# backplane.net
KiCad netlist of a schematic drawn in Altium Designer
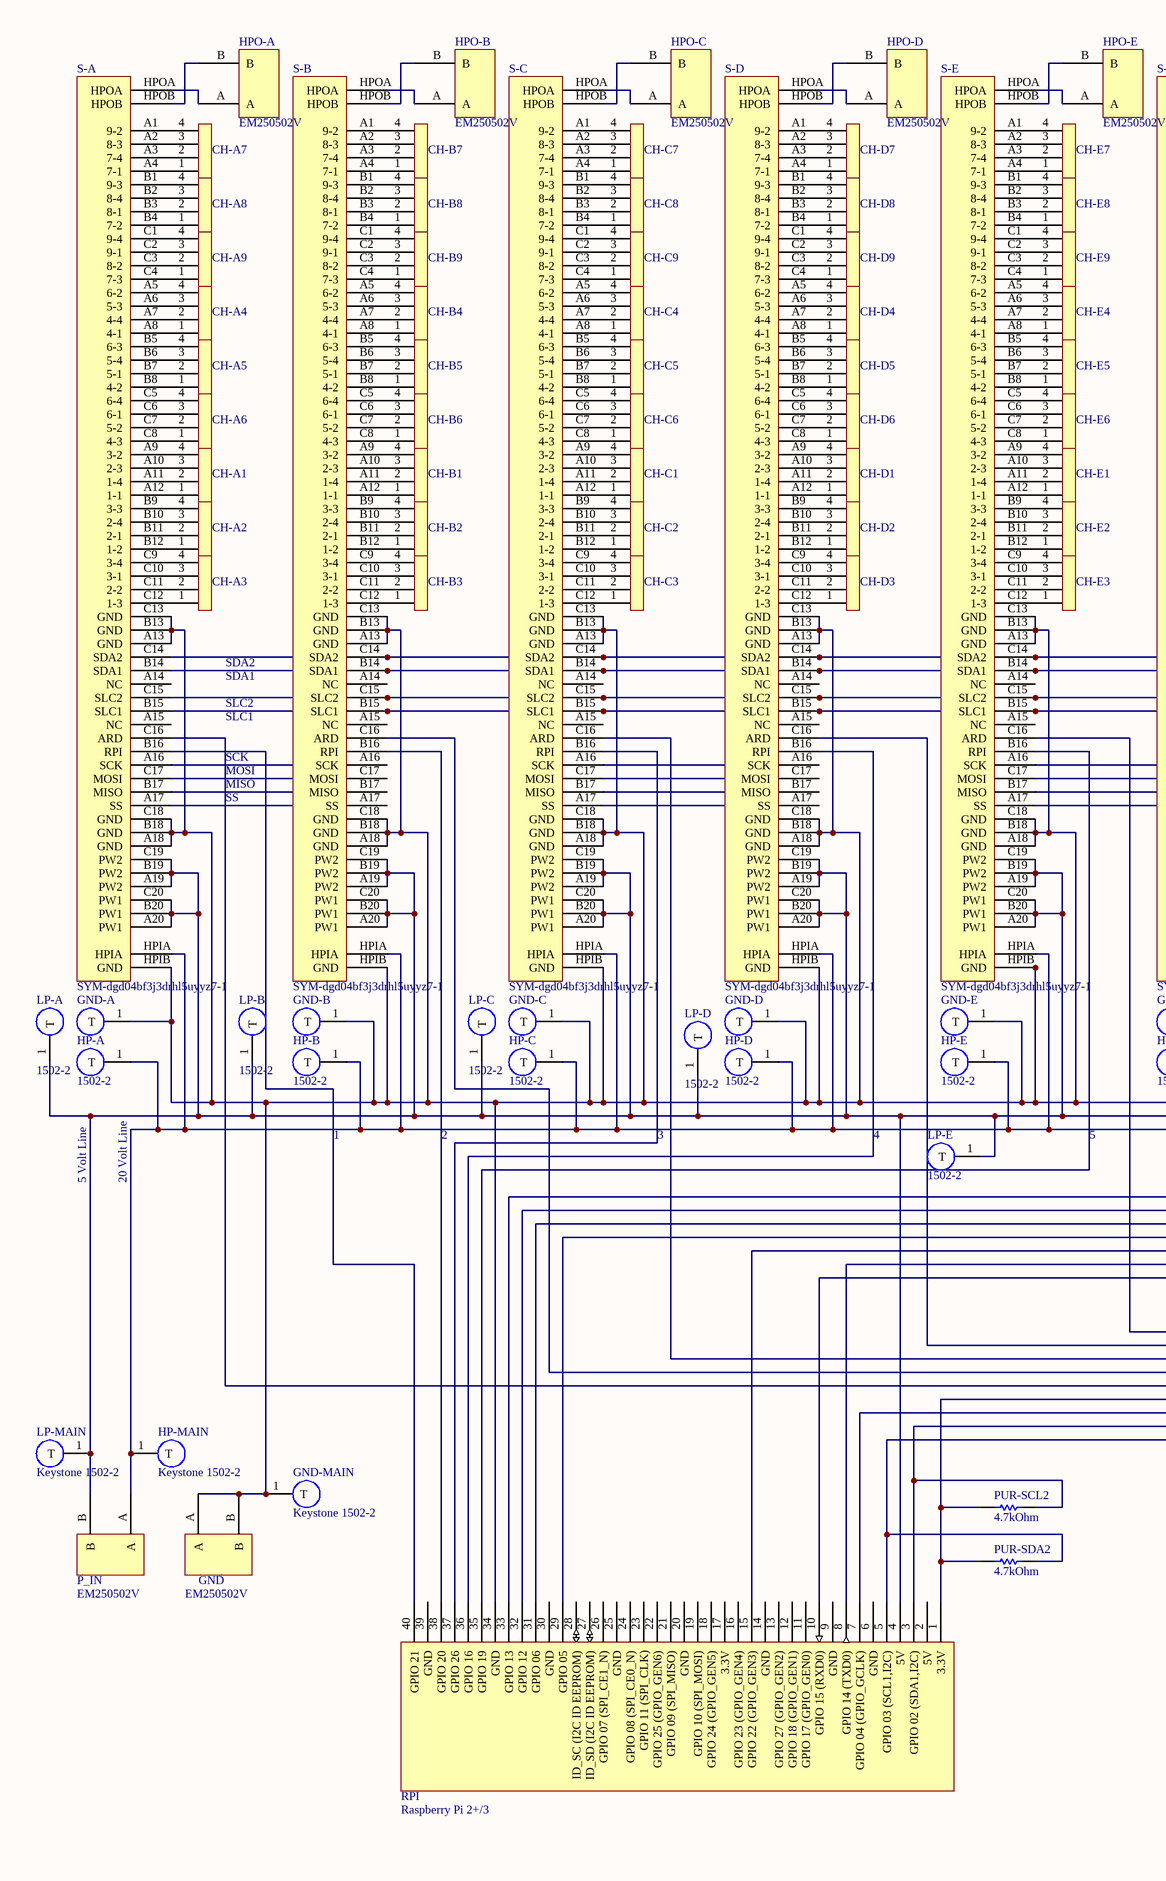
[diagram p0: backplane.SchDoc, left]
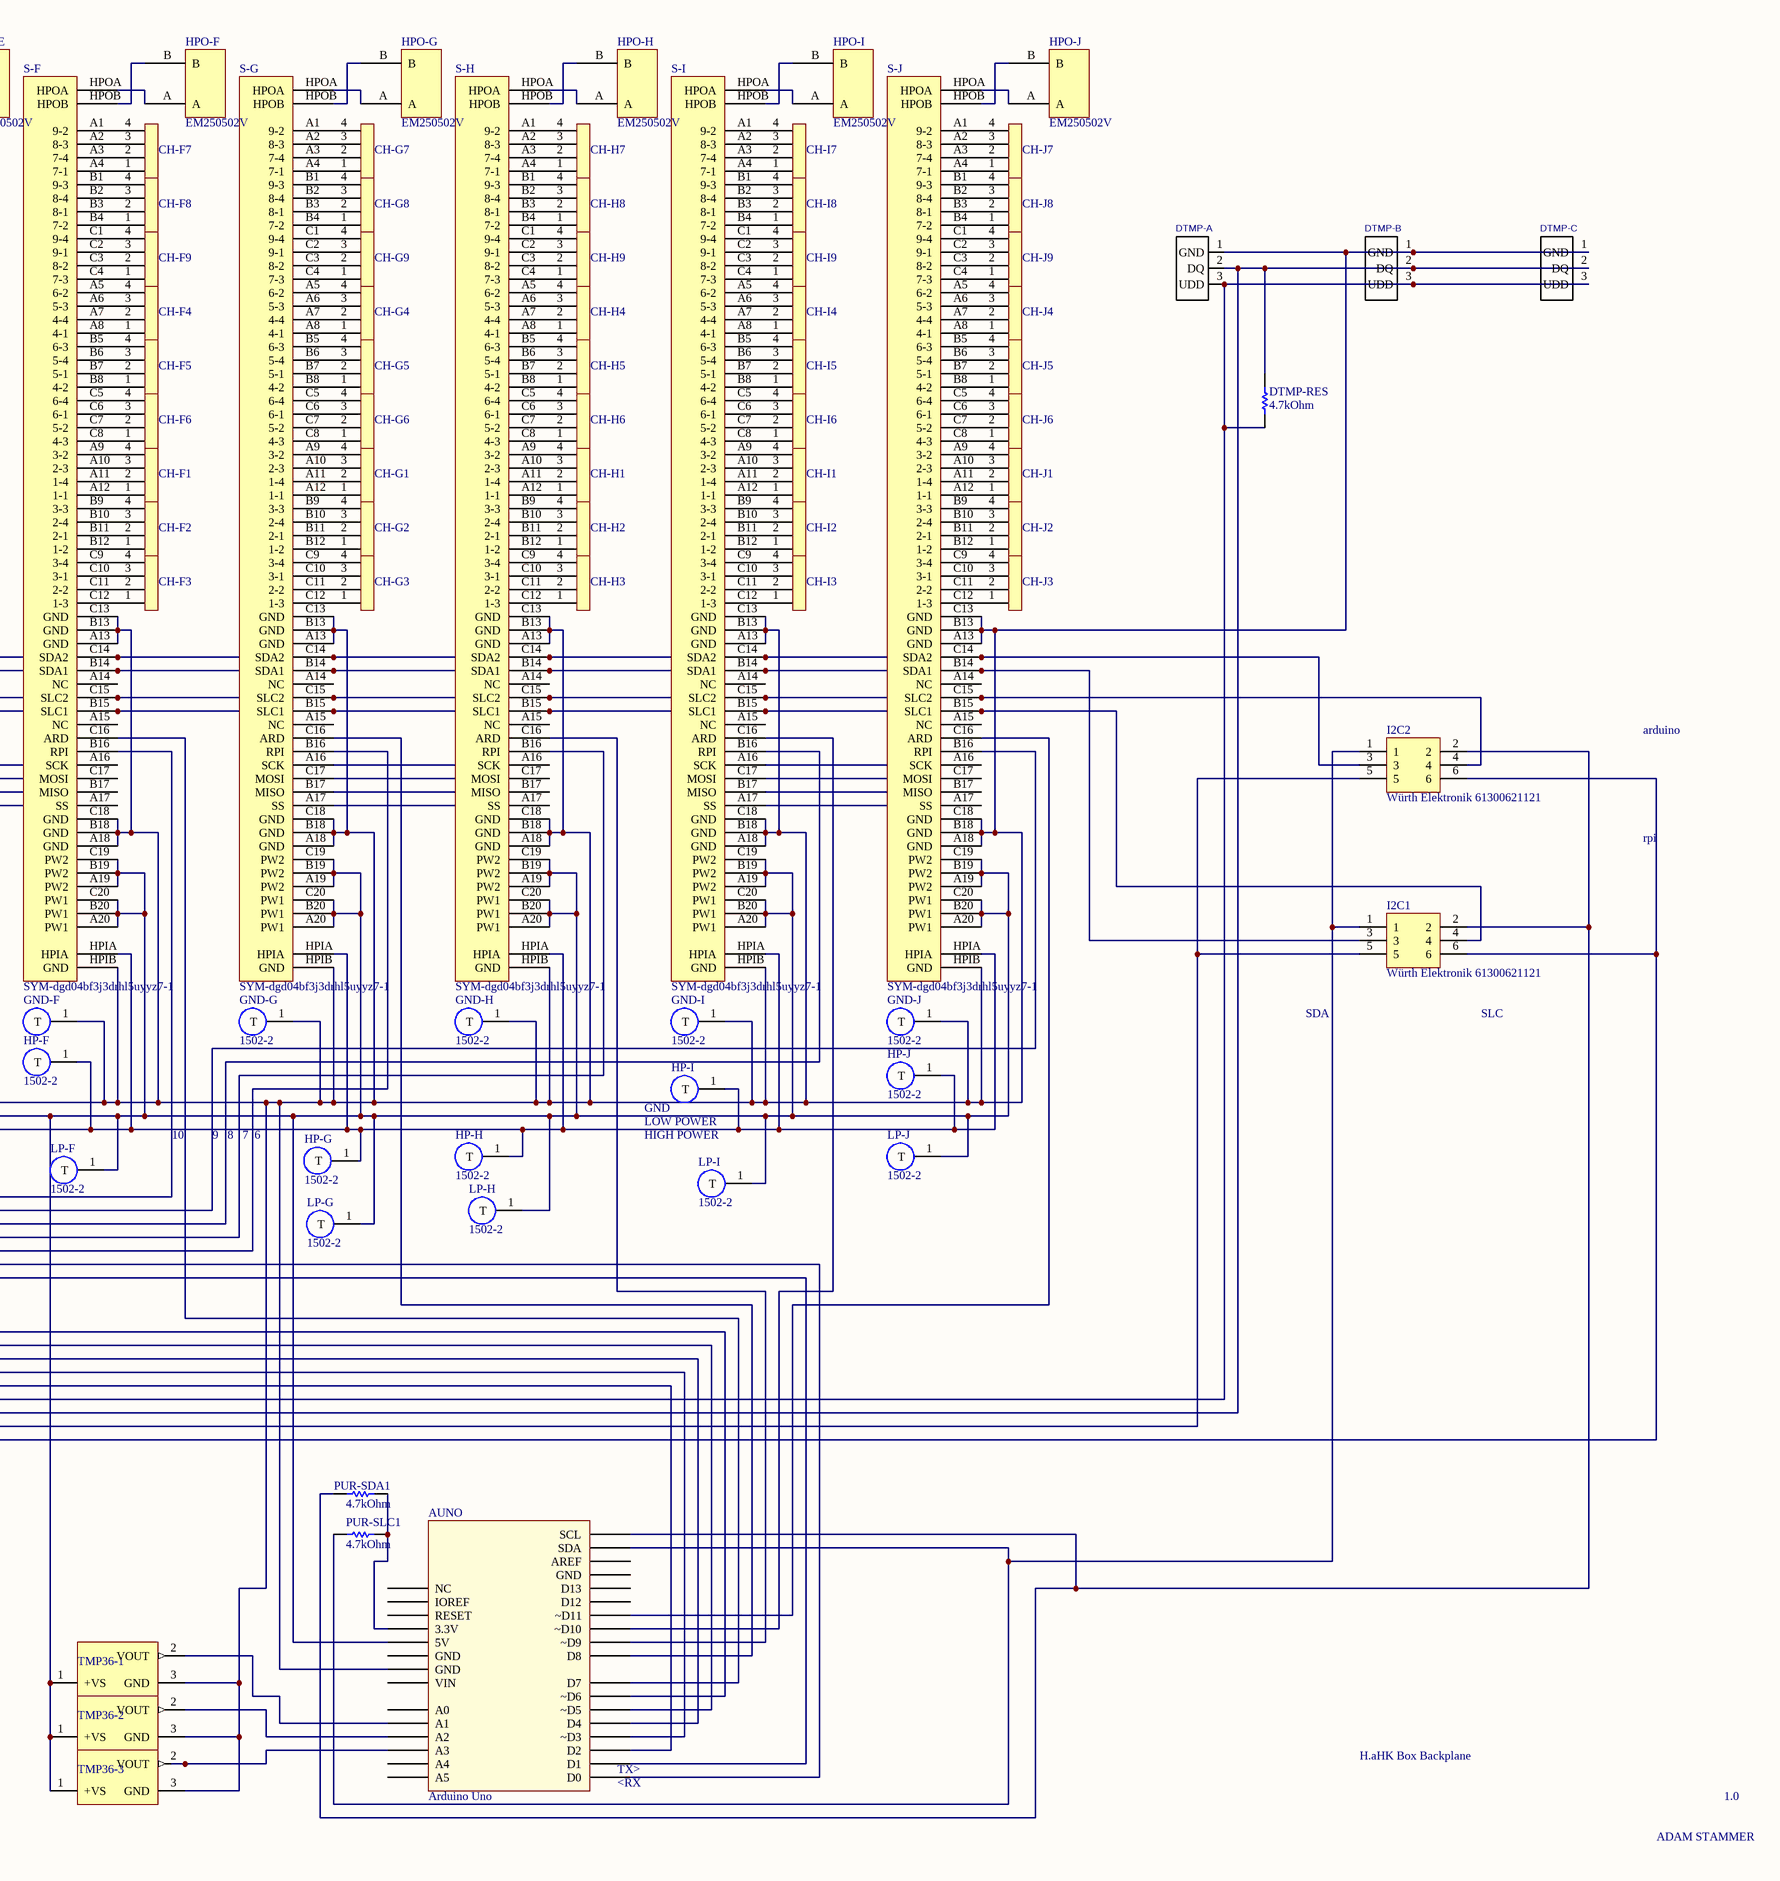
[diagram p1: backplane.SchDoc, right]

(export (version "E")
  (design (tool "Eeschema 10.0.6"))
  (components
    (comp (ref "AUNO")
      (value "Arduino Uno")
      (footprint "PCB-5e3n8s0ey5jqr2f9nncc-1")
      (description "Microcontroller board, Uno [Arduino] A000066 Microcontroller board, Uno 7640152110092")
      (libsource (lib "CommunityVault") (part "SYM-aa24626d5c2275e3-1"))
    )
    (comp (ref "CH-A1")
      (value "Molex 22-28-4043")
      (footprint "HEADER_1x4")
      (description "Conn; Rect./PCB; Breakaway Header; 4 Cir.; Vert.; KK 254 Ser.; Gold Plate; 6.09mm Pin L")
      (fields (field (name "MANUFACTURER PART NUMBER") "22-28-4043"))
      (libsource (lib "CommunityVault") (part "CMP-44448d4a5f9d9b83-3"))
    )
    (comp (ref "CH-A2")
      (value "Molex 22-28-4043")
      (footprint "HEADER_1x4")
      (description "Conn; Rect./PCB; Breakaway Header; 4 Cir.; Vert.; KK 254 Ser.; Gold Plate; 6.09mm Pin L")
      (fields (field (name "MANUFACTURER PART NUMBER") "22-28-4043"))
      (libsource (lib "CommunityVault") (part "CMP-44448d4a5f9d9b83-3"))
    )
    (comp (ref "CH-A3")
      (value "Molex 22-28-4043")
      (footprint "HEADER_1x4")
      (description "Conn; Rect./PCB; Breakaway Header; 4 Cir.; Vert.; KK 254 Ser.; Gold Plate; 6.09mm Pin L")
      (fields (field (name "MANUFACTURER PART NUMBER") "22-28-4043"))
      (libsource (lib "CommunityVault") (part "CMP-44448d4a5f9d9b83-3"))
    )
    (comp (ref "CH-A4")
      (value "Molex 22-28-4043")
      (footprint "HEADER_1x4")
      (description "Conn; Rect./PCB; Breakaway Header; 4 Cir.; Vert.; KK 254 Ser.; Gold Plate; 6.09mm Pin L")
      (fields (field (name "MANUFACTURER PART NUMBER") "22-28-4043"))
      (libsource (lib "CommunityVault") (part "CMP-44448d4a5f9d9b83-3"))
    )
    (comp (ref "CH-A5")
      (value "Molex 22-28-4043")
      (footprint "HEADER_1x4")
      (description "Conn; Rect./PCB; Breakaway Header; 4 Cir.; Vert.; KK 254 Ser.; Gold Plate; 6.09mm Pin L")
      (fields (field (name "MANUFACTURER PART NUMBER") "22-28-4043"))
      (libsource (lib "CommunityVault") (part "CMP-44448d4a5f9d9b83-3"))
    )
    (comp (ref "CH-A6")
      (value "Molex 22-28-4043")
      (footprint "HEADER_1x4")
      (description "Conn; Rect./PCB; Breakaway Header; 4 Cir.; Vert.; KK 254 Ser.; Gold Plate; 6.09mm Pin L")
      (fields (field (name "MANUFACTURER PART NUMBER") "22-28-4043"))
      (libsource (lib "CommunityVault") (part "CMP-44448d4a5f9d9b83-3"))
    )
    (comp (ref "CH-A7")
      (value "Molex 22-28-4043")
      (footprint "HEADER_1x4")
      (description "Conn; Rect./PCB; Breakaway Header; 4 Cir.; Vert.; KK 254 Ser.; Gold Plate; 6.09mm Pin L")
      (fields (field (name "MANUFACTURER PART NUMBER") "22-28-4043"))
      (libsource (lib "CommunityVault") (part "CMP-44448d4a5f9d9b83-3"))
    )
    (comp (ref "CH-A8")
      (value "Molex 22-28-4043")
      (footprint "HEADER_1x4")
      (description "Conn; Rect./PCB; Breakaway Header; 4 Cir.; Vert.; KK 254 Ser.; Gold Plate; 6.09mm Pin L")
      (fields (field (name "MANUFACTURER PART NUMBER") "22-28-4043"))
      (libsource (lib "CommunityVault") (part "CMP-44448d4a5f9d9b83-3"))
    )
    (comp (ref "CH-A9")
      (value "Molex 22-28-4043")
      (footprint "HEADER_1x4")
      (description "Conn; Rect./PCB; Breakaway Header; 4 Cir.; Vert.; KK 254 Ser.; Gold Plate; 6.09mm Pin L")
      (fields (field (name "MANUFACTURER PART NUMBER") "22-28-4043"))
      (libsource (lib "CommunityVault") (part "CMP-44448d4a5f9d9b83-3"))
    )
    (comp (ref "CH-B1")
      (value "Molex 22-28-4043")
      (footprint "HEADER_1x4")
      (description "Conn; Rect./PCB; Breakaway Header; 4 Cir.; Vert.; KK 254 Ser.; Gold Plate; 6.09mm Pin L")
      (fields (field (name "MANUFACTURER PART NUMBER") "22-28-4043"))
      (libsource (lib "CommunityVault") (part "CMP-44448d4a5f9d9b83-3"))
    )
    (comp (ref "CH-B2")
      (value "Molex 22-28-4043")
      (footprint "HEADER_1x4")
      (description "Conn; Rect./PCB; Breakaway Header; 4 Cir.; Vert.; KK 254 Ser.; Gold Plate; 6.09mm Pin L")
      (fields (field (name "MANUFACTURER PART NUMBER") "22-28-4043"))
      (libsource (lib "CommunityVault") (part "CMP-44448d4a5f9d9b83-3"))
    )
    (comp (ref "CH-B3")
      (value "Molex 22-28-4043")
      (footprint "HEADER_1x4")
      (description "Conn; Rect./PCB; Breakaway Header; 4 Cir.; Vert.; KK 254 Ser.; Gold Plate; 6.09mm Pin L")
      (fields (field (name "MANUFACTURER PART NUMBER") "22-28-4043"))
      (libsource (lib "CommunityVault") (part "CMP-44448d4a5f9d9b83-3"))
    )
    (comp (ref "CH-B4")
      (value "Molex 22-28-4043")
      (footprint "HEADER_1x4")
      (description "Conn; Rect./PCB; Breakaway Header; 4 Cir.; Vert.; KK 254 Ser.; Gold Plate; 6.09mm Pin L")
      (fields (field (name "MANUFACTURER PART NUMBER") "22-28-4043"))
      (libsource (lib "CommunityVault") (part "CMP-44448d4a5f9d9b83-3"))
    )
    (comp (ref "CH-B5")
      (value "Molex 22-28-4043")
      (footprint "HEADER_1x4")
      (description "Conn; Rect./PCB; Breakaway Header; 4 Cir.; Vert.; KK 254 Ser.; Gold Plate; 6.09mm Pin L")
      (fields (field (name "MANUFACTURER PART NUMBER") "22-28-4043"))
      (libsource (lib "CommunityVault") (part "CMP-44448d4a5f9d9b83-3"))
    )
    (comp (ref "CH-B6")
      (value "Molex 22-28-4043")
      (footprint "HEADER_1x4")
      (description "Conn; Rect./PCB; Breakaway Header; 4 Cir.; Vert.; KK 254 Ser.; Gold Plate; 6.09mm Pin L")
      (fields (field (name "MANUFACTURER PART NUMBER") "22-28-4043"))
      (libsource (lib "CommunityVault") (part "CMP-44448d4a5f9d9b83-3"))
    )
    (comp (ref "CH-B7")
      (value "Molex 22-28-4043")
      (footprint "HEADER_1x4")
      (description "Conn; Rect./PCB; Breakaway Header; 4 Cir.; Vert.; KK 254 Ser.; Gold Plate; 6.09mm Pin L")
      (fields (field (name "MANUFACTURER PART NUMBER") "22-28-4043"))
      (libsource (lib "CommunityVault") (part "CMP-44448d4a5f9d9b83-3"))
    )
    (comp (ref "CH-B8")
      (value "Molex 22-28-4043")
      (footprint "HEADER_1x4")
      (description "Conn; Rect./PCB; Breakaway Header; 4 Cir.; Vert.; KK 254 Ser.; Gold Plate; 6.09mm Pin L")
      (fields (field (name "MANUFACTURER PART NUMBER") "22-28-4043"))
      (libsource (lib "CommunityVault") (part "CMP-44448d4a5f9d9b83-3"))
    )
    (comp (ref "CH-B9")
      (value "Molex 22-28-4043")
      (footprint "HEADER_1x4")
      (description "Conn; Rect./PCB; Breakaway Header; 4 Cir.; Vert.; KK 254 Ser.; Gold Plate; 6.09mm Pin L")
      (fields (field (name "MANUFACTURER PART NUMBER") "22-28-4043"))
      (libsource (lib "CommunityVault") (part "CMP-44448d4a5f9d9b83-3"))
    )
    (comp (ref "CH-C1")
      (value "Molex 22-28-4043")
      (footprint "HEADER_1x4")
      (description "Conn; Rect./PCB; Breakaway Header; 4 Cir.; Vert.; KK 254 Ser.; Gold Plate; 6.09mm Pin L")
      (fields (field (name "MANUFACTURER PART NUMBER") "22-28-4043"))
      (libsource (lib "CommunityVault") (part "CMP-44448d4a5f9d9b83-3"))
    )
    (comp (ref "CH-C2")
      (value "Molex 22-28-4043")
      (footprint "HEADER_1x4")
      (description "Conn; Rect./PCB; Breakaway Header; 4 Cir.; Vert.; KK 254 Ser.; Gold Plate; 6.09mm Pin L")
      (fields (field (name "MANUFACTURER PART NUMBER") "22-28-4043"))
      (libsource (lib "CommunityVault") (part "CMP-44448d4a5f9d9b83-3"))
    )
    (comp (ref "CH-C3")
      (value "Molex 22-28-4043")
      (footprint "HEADER_1x4")
      (description "Conn; Rect./PCB; Breakaway Header; 4 Cir.; Vert.; KK 254 Ser.; Gold Plate; 6.09mm Pin L")
      (fields (field (name "MANUFACTURER PART NUMBER") "22-28-4043"))
      (libsource (lib "CommunityVault") (part "CMP-44448d4a5f9d9b83-3"))
    )
    (comp (ref "CH-C4")
      (value "Molex 22-28-4043")
      (footprint "HEADER_1x4")
      (description "Conn; Rect./PCB; Breakaway Header; 4 Cir.; Vert.; KK 254 Ser.; Gold Plate; 6.09mm Pin L")
      (fields (field (name "MANUFACTURER PART NUMBER") "22-28-4043"))
      (libsource (lib "CommunityVault") (part "CMP-44448d4a5f9d9b83-3"))
    )
    (comp (ref "CH-C5")
      (value "Molex 22-28-4043")
      (footprint "HEADER_1x4")
      (description "Conn; Rect./PCB; Breakaway Header; 4 Cir.; Vert.; KK 254 Ser.; Gold Plate; 6.09mm Pin L")
      (fields (field (name "MANUFACTURER PART NUMBER") "22-28-4043"))
      (libsource (lib "CommunityVault") (part "CMP-44448d4a5f9d9b83-3"))
    )
    (comp (ref "CH-C6")
      (value "Molex 22-28-4043")
      (footprint "HEADER_1x4")
      (description "Conn; Rect./PCB; Breakaway Header; 4 Cir.; Vert.; KK 254 Ser.; Gold Plate; 6.09mm Pin L")
      (fields (field (name "MANUFACTURER PART NUMBER") "22-28-4043"))
      (libsource (lib "CommunityVault") (part "CMP-44448d4a5f9d9b83-3"))
    )
    (comp (ref "CH-C7")
      (value "Molex 22-28-4043")
      (footprint "HEADER_1x4")
      (description "Conn; Rect./PCB; Breakaway Header; 4 Cir.; Vert.; KK 254 Ser.; Gold Plate; 6.09mm Pin L")
      (fields (field (name "MANUFACTURER PART NUMBER") "22-28-4043"))
      (libsource (lib "CommunityVault") (part "CMP-44448d4a5f9d9b83-3"))
    )
    (comp (ref "CH-C8")
      (value "Molex 22-28-4043")
      (footprint "HEADER_1x4")
      (description "Conn; Rect./PCB; Breakaway Header; 4 Cir.; Vert.; KK 254 Ser.; Gold Plate; 6.09mm Pin L")
      (fields (field (name "MANUFACTURER PART NUMBER") "22-28-4043"))
      (libsource (lib "CommunityVault") (part "CMP-44448d4a5f9d9b83-3"))
    )
    (comp (ref "CH-C9")
      (value "Molex 22-28-4043")
      (footprint "HEADER_1x4")
      (description "Conn; Rect./PCB; Breakaway Header; 4 Cir.; Vert.; KK 254 Ser.; Gold Plate; 6.09mm Pin L")
      (fields (field (name "MANUFACTURER PART NUMBER") "22-28-4043"))
      (libsource (lib "CommunityVault") (part "CMP-44448d4a5f9d9b83-3"))
    )
    (comp (ref "CH-D1")
      (value "Molex 22-28-4043")
      (footprint "HEADER_1x4")
      (description "Conn; Rect./PCB; Breakaway Header; 4 Cir.; Vert.; KK 254 Ser.; Gold Plate; 6.09mm Pin L")
      (fields (field (name "MANUFACTURER PART NUMBER") "22-28-4043"))
      (libsource (lib "CommunityVault") (part "CMP-44448d4a5f9d9b83-3"))
    )
    (comp (ref "CH-D2")
      (value "Molex 22-28-4043")
      (footprint "HEADER_1x4")
      (description "Conn; Rect./PCB; Breakaway Header; 4 Cir.; Vert.; KK 254 Ser.; Gold Plate; 6.09mm Pin L")
      (fields (field (name "MANUFACTURER PART NUMBER") "22-28-4043"))
      (libsource (lib "CommunityVault") (part "CMP-44448d4a5f9d9b83-3"))
    )
    (comp (ref "CH-D3")
      (value "Molex 22-28-4043")
      (footprint "HEADER_1x4")
      (description "Conn; Rect./PCB; Breakaway Header; 4 Cir.; Vert.; KK 254 Ser.; Gold Plate; 6.09mm Pin L")
      (fields (field (name "MANUFACTURER PART NUMBER") "22-28-4043"))
      (libsource (lib "CommunityVault") (part "CMP-44448d4a5f9d9b83-3"))
    )
    (comp (ref "CH-D4")
      (value "Molex 22-28-4043")
      (footprint "HEADER_1x4")
      (description "Conn; Rect./PCB; Breakaway Header; 4 Cir.; Vert.; KK 254 Ser.; Gold Plate; 6.09mm Pin L")
      (fields (field (name "MANUFACTURER PART NUMBER") "22-28-4043"))
      (libsource (lib "CommunityVault") (part "CMP-44448d4a5f9d9b83-3"))
    )
    (comp (ref "CH-D5")
      (value "Molex 22-28-4043")
      (footprint "HEADER_1x4")
      (description "Conn; Rect./PCB; Breakaway Header; 4 Cir.; Vert.; KK 254 Ser.; Gold Plate; 6.09mm Pin L")
      (fields (field (name "MANUFACTURER PART NUMBER") "22-28-4043"))
      (libsource (lib "CommunityVault") (part "CMP-44448d4a5f9d9b83-3"))
    )
    (comp (ref "CH-D6")
      (value "Molex 22-28-4043")
      (footprint "HEADER_1x4")
      (description "Conn; Rect./PCB; Breakaway Header; 4 Cir.; Vert.; KK 254 Ser.; Gold Plate; 6.09mm Pin L")
      (fields (field (name "MANUFACTURER PART NUMBER") "22-28-4043"))
      (libsource (lib "CommunityVault") (part "CMP-44448d4a5f9d9b83-3"))
    )
    (comp (ref "CH-D7")
      (value "Molex 22-28-4043")
      (footprint "HEADER_1x4")
      (description "Conn; Rect./PCB; Breakaway Header; 4 Cir.; Vert.; KK 254 Ser.; Gold Plate; 6.09mm Pin L")
      (fields (field (name "MANUFACTURER PART NUMBER") "22-28-4043"))
      (libsource (lib "CommunityVault") (part "CMP-44448d4a5f9d9b83-3"))
    )
    (comp (ref "CH-D8")
      (value "Molex 22-28-4043")
      (footprint "HEADER_1x4")
      (description "Conn; Rect./PCB; Breakaway Header; 4 Cir.; Vert.; KK 254 Ser.; Gold Plate; 6.09mm Pin L")
      (fields (field (name "MANUFACTURER PART NUMBER") "22-28-4043"))
      (libsource (lib "CommunityVault") (part "CMP-44448d4a5f9d9b83-3"))
    )
    (comp (ref "CH-D9")
      (value "Molex 22-28-4043")
      (footprint "HEADER_1x4")
      (description "Conn; Rect./PCB; Breakaway Header; 4 Cir.; Vert.; KK 254 Ser.; Gold Plate; 6.09mm Pin L")
      (fields (field (name "MANUFACTURER PART NUMBER") "22-28-4043"))
      (libsource (lib "CommunityVault") (part "CMP-44448d4a5f9d9b83-3"))
    )
    (comp (ref "CH-E1")
      (value "Molex 22-28-4043")
      (footprint "HEADER_1x4")
      (description "Conn; Rect./PCB; Breakaway Header; 4 Cir.; Vert.; KK 254 Ser.; Gold Plate; 6.09mm Pin L")
      (fields (field (name "MANUFACTURER PART NUMBER") "22-28-4043"))
      (libsource (lib "CommunityVault") (part "CMP-44448d4a5f9d9b83-3"))
    )
    (comp (ref "CH-E2")
      (value "Molex 22-28-4043")
      (footprint "HEADER_1x4")
      (description "Conn; Rect./PCB; Breakaway Header; 4 Cir.; Vert.; KK 254 Ser.; Gold Plate; 6.09mm Pin L")
      (fields (field (name "MANUFACTURER PART NUMBER") "22-28-4043"))
      (libsource (lib "CommunityVault") (part "CMP-44448d4a5f9d9b83-3"))
    )
    (comp (ref "CH-E3")
      (value "Molex 22-28-4043")
      (footprint "HEADER_1x4")
      (description "Conn; Rect./PCB; Breakaway Header; 4 Cir.; Vert.; KK 254 Ser.; Gold Plate; 6.09mm Pin L")
      (fields (field (name "MANUFACTURER PART NUMBER") "22-28-4043"))
      (libsource (lib "CommunityVault") (part "CMP-44448d4a5f9d9b83-3"))
    )
    (comp (ref "CH-E4")
      (value "Molex 22-28-4043")
      (footprint "HEADER_1x4")
      (description "Conn; Rect./PCB; Breakaway Header; 4 Cir.; Vert.; KK 254 Ser.; Gold Plate; 6.09mm Pin L")
      (fields (field (name "MANUFACTURER PART NUMBER") "22-28-4043"))
      (libsource (lib "CommunityVault") (part "CMP-44448d4a5f9d9b83-3"))
    )
    (comp (ref "CH-E5")
      (value "Molex 22-28-4043")
      (footprint "HEADER_1x4")
      (description "Conn; Rect./PCB; Breakaway Header; 4 Cir.; Vert.; KK 254 Ser.; Gold Plate; 6.09mm Pin L")
      (fields (field (name "MANUFACTURER PART NUMBER") "22-28-4043"))
      (libsource (lib "CommunityVault") (part "CMP-44448d4a5f9d9b83-3"))
    )
    (comp (ref "CH-E6")
      (value "Molex 22-28-4043")
      (footprint "HEADER_1x4")
      (description "Conn; Rect./PCB; Breakaway Header; 4 Cir.; Vert.; KK 254 Ser.; Gold Plate; 6.09mm Pin L")
      (fields (field (name "MANUFACTURER PART NUMBER") "22-28-4043"))
      (libsource (lib "CommunityVault") (part "CMP-44448d4a5f9d9b83-3"))
    )
    (comp (ref "CH-E7")
      (value "Molex 22-28-4043")
      (footprint "HEADER_1x4")
      (description "Conn; Rect./PCB; Breakaway Header; 4 Cir.; Vert.; KK 254 Ser.; Gold Plate; 6.09mm Pin L")
      (fields (field (name "MANUFACTURER PART NUMBER") "22-28-4043"))
      (libsource (lib "CommunityVault") (part "CMP-44448d4a5f9d9b83-3"))
    )
    (comp (ref "CH-E8")
      (value "Molex 22-28-4043")
      (footprint "HEADER_1x4")
      (description "Conn; Rect./PCB; Breakaway Header; 4 Cir.; Vert.; KK 254 Ser.; Gold Plate; 6.09mm Pin L")
      (fields (field (name "MANUFACTURER PART NUMBER") "22-28-4043"))
      (libsource (lib "CommunityVault") (part "CMP-44448d4a5f9d9b83-3"))
    )
    (comp (ref "CH-E9")
      (value "Molex 22-28-4043")
      (footprint "HEADER_1x4")
      (description "Conn; Rect./PCB; Breakaway Header; 4 Cir.; Vert.; KK 254 Ser.; Gold Plate; 6.09mm Pin L")
      (fields (field (name "MANUFACTURER PART NUMBER") "22-28-4043"))
      (libsource (lib "CommunityVault") (part "CMP-44448d4a5f9d9b83-3"))
    )
    (comp (ref "CH-F1")
      (value "Molex 22-28-4043")
      (footprint "HEADER_1x4")
      (description "Conn; Rect./PCB; Breakaway Header; 4 Cir.; Vert.; KK 254 Ser.; Gold Plate; 6.09mm Pin L")
      (fields (field (name "MANUFACTURER PART NUMBER") "22-28-4043"))
      (libsource (lib "CommunityVault") (part "CMP-44448d4a5f9d9b83-3"))
    )
    (comp (ref "CH-F2")
      (value "Molex 22-28-4043")
      (footprint "HEADER_1x4")
      (description "Conn; Rect./PCB; Breakaway Header; 4 Cir.; Vert.; KK 254 Ser.; Gold Plate; 6.09mm Pin L")
      (fields (field (name "MANUFACTURER PART NUMBER") "22-28-4043"))
      (libsource (lib "CommunityVault") (part "CMP-44448d4a5f9d9b83-3"))
    )
    (comp (ref "CH-F3")
      (value "Molex 22-28-4043")
      (footprint "HEADER_1x4")
      (description "Conn; Rect./PCB; Breakaway Header; 4 Cir.; Vert.; KK 254 Ser.; Gold Plate; 6.09mm Pin L")
      (fields (field (name "MANUFACTURER PART NUMBER") "22-28-4043"))
      (libsource (lib "CommunityVault") (part "CMP-44448d4a5f9d9b83-3"))
    )
    (comp (ref "CH-F4")
      (value "Molex 22-28-4043")
      (footprint "HEADER_1x4")
      (description "Conn; Rect./PCB; Breakaway Header; 4 Cir.; Vert.; KK 254 Ser.; Gold Plate; 6.09mm Pin L")
      (fields (field (name "MANUFACTURER PART NUMBER") "22-28-4043"))
      (libsource (lib "CommunityVault") (part "CMP-44448d4a5f9d9b83-3"))
    )
    (comp (ref "CH-F5")
      (value "Molex 22-28-4043")
      (footprint "HEADER_1x4")
      (description "Conn; Rect./PCB; Breakaway Header; 4 Cir.; Vert.; KK 254 Ser.; Gold Plate; 6.09mm Pin L")
      (fields (field (name "MANUFACTURER PART NUMBER") "22-28-4043"))
      (libsource (lib "CommunityVault") (part "CMP-44448d4a5f9d9b83-3"))
    )
    (comp (ref "CH-F6")
      (value "Molex 22-28-4043")
      (footprint "HEADER_1x4")
      (description "Conn; Rect./PCB; Breakaway Header; 4 Cir.; Vert.; KK 254 Ser.; Gold Plate; 6.09mm Pin L")
      (fields (field (name "MANUFACTURER PART NUMBER") "22-28-4043"))
      (libsource (lib "CommunityVault") (part "CMP-44448d4a5f9d9b83-3"))
    )
    (comp (ref "CH-F7")
      (value "Molex 22-28-4043")
      (footprint "HEADER_1x4")
      (description "Conn; Rect./PCB; Breakaway Header; 4 Cir.; Vert.; KK 254 Ser.; Gold Plate; 6.09mm Pin L")
      (fields (field (name "MANUFACTURER PART NUMBER") "22-28-4043"))
      (libsource (lib "CommunityVault") (part "CMP-44448d4a5f9d9b83-3"))
    )
    (comp (ref "CH-F8")
      (value "Molex 22-28-4043")
      (footprint "HEADER_1x4")
      (description "Conn; Rect./PCB; Breakaway Header; 4 Cir.; Vert.; KK 254 Ser.; Gold Plate; 6.09mm Pin L")
      (fields (field (name "MANUFACTURER PART NUMBER") "22-28-4043"))
      (libsource (lib "CommunityVault") (part "CMP-44448d4a5f9d9b83-3"))
    )
    (comp (ref "CH-F9")
      (value "Molex 22-28-4043")
      (footprint "HEADER_1x4")
      (description "Conn; Rect./PCB; Breakaway Header; 4 Cir.; Vert.; KK 254 Ser.; Gold Plate; 6.09mm Pin L")
      (fields (field (name "MANUFACTURER PART NUMBER") "22-28-4043"))
      (libsource (lib "CommunityVault") (part "CMP-44448d4a5f9d9b83-3"))
    )
    (comp (ref "CH-G1")
      (value "Molex 22-28-4043")
      (footprint "HEADER_1x4")
      (description "Conn; Rect./PCB; Breakaway Header; 4 Cir.; Vert.; KK 254 Ser.; Gold Plate; 6.09mm Pin L")
      (fields (field (name "MANUFACTURER PART NUMBER") "22-28-4043"))
      (libsource (lib "CommunityVault") (part "CMP-44448d4a5f9d9b83-3"))
    )
    (comp (ref "CH-G2")
      (value "Molex 22-28-4043")
      (footprint "HEADER_1x4")
      (description "Conn; Rect./PCB; Breakaway Header; 4 Cir.; Vert.; KK 254 Ser.; Gold Plate; 6.09mm Pin L")
      (fields (field (name "MANUFACTURER PART NUMBER") "22-28-4043"))
      (libsource (lib "CommunityVault") (part "CMP-44448d4a5f9d9b83-3"))
    )
    (comp (ref "CH-G3")
      (value "Molex 22-28-4043")
      (footprint "HEADER_1x4")
      (description "Conn; Rect./PCB; Breakaway Header; 4 Cir.; Vert.; KK 254 Ser.; Gold Plate; 6.09mm Pin L")
      (fields (field (name "MANUFACTURER PART NUMBER") "22-28-4043"))
      (libsource (lib "CommunityVault") (part "CMP-44448d4a5f9d9b83-3"))
    )
    (comp (ref "CH-G4")
      (value "Molex 22-28-4043")
      (footprint "HEADER_1x4")
      (description "Conn; Rect./PCB; Breakaway Header; 4 Cir.; Vert.; KK 254 Ser.; Gold Plate; 6.09mm Pin L")
      (fields (field (name "MANUFACTURER PART NUMBER") "22-28-4043"))
      (libsource (lib "CommunityVault") (part "CMP-44448d4a5f9d9b83-3"))
    )
    (comp (ref "CH-G5")
      (value "Molex 22-28-4043")
      (footprint "HEADER_1x4")
      (description "Conn; Rect./PCB; Breakaway Header; 4 Cir.; Vert.; KK 254 Ser.; Gold Plate; 6.09mm Pin L")
      (fields (field (name "MANUFACTURER PART NUMBER") "22-28-4043"))
      (libsource (lib "CommunityVault") (part "CMP-44448d4a5f9d9b83-3"))
    )
    (comp (ref "CH-G6")
      (value "Molex 22-28-4043")
      (footprint "HEADER_1x4")
      (description "Conn; Rect./PCB; Breakaway Header; 4 Cir.; Vert.; KK 254 Ser.; Gold Plate; 6.09mm Pin L")
      (fields (field (name "MANUFACTURER PART NUMBER") "22-28-4043"))
      (libsource (lib "CommunityVault") (part "CMP-44448d4a5f9d9b83-3"))
    )
    (comp (ref "CH-G7")
      (value "Molex 22-28-4043")
      (footprint "HEADER_1x4")
      (description "Conn; Rect./PCB; Breakaway Header; 4 Cir.; Vert.; KK 254 Ser.; Gold Plate; 6.09mm Pin L")
      (fields (field (name "MANUFACTURER PART NUMBER") "22-28-4043"))
      (libsource (lib "CommunityVault") (part "CMP-44448d4a5f9d9b83-3"))
    )
    (comp (ref "CH-G8")
      (value "Molex 22-28-4043")
      (footprint "HEADER_1x4")
      (description "Conn; Rect./PCB; Breakaway Header; 4 Cir.; Vert.; KK 254 Ser.; Gold Plate; 6.09mm Pin L")
      (fields (field (name "MANUFACTURER PART NUMBER") "22-28-4043"))
      (libsource (lib "CommunityVault") (part "CMP-44448d4a5f9d9b83-3"))
    )
    (comp (ref "CH-G9")
      (value "Molex 22-28-4043")
      (footprint "HEADER_1x4")
      (description "Conn; Rect./PCB; Breakaway Header; 4 Cir.; Vert.; KK 254 Ser.; Gold Plate; 6.09mm Pin L")
      (fields (field (name "MANUFACTURER PART NUMBER") "22-28-4043"))
      (libsource (lib "CommunityVault") (part "CMP-44448d4a5f9d9b83-3"))
    )
    (comp (ref "CH-H1")
      (value "Molex 22-28-4043")
      (footprint "HEADER_1x4")
      (description "Conn; Rect./PCB; Breakaway Header; 4 Cir.; Vert.; KK 254 Ser.; Gold Plate; 6.09mm Pin L")
      (fields (field (name "MANUFACTURER PART NUMBER") "22-28-4043"))
      (libsource (lib "CommunityVault") (part "CMP-44448d4a5f9d9b83-3"))
    )
    (comp (ref "CH-H2")
      (value "Molex 22-28-4043")
      (footprint "HEADER_1x4")
      (description "Conn; Rect./PCB; Breakaway Header; 4 Cir.; Vert.; KK 254 Ser.; Gold Plate; 6.09mm Pin L")
      (fields (field (name "MANUFACTURER PART NUMBER") "22-28-4043"))
      (libsource (lib "CommunityVault") (part "CMP-44448d4a5f9d9b83-3"))
    )
    (comp (ref "CH-H3")
      (value "Molex 22-28-4043")
      (footprint "HEADER_1x4")
      (description "Conn; Rect./PCB; Breakaway Header; 4 Cir.; Vert.; KK 254 Ser.; Gold Plate; 6.09mm Pin L")
      (fields (field (name "MANUFACTURER PART NUMBER") "22-28-4043"))
      (libsource (lib "CommunityVault") (part "CMP-44448d4a5f9d9b83-3"))
    )
    (comp (ref "CH-H4")
      (value "Molex 22-28-4043")
      (footprint "HEADER_1x4")
      (description "Conn; Rect./PCB; Breakaway Header; 4 Cir.; Vert.; KK 254 Ser.; Gold Plate; 6.09mm Pin L")
      (fields (field (name "MANUFACTURER PART NUMBER") "22-28-4043"))
      (libsource (lib "CommunityVault") (part "CMP-44448d4a5f9d9b83-3"))
    )
    (comp (ref "CH-H5")
      (value "Molex 22-28-4043")
      (footprint "HEADER_1x4")
      (description "Conn; Rect./PCB; Breakaway Header; 4 Cir.; Vert.; KK 254 Ser.; Gold Plate; 6.09mm Pin L")
      (fields (field (name "MANUFACTURER PART NUMBER") "22-28-4043"))
      (libsource (lib "CommunityVault") (part "CMP-44448d4a5f9d9b83-3"))
    )
    (comp (ref "CH-H6")
      (value "Molex 22-28-4043")
      (footprint "HEADER_1x4")
      (description "Conn; Rect./PCB; Breakaway Header; 4 Cir.; Vert.; KK 254 Ser.; Gold Plate; 6.09mm Pin L")
      (fields (field (name "MANUFACTURER PART NUMBER") "22-28-4043"))
      (libsource (lib "CommunityVault") (part "CMP-44448d4a5f9d9b83-3"))
    )
    (comp (ref "CH-H7")
      (value "Molex 22-28-4043")
      (footprint "HEADER_1x4")
      (description "Conn; Rect./PCB; Breakaway Header; 4 Cir.; Vert.; KK 254 Ser.; Gold Plate; 6.09mm Pin L")
      (fields (field (name "MANUFACTURER PART NUMBER") "22-28-4043"))
      (libsource (lib "CommunityVault") (part "CMP-44448d4a5f9d9b83-3"))
    )
    (comp (ref "CH-H8")
      (value "Molex 22-28-4043")
      (footprint "HEADER_1x4")
      (description "Conn; Rect./PCB; Breakaway Header; 4 Cir.; Vert.; KK 254 Ser.; Gold Plate; 6.09mm Pin L")
      (fields (field (name "MANUFACTURER PART NUMBER") "22-28-4043"))
      (libsource (lib "CommunityVault") (part "CMP-44448d4a5f9d9b83-3"))
    )
    (comp (ref "CH-H9")
      (value "Molex 22-28-4043")
      (footprint "HEADER_1x4")
      (description "Conn; Rect./PCB; Breakaway Header; 4 Cir.; Vert.; KK 254 Ser.; Gold Plate; 6.09mm Pin L")
      (fields (field (name "MANUFACTURER PART NUMBER") "22-28-4043"))
      (libsource (lib "CommunityVault") (part "CMP-44448d4a5f9d9b83-3"))
    )
    (comp (ref "CH-I1")
      (value "Molex 22-28-4043")
      (footprint "HEADER_1x4")
      (description "Conn; Rect./PCB; Breakaway Header; 4 Cir.; Vert.; KK 254 Ser.; Gold Plate; 6.09mm Pin L")
      (fields (field (name "MANUFACTURER PART NUMBER") "22-28-4043"))
      (libsource (lib "CommunityVault") (part "CMP-44448d4a5f9d9b83-3"))
    )
    (comp (ref "CH-I2")
      (value "Molex 22-28-4043")
      (footprint "HEADER_1x4")
      (description "Conn; Rect./PCB; Breakaway Header; 4 Cir.; Vert.; KK 254 Ser.; Gold Plate; 6.09mm Pin L")
      (fields (field (name "MANUFACTURER PART NUMBER") "22-28-4043"))
      (libsource (lib "CommunityVault") (part "CMP-44448d4a5f9d9b83-3"))
    )
    (comp (ref "CH-I3")
      (value "Molex 22-28-4043")
      (footprint "HEADER_1x4")
      (description "Conn; Rect./PCB; Breakaway Header; 4 Cir.; Vert.; KK 254 Ser.; Gold Plate; 6.09mm Pin L")
      (fields (field (name "MANUFACTURER PART NUMBER") "22-28-4043"))
      (libsource (lib "CommunityVault") (part "CMP-44448d4a5f9d9b83-3"))
    )
    (comp (ref "CH-I4")
      (value "Molex 22-28-4043")
      (footprint "HEADER_1x4")
      (description "Conn; Rect./PCB; Breakaway Header; 4 Cir.; Vert.; KK 254 Ser.; Gold Plate; 6.09mm Pin L")
      (fields (field (name "MANUFACTURER PART NUMBER") "22-28-4043"))
      (libsource (lib "CommunityVault") (part "CMP-44448d4a5f9d9b83-3"))
    )
    (comp (ref "CH-I5")
      (value "Molex 22-28-4043")
      (footprint "HEADER_1x4")
      (description "Conn; Rect./PCB; Breakaway Header; 4 Cir.; Vert.; KK 254 Ser.; Gold Plate; 6.09mm Pin L")
      (fields (field (name "MANUFACTURER PART NUMBER") "22-28-4043"))
      (libsource (lib "CommunityVault") (part "CMP-44448d4a5f9d9b83-3"))
    )
    (comp (ref "CH-I6")
      (value "Molex 22-28-4043")
      (footprint "HEADER_1x4")
      (description "Conn; Rect./PCB; Breakaway Header; 4 Cir.; Vert.; KK 254 Ser.; Gold Plate; 6.09mm Pin L")
      (fields (field (name "MANUFACTURER PART NUMBER") "22-28-4043"))
      (libsource (lib "CommunityVault") (part "CMP-44448d4a5f9d9b83-3"))
    )
    (comp (ref "CH-I7")
      (value "Molex 22-28-4043")
      (footprint "HEADER_1x4")
      (description "Conn; Rect./PCB; Breakaway Header; 4 Cir.; Vert.; KK 254 Ser.; Gold Plate; 6.09mm Pin L")
      (fields (field (name "MANUFACTURER PART NUMBER") "22-28-4043"))
      (libsource (lib "CommunityVault") (part "CMP-44448d4a5f9d9b83-3"))
    )
    (comp (ref "CH-I8")
      (value "Molex 22-28-4043")
      (footprint "HEADER_1x4")
      (description "Conn; Rect./PCB; Breakaway Header; 4 Cir.; Vert.; KK 254 Ser.; Gold Plate; 6.09mm Pin L")
      (fields (field (name "MANUFACTURER PART NUMBER") "22-28-4043"))
      (libsource (lib "CommunityVault") (part "CMP-44448d4a5f9d9b83-3"))
    )
    (comp (ref "CH-I9")
      (value "Molex 22-28-4043")
      (footprint "HEADER_1x4")
      (description "Conn; Rect./PCB; Breakaway Header; 4 Cir.; Vert.; KK 254 Ser.; Gold Plate; 6.09mm Pin L")
      (fields (field (name "MANUFACTURER PART NUMBER") "22-28-4043"))
      (libsource (lib "CommunityVault") (part "CMP-44448d4a5f9d9b83-3"))
    )
    (comp (ref "CH-J1")
      (value "Molex 22-28-4043")
      (footprint "HEADER_1x4")
      (description "Conn; Rect./PCB; Breakaway Header; 4 Cir.; Vert.; KK 254 Ser.; Gold Plate; 6.09mm Pin L")
      (fields (field (name "MANUFACTURER PART NUMBER") "22-28-4043"))
      (libsource (lib "CommunityVault") (part "CMP-44448d4a5f9d9b83-3"))
    )
    (comp (ref "CH-J2")
      (value "Molex 22-28-4043")
      (footprint "HEADER_1x4")
      (description "Conn; Rect./PCB; Breakaway Header; 4 Cir.; Vert.; KK 254 Ser.; Gold Plate; 6.09mm Pin L")
      (fields (field (name "MANUFACTURER PART NUMBER") "22-28-4043"))
      (libsource (lib "CommunityVault") (part "CMP-44448d4a5f9d9b83-3"))
    )
    (comp (ref "CH-J3")
      (value "Molex 22-28-4043")
      (footprint "HEADER_1x4")
      (description "Conn; Rect./PCB; Breakaway Header; 4 Cir.; Vert.; KK 254 Ser.; Gold Plate; 6.09mm Pin L")
      (fields (field (name "MANUFACTURER PART NUMBER") "22-28-4043"))
      (libsource (lib "CommunityVault") (part "CMP-44448d4a5f9d9b83-3"))
    )
    (comp (ref "CH-J4")
      (value "Molex 22-28-4043")
      (footprint "HEADER_1x4")
      (description "Conn; Rect./PCB; Breakaway Header; 4 Cir.; Vert.; KK 254 Ser.; Gold Plate; 6.09mm Pin L")
      (fields (field (name "MANUFACTURER PART NUMBER") "22-28-4043"))
      (libsource (lib "CommunityVault") (part "CMP-44448d4a5f9d9b83-3"))
    )
    (comp (ref "CH-J5")
      (value "Molex 22-28-4043")
      (footprint "HEADER_1x4")
      (description "Conn; Rect./PCB; Breakaway Header; 4 Cir.; Vert.; KK 254 Ser.; Gold Plate; 6.09mm Pin L")
      (fields (field (name "MANUFACTURER PART NUMBER") "22-28-4043"))
      (libsource (lib "CommunityVault") (part "CMP-44448d4a5f9d9b83-3"))
    )
    (comp (ref "CH-J6")
      (value "Molex 22-28-4043")
      (footprint "HEADER_1x4")
      (description "Conn; Rect./PCB; Breakaway Header; 4 Cir.; Vert.; KK 254 Ser.; Gold Plate; 6.09mm Pin L")
      (fields (field (name "MANUFACTURER PART NUMBER") "22-28-4043"))
      (libsource (lib "CommunityVault") (part "CMP-44448d4a5f9d9b83-3"))
    )
    (comp (ref "CH-J7")
      (value "Molex 22-28-4043")
      (footprint "HEADER_1x4")
      (description "Conn; Rect./PCB; Breakaway Header; 4 Cir.; Vert.; KK 254 Ser.; Gold Plate; 6.09mm Pin L")
      (fields (field (name "MANUFACTURER PART NUMBER") "22-28-4043"))
      (libsource (lib "CommunityVault") (part "CMP-44448d4a5f9d9b83-3"))
    )
    (comp (ref "CH-J8")
      (value "Molex 22-28-4043")
      (footprint "HEADER_1x4")
      (description "Conn; Rect./PCB; Breakaway Header; 4 Cir.; Vert.; KK 254 Ser.; Gold Plate; 6.09mm Pin L")
      (fields (field (name "MANUFACTURER PART NUMBER") "22-28-4043"))
      (libsource (lib "CommunityVault") (part "CMP-44448d4a5f9d9b83-3"))
    )
    (comp (ref "CH-J9")
      (value "Molex 22-28-4043")
      (footprint "HEADER_1x4")
      (description "Conn; Rect./PCB; Breakaway Header; 4 Cir.; Vert.; KK 254 Ser.; Gold Plate; 6.09mm Pin L")
      (fields (field (name "MANUFACTURER PART NUMBER") "22-28-4043"))
      (libsource (lib "CommunityVault") (part "CMP-44448d4a5f9d9b83-3"))
    )
    (comp (ref "DTMP-A")
      (value "Maxim Integrated DS18B20+")
      (footprint "PCB-6xl7qimvuxkxf3clfff9-1")
      (description "DS18B20+ /Maxim Integrated (Dallas)/ Digital temperature sensor, TO-92, -55/+125C, RoHS")
      (fields (field (name "MANUFACTURER PART NUMBER") "DS18B20+"))
      (libsource (lib "CommunityVault") (part "CMP-3808910-8"))
    )
    (comp (ref "DTMP-B")
      (value "Maxim Integrated DS18B20+")
      (footprint "PCB-6xl7qimvuxkxf3clfff9-1")
      (description "DS18B20+ /Maxim Integrated (Dallas)/ Digital temperature sensor, TO-92, -55/+125C, RoHS")
      (fields (field (name "MANUFACTURER PART NUMBER") "DS18B20+"))
      (libsource (lib "CommunityVault") (part "CMP-3808910-8"))
    )
    (comp (ref "DTMP-C")
      (value "Maxim Integrated DS18B20+")
      (footprint "PCB-6xl7qimvuxkxf3clfff9-1")
      (description "DS18B20+ /Maxim Integrated (Dallas)/ Digital temperature sensor, TO-92, -55/+125C, RoHS")
      (fields (field (name "MANUFACTURER PART NUMBER") "DS18B20+"))
      (libsource (lib "CommunityVault") (part "CMP-3808910-8"))
    )
    (comp (ref "DTMP-RES")
      (value "4.7kOhm")
      (footprint "PCB-3trqkg5dul8e4bq69e8d-1")
      (description "Res Metal Film 4.7K Ohm 1% 3/5W ±50ppm/°C Conformal AXL Thru-Hole Ammo Pack")
      (fields (field (name "MANUFACTURER PART NUMBER") "LR1F4K7"))
      (libsource (lib "CommunityVault") (part "CMP-2511ecee5430fad6-2"))
    )
    (comp (ref "GND")
      (value "EM250502V")
      (footprint "PCB-u2v43o1ftwqs3duy389i-1")
      (description "Conn Terminal Block 2 POS 5.08mm Screw ST Cable Mount 16A")
      (libsource (lib "CommunityVault") (part "CMP-9ab5517917744572-4"))
    )
    (comp (ref "GND-A")
      (value "1502-2")
      (footprint "PCB-3pxxqie2fct8emy2m3uy-1")
      (description "Brass Bright Tin Plate .219 inch High for .109 inch Board Width Turret Terminal")
      (libsource (lib "CommunityVault") (part "CMP-0157c85d593dde90-2"))
    )
    (comp (ref "GND-B")
      (value "1502-2")
      (footprint "PCB-3pxxqie2fct8emy2m3uy-1")
      (description "Brass Bright Tin Plate .219 inch High for .109 inch Board Width Turret Terminal")
      (libsource (lib "CommunityVault") (part "CMP-0157c85d593dde90-2"))
    )
    (comp (ref "GND-C")
      (value "1502-2")
      (footprint "PCB-3pxxqie2fct8emy2m3uy-1")
      (description "Brass Bright Tin Plate .219 inch High for .109 inch Board Width Turret Terminal")
      (libsource (lib "CommunityVault") (part "CMP-0157c85d593dde90-2"))
    )
    (comp (ref "GND-D")
      (value "1502-2")
      (footprint "PCB-3pxxqie2fct8emy2m3uy-1")
      (description "Brass Bright Tin Plate .219 inch High for .109 inch Board Width Turret Terminal")
      (libsource (lib "CommunityVault") (part "CMP-0157c85d593dde90-2"))
    )
    (comp (ref "GND-E")
      (value "1502-2")
      (footprint "PCB-3pxxqie2fct8emy2m3uy-1")
      (description "Brass Bright Tin Plate .219 inch High for .109 inch Board Width Turret Terminal")
      (libsource (lib "CommunityVault") (part "CMP-0157c85d593dde90-2"))
    )
    (comp (ref "GND-F")
      (value "1502-2")
      (footprint "PCB-3pxxqie2fct8emy2m3uy-1")
      (description "Brass Bright Tin Plate .219 inch High for .109 inch Board Width Turret Terminal")
      (libsource (lib "CommunityVault") (part "CMP-0157c85d593dde90-2"))
    )
    (comp (ref "GND-G")
      (value "1502-2")
      (footprint "PCB-3pxxqie2fct8emy2m3uy-1")
      (description "Brass Bright Tin Plate .219 inch High for .109 inch Board Width Turret Terminal")
      (libsource (lib "CommunityVault") (part "CMP-0157c85d593dde90-2"))
    )
    (comp (ref "GND-H")
      (value "1502-2")
      (footprint "PCB-3pxxqie2fct8emy2m3uy-1")
      (description "Brass Bright Tin Plate .219 inch High for .109 inch Board Width Turret Terminal")
      (libsource (lib "CommunityVault") (part "CMP-0157c85d593dde90-2"))
    )
    (comp (ref "GND-I")
      (value "1502-2")
      (footprint "PCB-3pxxqie2fct8emy2m3uy-1")
      (description "Brass Bright Tin Plate .219 inch High for .109 inch Board Width Turret Terminal")
      (libsource (lib "CommunityVault") (part "CMP-0157c85d593dde90-2"))
    )
    (comp (ref "GND-J")
      (value "1502-2")
      (footprint "PCB-3pxxqie2fct8emy2m3uy-1")
      (description "Brass Bright Tin Plate .219 inch High for .109 inch Board Width Turret Terminal")
      (libsource (lib "CommunityVault") (part "CMP-0157c85d593dde90-2"))
    )
    (comp (ref "GND-MAIN")
      (value "Keystone 1502-2")
      (footprint "PCB-3pxxqie2fct8emy2m3uy-1")
      (description "Brass Bright Tin Plate .219 inch High for .109 inch Board Width Turret Terminal")
      (fields (field (name "MANUFACTURER PART NUMBER") "1502-2"))
      (libsource (lib "CommunityVault") (part "CMP-0157c85d593dde90-2"))
    )
    (comp (ref "HP-A")
      (value "1502-2")
      (footprint "PCB-3pxxqie2fct8emy2m3uy-1")
      (description "Brass Bright Tin Plate .219 inch High for .109 inch Board Width Turret Terminal")
      (libsource (lib "CommunityVault") (part "CMP-0157c85d593dde90-2"))
    )
    (comp (ref "HP-B")
      (value "1502-2")
      (footprint "PCB-3pxxqie2fct8emy2m3uy-1")
      (description "Brass Bright Tin Plate .219 inch High for .109 inch Board Width Turret Terminal")
      (libsource (lib "CommunityVault") (part "CMP-0157c85d593dde90-2"))
    )
    (comp (ref "HP-C")
      (value "1502-2")
      (footprint "PCB-3pxxqie2fct8emy2m3uy-1")
      (description "Brass Bright Tin Plate .219 inch High for .109 inch Board Width Turret Terminal")
      (libsource (lib "CommunityVault") (part "CMP-0157c85d593dde90-2"))
    )
    (comp (ref "HP-D")
      (value "1502-2")
      (footprint "PCB-3pxxqie2fct8emy2m3uy-1")
      (description "Brass Bright Tin Plate .219 inch High for .109 inch Board Width Turret Terminal")
      (libsource (lib "CommunityVault") (part "CMP-0157c85d593dde90-2"))
    )
    (comp (ref "HP-E")
      (value "1502-2")
      (footprint "PCB-3pxxqie2fct8emy2m3uy-1")
      (description "Brass Bright Tin Plate .219 inch High for .109 inch Board Width Turret Terminal")
      (libsource (lib "CommunityVault") (part "CMP-0157c85d593dde90-2"))
    )
    (comp (ref "HP-F")
      (value "1502-2")
      (footprint "PCB-3pxxqie2fct8emy2m3uy-1")
      (description "Brass Bright Tin Plate .219 inch High for .109 inch Board Width Turret Terminal")
      (libsource (lib "CommunityVault") (part "CMP-0157c85d593dde90-2"))
    )
    (comp (ref "HP-G")
      (value "1502-2")
      (footprint "PCB-3pxxqie2fct8emy2m3uy-1")
      (description "Brass Bright Tin Plate .219 inch High for .109 inch Board Width Turret Terminal")
      (libsource (lib "CommunityVault") (part "CMP-0157c85d593dde90-2"))
    )
    (comp (ref "HP-H")
      (value "1502-2")
      (footprint "PCB-3pxxqie2fct8emy2m3uy-1")
      (description "Brass Bright Tin Plate .219 inch High for .109 inch Board Width Turret Terminal")
      (libsource (lib "CommunityVault") (part "CMP-0157c85d593dde90-2"))
    )
    (comp (ref "HP-I")
      (value "1502-2")
      (footprint "PCB-3pxxqie2fct8emy2m3uy-1")
      (description "Brass Bright Tin Plate .219 inch High for .109 inch Board Width Turret Terminal")
      (libsource (lib "CommunityVault") (part "CMP-0157c85d593dde90-2"))
    )
    (comp (ref "HP-J")
      (value "1502-2")
      (footprint "PCB-3pxxqie2fct8emy2m3uy-1")
      (description "Brass Bright Tin Plate .219 inch High for .109 inch Board Width Turret Terminal")
      (libsource (lib "CommunityVault") (part "CMP-0157c85d593dde90-2"))
    )
    (comp (ref "HP-MAIN")
      (value "Keystone 1502-2")
      (footprint "PCB-3pxxqie2fct8emy2m3uy-1")
      (description "Brass Bright Tin Plate .219 inch High for .109 inch Board Width Turret Terminal")
      (fields (field (name "MANUFACTURER PART NUMBER") "1502-2"))
      (libsource (lib "CommunityVault") (part "CMP-0157c85d593dde90-2"))
    )
    (comp (ref "HPO-A")
      (value "EM250502V")
      (footprint "PCB-u2v43o1ftwqs3duy389i-1")
      (description "Conn Terminal Block 2 POS 5.08mm Screw ST Cable Mount 16A")
      (libsource (lib "CommunityVault") (part "CMP-9ab5517917744572-6"))
    )
    (comp (ref "HPO-B")
      (value "EM250502V")
      (footprint "PCB-u2v43o1ftwqs3duy389i-1")
      (description "Conn Terminal Block 2 POS 5.08mm Screw ST Cable Mount 16A")
      (libsource (lib "CommunityVault") (part "CMP-9ab5517917744572-6"))
    )
    (comp (ref "HPO-C")
      (value "EM250502V")
      (footprint "PCB-u2v43o1ftwqs3duy389i-1")
      (description "Conn Terminal Block 2 POS 5.08mm Screw ST Cable Mount 16A")
      (libsource (lib "CommunityVault") (part "CMP-9ab5517917744572-6"))
    )
    (comp (ref "HPO-D")
      (value "EM250502V")
      (footprint "PCB-u2v43o1ftwqs3duy389i-1")
      (description "Conn Terminal Block 2 POS 5.08mm Screw ST Cable Mount 16A")
      (libsource (lib "CommunityVault") (part "CMP-9ab5517917744572-6"))
    )
    (comp (ref "HPO-E")
      (value "EM250502V")
      (footprint "PCB-u2v43o1ftwqs3duy389i-1")
      (description "Conn Terminal Block 2 POS 5.08mm Screw ST Cable Mount 16A")
      (libsource (lib "CommunityVault") (part "CMP-9ab5517917744572-6"))
    )
    (comp (ref "HPO-F")
      (value "EM250502V")
      (footprint "PCB-u2v43o1ftwqs3duy389i-1")
      (description "Conn Terminal Block 2 POS 5.08mm Screw ST Cable Mount 16A")
      (libsource (lib "CommunityVault") (part "CMP-9ab5517917744572-6"))
    )
    (comp (ref "HPO-G")
      (value "EM250502V")
      (footprint "PCB-u2v43o1ftwqs3duy389i-1")
      (description "Conn Terminal Block 2 POS 5.08mm Screw ST Cable Mount 16A")
      (libsource (lib "CommunityVault") (part "CMP-9ab5517917744572-6"))
    )
    (comp (ref "HPO-H")
      (value "EM250502V")
      (footprint "PCB-u2v43o1ftwqs3duy389i-1")
      (description "Conn Terminal Block 2 POS 5.08mm Screw ST Cable Mount 16A")
      (libsource (lib "CommunityVault") (part "CMP-9ab5517917744572-6"))
    )
    (comp (ref "HPO-I")
      (value "EM250502V")
      (footprint "PCB-u2v43o1ftwqs3duy389i-1")
      (description "Conn Terminal Block 2 POS 5.08mm Screw ST Cable Mount 16A")
      (libsource (lib "CommunityVault") (part "CMP-9ab5517917744572-6"))
    )
    (comp (ref "HPO-J")
      (value "EM250502V")
      (footprint "PCB-u2v43o1ftwqs3duy389i-1")
      (description "Conn Terminal Block 2 POS 5.08mm Screw ST Cable Mount 16A")
      (libsource (lib "CommunityVault") (part "CMP-9ab5517917744572-6"))
    )
    (comp (ref "I2C1")
      (value "Würth Elektronik 61300621121")
      (footprint "PCB-zvoyfznuc9b5lzhitk0z-1")
      (description "THT Vertical Pin Header WR-PHD, Pitch 2.54 mm, Dual Row, 6 pins")
      (fields (field (name "MANUFACTURER PART NUMBER") "61300621121"))
      (libsource (lib "CommunityVault") (part "CMP-8aac4253fa23556b-5"))
    )
    (comp (ref "I2C2")
      (value "Würth Elektronik 61300621121")
      (footprint "PCB-zvoyfznuc9b5lzhitk0z-1")
      (description "THT Vertical Pin Header WR-PHD, Pitch 2.54 mm, Dual Row, 6 pins")
      (fields (field (name "MANUFACTURER PART NUMBER") "61300621121"))
      (libsource (lib "CommunityVault") (part "CMP-8aac4253fa23556b-5"))
    )
    (comp (ref "LP-A")
      (value "1502-2")
      (footprint "PCB-3pxxqie2fct8emy2m3uy-1")
      (description "Brass Bright Tin Plate .219 inch High for .109 inch Board Width Turret Terminal")
      (libsource (lib "CommunityVault") (part "CMP-0157c85d593dde90-2"))
    )
    (comp (ref "LP-B")
      (value "1502-2")
      (footprint "PCB-3pxxqie2fct8emy2m3uy-1")
      (description "Brass Bright Tin Plate .219 inch High for .109 inch Board Width Turret Terminal")
      (libsource (lib "CommunityVault") (part "CMP-0157c85d593dde90-2"))
    )
    (comp (ref "LP-C")
      (value "1502-2")
      (footprint "PCB-3pxxqie2fct8emy2m3uy-1")
      (description "Brass Bright Tin Plate .219 inch High for .109 inch Board Width Turret Terminal")
      (libsource (lib "CommunityVault") (part "CMP-0157c85d593dde90-2"))
    )
    (comp (ref "LP-D")
      (value "1502-2")
      (footprint "PCB-3pxxqie2fct8emy2m3uy-1")
      (description "Brass Bright Tin Plate .219 inch High for .109 inch Board Width Turret Terminal")
      (libsource (lib "CommunityVault") (part "CMP-0157c85d593dde90-2"))
    )
    (comp (ref "LP-E")
      (value "1502-2")
      (footprint "PCB-3pxxqie2fct8emy2m3uy-1")
      (description "Brass Bright Tin Plate .219 inch High for .109 inch Board Width Turret Terminal")
      (libsource (lib "CommunityVault") (part "CMP-0157c85d593dde90-2"))
    )
    (comp (ref "LP-F")
      (value "1502-2")
      (footprint "PCB-3pxxqie2fct8emy2m3uy-1")
      (description "Brass Bright Tin Plate .219 inch High for .109 inch Board Width Turret Terminal")
      (libsource (lib "CommunityVault") (part "CMP-0157c85d593dde90-2"))
    )
    (comp (ref "LP-G")
      (value "1502-2")
      (footprint "PCB-3pxxqie2fct8emy2m3uy-1")
      (description "Brass Bright Tin Plate .219 inch High for .109 inch Board Width Turret Terminal")
      (libsource (lib "CommunityVault") (part "CMP-0157c85d593dde90-2"))
    )
    (comp (ref "LP-H")
      (value "1502-2")
      (footprint "PCB-3pxxqie2fct8emy2m3uy-1")
      (description "Brass Bright Tin Plate .219 inch High for .109 inch Board Width Turret Terminal")
      (libsource (lib "CommunityVault") (part "CMP-0157c85d593dde90-2"))
    )
    (comp (ref "LP-I")
      (value "1502-2")
      (footprint "PCB-3pxxqie2fct8emy2m3uy-1")
      (description "Brass Bright Tin Plate .219 inch High for .109 inch Board Width Turret Terminal")
      (libsource (lib "CommunityVault") (part "CMP-0157c85d593dde90-2"))
    )
    (comp (ref "LP-J")
      (value "1502-2")
      (footprint "PCB-3pxxqie2fct8emy2m3uy-1")
      (description "Brass Bright Tin Plate .219 inch High for .109 inch Board Width Turret Terminal")
      (libsource (lib "CommunityVault") (part "CMP-0157c85d593dde90-2"))
    )
    (comp (ref "LP-MAIN")
      (value "Keystone 1502-2")
      (footprint "PCB-3pxxqie2fct8emy2m3uy-1")
      (description "Brass Bright Tin Plate .219 inch High for .109 inch Board Width Turret Terminal")
      (fields (field (name "MANUFACTURER PART NUMBER") "1502-2"))
      (libsource (lib "CommunityVault") (part "CMP-0157c85d593dde90-2"))
    )
    (comp (ref "PUR-SCL2")
      (value "4.7kOhm")
      (footprint "PCB-3trqkg5dul8e4bq69e8d-1")
      (description "Res Metal Film 4.7K Ohm 1% 3/5W ±50ppm/°C Conformal AXL Thru-Hole Ammo Pack")
      (fields (field (name "MANUFACTURER PART NUMBER") "LR1F4K7"))
      (libsource (lib "CommunityVault") (part "CMP-2511ecee5430fad6-2"))
    )
    (comp (ref "PUR-SDA1")
      (value "4.7kOhm")
      (footprint "PCB-3trqkg5dul8e4bq69e8d-1")
      (description "Res Metal Film 4.7K Ohm 1% 3/5W ±50ppm/°C Conformal AXL Thru-Hole Ammo Pack")
      (fields (field (name "MANUFACTURER PART NUMBER") "LR1F4K7"))
      (libsource (lib "CommunityVault") (part "CMP-2511ecee5430fad6-2"))
    )
    (comp (ref "PUR-SDA2")
      (value "4.7kOhm")
      (footprint "PCB-3trqkg5dul8e4bq69e8d-1")
      (description "Res Metal Film 4.7K Ohm 1% 3/5W ±50ppm/°C Conformal AXL Thru-Hole Ammo Pack")
      (fields (field (name "MANUFACTURER PART NUMBER") "LR1F4K7"))
      (libsource (lib "CommunityVault") (part "CMP-2511ecee5430fad6-2"))
    )
    (comp (ref "PUR-SLC1")
      (value "4.7kOhm")
      (footprint "PCB-3trqkg5dul8e4bq69e8d-1")
      (description "Res Metal Film 4.7K Ohm 1% 3/5W ±50ppm/°C Conformal AXL Thru-Hole Ammo Pack")
      (fields (field (name "MANUFACTURER PART NUMBER") "LR1F4K7"))
      (libsource (lib "CommunityVault") (part "CMP-2511ecee5430fad6-2"))
    )
    (comp (ref "P_IN")
      (value "EM250502V")
      (footprint "PCB-u2v43o1ftwqs3duy389i-1")
      (description "Conn Terminal Block 2 POS 5.08mm Screw ST Cable Mount 16A")
      (libsource (lib "") (part "CMP-9ab5517917744572-4_1"))
    )
    (comp (ref "RPI")
      (value "Raspberry Pi 2+/3")
      (footprint "Header Only")
      (description "Dev Brd, Rpi Model b, Bcm2835 Processor")
      (libsource (lib "CommunityVault") (part "CMP-e7ab2d993b99386c-20"))
    )
    (comp (ref "S-A")
      (value "SYM-dgd04bf3j3drhl5uyyz7-1")
      (footprint "PCBComponent_1 - duplicate")
      (description "CONN DIN RCPT 64POS PCB GOLD")
      (libsource (lib "CommunityVault") (part "CMP-dgd04bf3j3drhl5uyyz7-27"))
    )
    (comp (ref "S-B")
      (value "SYM-dgd04bf3j3drhl5uyyz7-1")
      (footprint "PCBComponent_1 - duplicate")
      (description "CONN DIN RCPT 64POS PCB GOLD")
      (libsource (lib "CommunityVault") (part "CMP-dgd04bf3j3drhl5uyyz7-27"))
    )
    (comp (ref "S-C")
      (value "SYM-dgd04bf3j3drhl5uyyz7-1")
      (footprint "PCBComponent_1 - duplicate")
      (description "CONN DIN RCPT 64POS PCB GOLD")
      (libsource (lib "CommunityVault") (part "CMP-dgd04bf3j3drhl5uyyz7-27"))
    )
    (comp (ref "S-D")
      (value "SYM-dgd04bf3j3drhl5uyyz7-1")
      (footprint "PCBComponent_1 - duplicate")
      (description "CONN DIN RCPT 64POS PCB GOLD")
      (libsource (lib "CommunityVault") (part "CMP-dgd04bf3j3drhl5uyyz7-27"))
    )
    (comp (ref "S-E")
      (value "SYM-dgd04bf3j3drhl5uyyz7-1")
      (footprint "PCBComponent_1 - duplicate")
      (description "CONN DIN RCPT 64POS PCB GOLD")
      (libsource (lib "CommunityVault") (part "CMP-dgd04bf3j3drhl5uyyz7-27"))
    )
    (comp (ref "S-F")
      (value "SYM-dgd04bf3j3drhl5uyyz7-1")
      (footprint "PCBComponent_1 - duplicate")
      (description "CONN DIN RCPT 64POS PCB GOLD")
      (libsource (lib "CommunityVault") (part "CMP-dgd04bf3j3drhl5uyyz7-27"))
    )
    (comp (ref "S-G")
      (value "SYM-dgd04bf3j3drhl5uyyz7-1")
      (footprint "PCBComponent_1 - duplicate")
      (description "CONN DIN RCPT 64POS PCB GOLD")
      (libsource (lib "CommunityVault") (part "CMP-dgd04bf3j3drhl5uyyz7-27"))
    )
    (comp (ref "S-H")
      (value "SYM-dgd04bf3j3drhl5uyyz7-1")
      (footprint "PCBComponent_1 - duplicate")
      (description "CONN DIN RCPT 64POS PCB GOLD")
      (libsource (lib "CommunityVault") (part "CMP-dgd04bf3j3drhl5uyyz7-27"))
    )
    (comp (ref "S-I")
      (value "SYM-dgd04bf3j3drhl5uyyz7-1")
      (footprint "PCBComponent_1 - duplicate")
      (description "CONN DIN RCPT 64POS PCB GOLD")
      (libsource (lib "CommunityVault") (part "CMP-dgd04bf3j3drhl5uyyz7-27"))
    )
    (comp (ref "S-J")
      (value "SYM-dgd04bf3j3drhl5uyyz7-1")
      (footprint "PCBComponent_1 - duplicate")
      (description "CONN DIN RCPT 64POS PCB GOLD")
      (libsource (lib "CommunityVault") (part "CMP-dgd04bf3j3drhl5uyyz7-27"))
    )
    (comp (ref "TMP36-1")
      (value "TMP36GT9")
      (footprint "ADI-T-3")
      (description "Low Voltage Temperature Sensor, 2.7 to 5.5 V Supply, Industrial, 3-pin TO92 (T-3), Tray")
      (libsource (lib "CommunityVault") (part "CMP-2418272-2"))
    )
    (comp (ref "TMP36-2")
      (value "TMP36GT9")
      (footprint "ADI-T-3")
      (description "Low Voltage Temperature Sensor, 2.7 to 5.5 V Supply, Industrial, 3-pin TO92 (T-3), Tray")
      (libsource (lib "CommunityVault") (part "CMP-2418272-2"))
    )
    (comp (ref "TMP36-3")
      (value "TMP36GT9")
      (footprint "ADI-T-3")
      (description "Low Voltage Temperature Sensor, 2.7 to 5.5 V Supply, Industrial, 3-pin TO92 (T-3), Tray")
      (libsource (lib "CommunityVault") (part "CMP-2418272-2"))
    )
  )
  (nets
    (net (code "1") (name "Net-(AUNO-Pad3.3V)") (class "Default")
      (node (ref "AUNO") (pin "3.3V") (pinfunction "3.3V_3.3V") (pintype "passive"))
      (node (ref "PUR-SDA1") (pin "2") (pinfunction "2_2") (pintype "passive"))
      (node (ref "PUR-SLC1") (pin "2") (pinfunction "2_2") (pintype "passive"))
    )
    (net (code "2") (name "Net-(AUNO-PadSCL)") (class "Default")
      (node (ref "AUNO") (pin "SCL") (pinfunction "SCL_SCL") (pintype "passive"))
      (node (ref "I2C1") (pin "2") (pinfunction "2_2") (pintype "passive"))
      (node (ref "I2C2") (pin "2") (pinfunction "2_2") (pintype "passive"))
      (node (ref "PUR-SDA1") (pin "1") (pinfunction "1_1") (pintype "passive"))
    )
    (net (code "3") (name "Net-(AUNO-PadSDA)") (class "Default")
      (node (ref "AUNO") (pin "SDA") (pinfunction "SDA_SDA") (pintype "passive"))
      (node (ref "I2C1") (pin "1") (pinfunction "1_1") (pintype "passive"))
      (node (ref "I2C2") (pin "1") (pinfunction "1_1") (pintype "passive"))
      (node (ref "PUR-SLC1") (pin "1") (pinfunction "1_1") (pintype "passive"))
    )
    (net (code "4") (name "Net-(AUNO-~D3)") (class "Default")
      (node (ref "AUNO") (pin "D3") (pinfunction "~D3_D3") (pintype "passive"))
      (node (ref "S-B") (pin "C16") (pinfunction "ARD_C16") (pintype "passive"))
    )
    (net (code "5") (name "Net-(AUNO-~D5)") (class "Default")
      (node (ref "AUNO") (pin "D5") (pinfunction "~D5_D5") (pintype "passive"))
      (node (ref "S-D") (pin "C16") (pinfunction "ARD_C16") (pintype "passive"))
    )
    (net (code "6") (name "Net-(AUNO-~D6)") (class "Default")
      (node (ref "AUNO") (pin "D6") (pinfunction "~D6_D6") (pintype "passive"))
      (node (ref "S-E") (pin "C16") (pinfunction "ARD_C16") (pintype "passive"))
    )
    (net (code "7") (name "Net-(AUNO-~D9)") (class "Default")
      (node (ref "AUNO") (pin "D9") (pinfunction "~D9_D9") (pintype "passive"))
      (node (ref "S-H") (pin "C16") (pinfunction "ARD_C16") (pintype "passive"))
    )
    (net (code "8") (name "Net-(AUNO-~D10)") (class "Default")
      (node (ref "AUNO") (pin "D10") (pinfunction "~D10_D10") (pintype "passive"))
      (node (ref "S-I") (pin "C16") (pinfunction "ARD_C16") (pintype "passive"))
    )
    (net (code "9") (name "Net-(AUNO-~D11)") (class "Default")
      (node (ref "AUNO") (pin "D11") (pinfunction "~D11_D11") (pintype "passive"))
      (node (ref "S-J") (pin "C16") (pinfunction "ARD_C16") (pintype "passive"))
    )
    (net (code "10") (name "Net-(DTMP-A-DQ)") (class "Default")
      (node (ref "DTMP-A") (pin "2") (pinfunction "DQ_2") (pintype "passive"))
      (node (ref "DTMP-B") (pin "2") (pinfunction "DQ_2") (pintype "passive"))
      (node (ref "DTMP-C") (pin "2") (pinfunction "DQ_2") (pintype "passive"))
      (node (ref "DTMP-RES") (pin "2") (pinfunction "2_2") (pintype "passive"))
      (node (ref "RPI") (pin "7") (pinfunction "GPIO_04_(GPIO_GCLK)_7") (pintype "passive"))
    )
    (net (code "11") (name "Net-(DTMP-A-GND)") (class "Default")
      (node (ref "AUNO") (pin "GND2") (pinfunction "GND_GND2") (pintype "passive"))
      (node (ref "DTMP-A") (pin "1") (pinfunction "GND_1") (pintype "passive"))
      (node (ref "DTMP-B") (pin "1") (pinfunction "GND_1") (pintype "passive"))
      (node (ref "DTMP-C") (pin "1") (pinfunction "GND_1") (pintype "passive"))
      (node (ref "GND") (pin "A") (pinfunction "A_A") (pintype "passive"))
      (node (ref "GND") (pin "B") (pinfunction "B_B") (pintype "passive"))
      (node (ref "GND-A") (pin "1") (pinfunction "T_1") (pintype "passive"))
      (node (ref "GND-B") (pin "1") (pinfunction "T_1") (pintype "passive"))
      (node (ref "GND-C") (pin "1") (pinfunction "T_1") (pintype "passive"))
      (node (ref "GND-D") (pin "1") (pinfunction "T_1") (pintype "passive"))
      (node (ref "GND-E") (pin "1") (pinfunction "T_1") (pintype "passive"))
      (node (ref "GND-F") (pin "1") (pinfunction "T_1") (pintype "passive"))
      (node (ref "GND-G") (pin "1") (pinfunction "T_1") (pintype "passive"))
      (node (ref "GND-H") (pin "1") (pinfunction "T_1") (pintype "passive"))
      (node (ref "GND-I") (pin "1") (pinfunction "T_1") (pintype "passive"))
      (node (ref "GND-J") (pin "1") (pinfunction "T_1") (pintype "passive"))
      (node (ref "GND-MAIN") (pin "1") (pinfunction "T_1") (pintype "passive"))
      (node (ref "RPI") (pin "34") (pinfunction "GND_34") (pintype "passive"))
      (node (ref "S-A") (pin "A13") (pinfunction "GND_A13") (pintype "passive"))
      (node (ref "S-A") (pin "A18") (pinfunction "GND_A18") (pintype "passive"))
      (node (ref "S-A") (pin "B13") (pinfunction "GND_B13") (pintype "passive"))
      (node (ref "S-A") (pin "B18") (pinfunction "GND_B18") (pintype "passive"))
      (node (ref "S-A") (pin "C13") (pinfunction "GND_C13") (pintype "passive"))
      (node (ref "S-A") (pin "C18") (pinfunction "GND_C18") (pintype "passive"))
      (node (ref "S-A") (pin "HPIB") (pinfunction "GND_HPIB") (pintype "passive"))
      (node (ref "S-B") (pin "A13") (pinfunction "GND_A13") (pintype "passive"))
      (node (ref "S-B") (pin "A18") (pinfunction "GND_A18") (pintype "passive"))
      (node (ref "S-B") (pin "B13") (pinfunction "GND_B13") (pintype "passive"))
      (node (ref "S-B") (pin "B18") (pinfunction "GND_B18") (pintype "passive"))
      (node (ref "S-B") (pin "C13") (pinfunction "GND_C13") (pintype "passive"))
      (node (ref "S-B") (pin "C18") (pinfunction "GND_C18") (pintype "passive"))
      (node (ref "S-B") (pin "HPIB") (pinfunction "GND_HPIB") (pintype "passive"))
      (node (ref "S-C") (pin "A13") (pinfunction "GND_A13") (pintype "passive"))
      (node (ref "S-C") (pin "A18") (pinfunction "GND_A18") (pintype "passive"))
      (node (ref "S-C") (pin "B13") (pinfunction "GND_B13") (pintype "passive"))
      (node (ref "S-C") (pin "B18") (pinfunction "GND_B18") (pintype "passive"))
      (node (ref "S-C") (pin "C13") (pinfunction "GND_C13") (pintype "passive"))
      (node (ref "S-C") (pin "C18") (pinfunction "GND_C18") (pintype "passive"))
      (node (ref "S-C") (pin "HPIB") (pinfunction "GND_HPIB") (pintype "passive"))
      (node (ref "S-D") (pin "A13") (pinfunction "GND_A13") (pintype "passive"))
      (node (ref "S-D") (pin "A18") (pinfunction "GND_A18") (pintype "passive"))
      (node (ref "S-D") (pin "B13") (pinfunction "GND_B13") (pintype "passive"))
      (node (ref "S-D") (pin "B18") (pinfunction "GND_B18") (pintype "passive"))
      (node (ref "S-D") (pin "C13") (pinfunction "GND_C13") (pintype "passive"))
      (node (ref "S-D") (pin "C18") (pinfunction "GND_C18") (pintype "passive"))
      (node (ref "S-D") (pin "HPIB") (pinfunction "GND_HPIB") (pintype "passive"))
      (node (ref "S-E") (pin "A13") (pinfunction "GND_A13") (pintype "passive"))
      (node (ref "S-E") (pin "A18") (pinfunction "GND_A18") (pintype "passive"))
      (node (ref "S-E") (pin "B13") (pinfunction "GND_B13") (pintype "passive"))
      (node (ref "S-E") (pin "B18") (pinfunction "GND_B18") (pintype "passive"))
      (node (ref "S-E") (pin "C13") (pinfunction "GND_C13") (pintype "passive"))
      (node (ref "S-E") (pin "C18") (pinfunction "GND_C18") (pintype "passive"))
      (node (ref "S-E") (pin "HPIB") (pinfunction "GND_HPIB") (pintype "passive"))
      (node (ref "S-F") (pin "A13") (pinfunction "GND_A13") (pintype "passive"))
      (node (ref "S-F") (pin "A18") (pinfunction "GND_A18") (pintype "passive"))
      (node (ref "S-F") (pin "B13") (pinfunction "GND_B13") (pintype "passive"))
      (node (ref "S-F") (pin "B18") (pinfunction "GND_B18") (pintype "passive"))
      (node (ref "S-F") (pin "C13") (pinfunction "GND_C13") (pintype "passive"))
      (node (ref "S-F") (pin "C18") (pinfunction "GND_C18") (pintype "passive"))
      (node (ref "S-F") (pin "HPIB") (pinfunction "GND_HPIB") (pintype "passive"))
      (node (ref "S-G") (pin "A13") (pinfunction "GND_A13") (pintype "passive"))
      (node (ref "S-G") (pin "A18") (pinfunction "GND_A18") (pintype "passive"))
      (node (ref "S-G") (pin "B13") (pinfunction "GND_B13") (pintype "passive"))
      (node (ref "S-G") (pin "B18") (pinfunction "GND_B18") (pintype "passive"))
      (node (ref "S-G") (pin "C13") (pinfunction "GND_C13") (pintype "passive"))
      (node (ref "S-G") (pin "C18") (pinfunction "GND_C18") (pintype "passive"))
      (node (ref "S-G") (pin "HPIB") (pinfunction "GND_HPIB") (pintype "passive"))
      (node (ref "S-H") (pin "A13") (pinfunction "GND_A13") (pintype "passive"))
      (node (ref "S-H") (pin "A18") (pinfunction "GND_A18") (pintype "passive"))
      (node (ref "S-H") (pin "B13") (pinfunction "GND_B13") (pintype "passive"))
      (node (ref "S-H") (pin "B18") (pinfunction "GND_B18") (pintype "passive"))
      (node (ref "S-H") (pin "C13") (pinfunction "GND_C13") (pintype "passive"))
      (node (ref "S-H") (pin "C18") (pinfunction "GND_C18") (pintype "passive"))
      (node (ref "S-H") (pin "HPIB") (pinfunction "GND_HPIB") (pintype "passive"))
      (node (ref "S-I") (pin "A13") (pinfunction "GND_A13") (pintype "passive"))
      (node (ref "S-I") (pin "A18") (pinfunction "GND_A18") (pintype "passive"))
      (node (ref "S-I") (pin "B13") (pinfunction "GND_B13") (pintype "passive"))
      (node (ref "S-I") (pin "B18") (pinfunction "GND_B18") (pintype "passive"))
      (node (ref "S-I") (pin "C13") (pinfunction "GND_C13") (pintype "passive"))
      (node (ref "S-I") (pin "C18") (pinfunction "GND_C18") (pintype "passive"))
      (node (ref "S-I") (pin "HPIB") (pinfunction "GND_HPIB") (pintype "passive"))
      (node (ref "S-J") (pin "A13") (pinfunction "GND_A13") (pintype "passive"))
      (node (ref "S-J") (pin "A18") (pinfunction "GND_A18") (pintype "passive"))
      (node (ref "S-J") (pin "B13") (pinfunction "GND_B13") (pintype "passive"))
      (node (ref "S-J") (pin "B18") (pinfunction "GND_B18") (pintype "passive"))
      (node (ref "S-J") (pin "C13") (pinfunction "GND_C13") (pintype "passive"))
      (node (ref "S-J") (pin "C18") (pinfunction "GND_C18") (pintype "passive"))
      (node (ref "S-J") (pin "HPIB") (pinfunction "GND_HPIB") (pintype "passive"))
      (node (ref "TMP36-1") (pin "3") (pinfunction "GND_3") (pintype "power_in"))
      (node (ref "TMP36-2") (pin "3") (pinfunction "GND_3") (pintype "power_in"))
      (node (ref "TMP36-3") (pin "3") (pinfunction "GND_3") (pintype "power_in"))
    )
    (net (code "12") (name "Net-(DTMP-A-UDD)") (class "Default")
      (node (ref "DTMP-A") (pin "3") (pinfunction "UDD_3") (pintype "passive"))
      (node (ref "DTMP-B") (pin "3") (pinfunction "UDD_3") (pintype "passive"))
      (node (ref "DTMP-C") (pin "3") (pinfunction "UDD_3") (pintype "passive"))
      (node (ref "DTMP-RES") (pin "1") (pinfunction "1_1") (pintype "passive"))
      (node (ref "PUR-SCL2") (pin "1") (pinfunction "1_1") (pintype "passive"))
      (node (ref "PUR-SDA2") (pin "1") (pinfunction "1_1") (pintype "passive"))
      (node (ref "RPI") (pin "1") (pinfunction "3.3V_1") (pintype "passive"))
    )
    (net (code "13") (name "Net-(HP-A-T)") (class "Default")
      (node (ref "HP-A") (pin "1") (pinfunction "T_1") (pintype "passive"))
      (node (ref "HP-B") (pin "1") (pinfunction "T_1") (pintype "passive"))
      (node (ref "HP-C") (pin "1") (pinfunction "T_1") (pintype "passive"))
      (node (ref "HP-D") (pin "1") (pinfunction "T_1") (pintype "passive"))
      (node (ref "HP-E") (pin "1") (pinfunction "T_1") (pintype "passive"))
      (node (ref "HP-F") (pin "1") (pinfunction "T_1") (pintype "passive"))
      (node (ref "HP-G") (pin "1") (pinfunction "T_1") (pintype "passive"))
      (node (ref "HP-H") (pin "1") (pinfunction "T_1") (pintype "passive"))
      (node (ref "HP-I") (pin "1") (pinfunction "T_1") (pintype "passive"))
      (node (ref "HP-J") (pin "1") (pinfunction "T_1") (pintype "passive"))
      (node (ref "HP-MAIN") (pin "1") (pinfunction "T_1") (pintype "passive"))
      (node (ref "P_IN") (pin "A") (pinfunction "A_A") (pintype "passive"))
      (node (ref "S-A") (pin "HPIA") (pinfunction "HPIA_HPIA") (pintype "passive"))
      (node (ref "S-B") (pin "HPIA") (pinfunction "HPIA_HPIA") (pintype "passive"))
      (node (ref "S-C") (pin "HPIA") (pinfunction "HPIA_HPIA") (pintype "passive"))
      (node (ref "S-D") (pin "HPIA") (pinfunction "HPIA_HPIA") (pintype "passive"))
      (node (ref "S-E") (pin "HPIA") (pinfunction "HPIA_HPIA") (pintype "passive"))
      (node (ref "S-F") (pin "HPIA") (pinfunction "HPIA_HPIA") (pintype "passive"))
      (node (ref "S-G") (pin "HPIA") (pinfunction "HPIA_HPIA") (pintype "passive"))
      (node (ref "S-H") (pin "HPIA") (pinfunction "HPIA_HPIA") (pintype "passive"))
      (node (ref "S-I") (pin "HPIA") (pinfunction "HPIA_HPIA") (pintype "passive"))
      (node (ref "S-J") (pin "HPIA") (pinfunction "HPIA_HPIA") (pintype "passive"))
    )
    (net (code "14") (name "Net-(HPO-A-PadA)") (class "Default")
      (node (ref "HPO-A") (pin "A") (pinfunction "A_A") (pintype "passive"))
      (node (ref "S-A") (pin "HPOA") (pinfunction "HPOA_HPOA") (pintype "passive"))
    )
    (net (code "15") (name "Net-(HPO-A-PadB)") (class "Default")
      (node (ref "HPO-A") (pin "B") (pinfunction "B_B") (pintype "passive"))
      (node (ref "S-A") (pin "HPOB") (pinfunction "HPOB_HPOB") (pintype "passive"))
    )
    (net (code "16") (name "Net-(HPO-B-PadA)") (class "Default")
      (node (ref "HPO-B") (pin "A") (pinfunction "A_A") (pintype "passive"))
      (node (ref "S-B") (pin "HPOA") (pinfunction "HPOA_HPOA") (pintype "passive"))
    )
    (net (code "17") (name "Net-(HPO-B-PadB)") (class "Default")
      (node (ref "HPO-B") (pin "B") (pinfunction "B_B") (pintype "passive"))
      (node (ref "S-B") (pin "HPOB") (pinfunction "HPOB_HPOB") (pintype "passive"))
    )
    (net (code "18") (name "Net-(HPO-C-PadA)") (class "Default")
      (node (ref "HPO-C") (pin "A") (pinfunction "A_A") (pintype "passive"))
      (node (ref "S-C") (pin "HPOA") (pinfunction "HPOA_HPOA") (pintype "passive"))
    )
    (net (code "19") (name "Net-(HPO-C-PadB)") (class "Default")
      (node (ref "HPO-C") (pin "B") (pinfunction "B_B") (pintype "passive"))
      (node (ref "S-C") (pin "HPOB") (pinfunction "HPOB_HPOB") (pintype "passive"))
    )
    (net (code "20") (name "Net-(HPO-D-PadA)") (class "Default")
      (node (ref "HPO-D") (pin "A") (pinfunction "A_A") (pintype "passive"))
      (node (ref "S-D") (pin "HPOA") (pinfunction "HPOA_HPOA") (pintype "passive"))
    )
    (net (code "21") (name "Net-(HPO-D-PadB)") (class "Default")
      (node (ref "HPO-D") (pin "B") (pinfunction "B_B") (pintype "passive"))
      (node (ref "S-D") (pin "HPOB") (pinfunction "HPOB_HPOB") (pintype "passive"))
    )
    (net (code "22") (name "Net-(HPO-E-PadA)") (class "Default")
      (node (ref "HPO-E") (pin "A") (pinfunction "A_A") (pintype "passive"))
      (node (ref "S-E") (pin "HPOA") (pinfunction "HPOA_HPOA") (pintype "passive"))
    )
    (net (code "23") (name "Net-(HPO-E-PadB)") (class "Default")
      (node (ref "HPO-E") (pin "B") (pinfunction "B_B") (pintype "passive"))
      (node (ref "S-E") (pin "HPOB") (pinfunction "HPOB_HPOB") (pintype "passive"))
    )
    (net (code "24") (name "Net-(HPO-F-PadA)") (class "Default")
      (node (ref "HPO-F") (pin "A") (pinfunction "A_A") (pintype "passive"))
      (node (ref "S-F") (pin "HPOA") (pinfunction "HPOA_HPOA") (pintype "passive"))
    )
    (net (code "25") (name "Net-(HPO-F-PadB)") (class "Default")
      (node (ref "HPO-F") (pin "B") (pinfunction "B_B") (pintype "passive"))
      (node (ref "S-F") (pin "HPOB") (pinfunction "HPOB_HPOB") (pintype "passive"))
    )
    (net (code "26") (name "Net-(HPO-G-PadA)") (class "Default")
      (node (ref "HPO-G") (pin "A") (pinfunction "A_A") (pintype "passive"))
      (node (ref "S-G") (pin "HPOA") (pinfunction "HPOA_HPOA") (pintype "passive"))
    )
    (net (code "27") (name "Net-(HPO-G-PadB)") (class "Default")
      (node (ref "HPO-G") (pin "B") (pinfunction "B_B") (pintype "passive"))
      (node (ref "S-G") (pin "HPOB") (pinfunction "HPOB_HPOB") (pintype "passive"))
    )
    (net (code "28") (name "Net-(HPO-H-PadA)") (class "Default")
      (node (ref "HPO-H") (pin "A") (pinfunction "A_A") (pintype "passive"))
      (node (ref "S-H") (pin "HPOA") (pinfunction "HPOA_HPOA") (pintype "passive"))
    )
    (net (code "29") (name "Net-(HPO-H-PadB)") (class "Default")
      (node (ref "HPO-H") (pin "B") (pinfunction "B_B") (pintype "passive"))
      (node (ref "S-H") (pin "HPOB") (pinfunction "HPOB_HPOB") (pintype "passive"))
    )
    (net (code "30") (name "Net-(HPO-I-PadA)") (class "Default")
      (node (ref "HPO-I") (pin "A") (pinfunction "A_A") (pintype "passive"))
      (node (ref "S-I") (pin "HPOA") (pinfunction "HPOA_HPOA") (pintype "passive"))
    )
    (net (code "31") (name "Net-(HPO-I-PadB)") (class "Default")
      (node (ref "HPO-I") (pin "B") (pinfunction "B_B") (pintype "passive"))
      (node (ref "S-I") (pin "HPOB") (pinfunction "HPOB_HPOB") (pintype "passive"))
    )
    (net (code "32") (name "Net-(HPO-J-PadA)") (class "Default")
      (node (ref "HPO-J") (pin "A") (pinfunction "A_A") (pintype "passive"))
      (node (ref "S-J") (pin "HPOA") (pinfunction "HPOA_HPOA") (pintype "passive"))
    )
    (net (code "33") (name "Net-(HPO-J-PadB)") (class "Default")
      (node (ref "HPO-J") (pin "B") (pinfunction "B_B") (pintype "passive"))
      (node (ref "S-J") (pin "HPOB") (pinfunction "HPOB_HPOB") (pintype "passive"))
    )
    (net (code "34") (name "Net-(LP-A-T)") (class "Default")
      (node (ref "AUNO") (pin "5V") (pinfunction "5V_5V") (pintype "passive"))
      (node (ref "LP-A") (pin "1") (pinfunction "T_1") (pintype "passive"))
      (node (ref "LP-B") (pin "1") (pinfunction "T_1") (pintype "passive"))
      (node (ref "LP-C") (pin "1") (pinfunction "T_1") (pintype "passive"))
      (node (ref "LP-D") (pin "1") (pinfunction "T_1") (pintype "passive"))
      (node (ref "LP-E") (pin "1") (pinfunction "T_1") (pintype "passive"))
      (node (ref "LP-F") (pin "1") (pinfunction "T_1") (pintype "passive"))
      (node (ref "LP-G") (pin "1") (pinfunction "T_1") (pintype "passive"))
      (node (ref "LP-H") (pin "1") (pinfunction "T_1") (pintype "passive"))
      (node (ref "LP-I") (pin "1") (pinfunction "T_1") (pintype "passive"))
      (node (ref "LP-J") (pin "1") (pinfunction "T_1") (pintype "passive"))
      (node (ref "LP-MAIN") (pin "1") (pinfunction "T_1") (pintype "passive"))
      (node (ref "P_IN") (pin "B") (pinfunction "B_B") (pintype "passive"))
      (node (ref "RPI") (pin "4") (pinfunction "5V_4") (pintype "passive"))
      (node (ref "S-A") (pin "A19") (pinfunction "PW2_A19") (pintype "passive"))
      (node (ref "S-A") (pin "A20") (pinfunction "PW1_A20") (pintype "passive"))
      (node (ref "S-A") (pin "B19") (pinfunction "PW2_B19") (pintype "passive"))
      (node (ref "S-A") (pin "B20") (pinfunction "PW1_B20") (pintype "passive"))
      (node (ref "S-A") (pin "C19") (pinfunction "PW2_C19") (pintype "passive"))
      (node (ref "S-A") (pin "C20") (pinfunction "PW1_C20") (pintype "passive"))
      (node (ref "S-B") (pin "A19") (pinfunction "PW2_A19") (pintype "passive"))
      (node (ref "S-B") (pin "A20") (pinfunction "PW1_A20") (pintype "passive"))
      (node (ref "S-B") (pin "B19") (pinfunction "PW2_B19") (pintype "passive"))
      (node (ref "S-B") (pin "B20") (pinfunction "PW1_B20") (pintype "passive"))
      (node (ref "S-B") (pin "C19") (pinfunction "PW2_C19") (pintype "passive"))
      (node (ref "S-B") (pin "C20") (pinfunction "PW1_C20") (pintype "passive"))
      (node (ref "S-C") (pin "A19") (pinfunction "PW2_A19") (pintype "passive"))
      (node (ref "S-C") (pin "A20") (pinfunction "PW1_A20") (pintype "passive"))
      (node (ref "S-C") (pin "B19") (pinfunction "PW2_B19") (pintype "passive"))
      (node (ref "S-C") (pin "B20") (pinfunction "PW1_B20") (pintype "passive"))
      (node (ref "S-C") (pin "C19") (pinfunction "PW2_C19") (pintype "passive"))
      (node (ref "S-C") (pin "C20") (pinfunction "PW1_C20") (pintype "passive"))
      (node (ref "S-D") (pin "A19") (pinfunction "PW2_A19") (pintype "passive"))
      (node (ref "S-D") (pin "A20") (pinfunction "PW1_A20") (pintype "passive"))
      (node (ref "S-D") (pin "B19") (pinfunction "PW2_B19") (pintype "passive"))
      (node (ref "S-D") (pin "B20") (pinfunction "PW1_B20") (pintype "passive"))
      (node (ref "S-D") (pin "C19") (pinfunction "PW2_C19") (pintype "passive"))
      (node (ref "S-D") (pin "C20") (pinfunction "PW1_C20") (pintype "passive"))
      (node (ref "S-E") (pin "A19") (pinfunction "PW2_A19") (pintype "passive"))
      (node (ref "S-E") (pin "A20") (pinfunction "PW1_A20") (pintype "passive"))
      (node (ref "S-E") (pin "B19") (pinfunction "PW2_B19") (pintype "passive"))
      (node (ref "S-E") (pin "B20") (pinfunction "PW1_B20") (pintype "passive"))
      (node (ref "S-E") (pin "C19") (pinfunction "PW2_C19") (pintype "passive"))
      (node (ref "S-E") (pin "C20") (pinfunction "PW1_C20") (pintype "passive"))
      (node (ref "S-F") (pin "A19") (pinfunction "PW2_A19") (pintype "passive"))
      (node (ref "S-F") (pin "A20") (pinfunction "PW1_A20") (pintype "passive"))
      (node (ref "S-F") (pin "B19") (pinfunction "PW2_B19") (pintype "passive"))
      (node (ref "S-F") (pin "B20") (pinfunction "PW1_B20") (pintype "passive"))
      (node (ref "S-F") (pin "C19") (pinfunction "PW2_C19") (pintype "passive"))
      (node (ref "S-F") (pin "C20") (pinfunction "PW1_C20") (pintype "passive"))
      (node (ref "S-G") (pin "A19") (pinfunction "PW2_A19") (pintype "passive"))
      (node (ref "S-G") (pin "A20") (pinfunction "PW1_A20") (pintype "passive"))
      (node (ref "S-G") (pin "B19") (pinfunction "PW2_B19") (pintype "passive"))
      (node (ref "S-G") (pin "B20") (pinfunction "PW1_B20") (pintype "passive"))
      (node (ref "S-G") (pin "C19") (pinfunction "PW2_C19") (pintype "passive"))
      (node (ref "S-G") (pin "C20") (pinfunction "PW1_C20") (pintype "passive"))
      (node (ref "S-H") (pin "A19") (pinfunction "PW2_A19") (pintype "passive"))
      (node (ref "S-H") (pin "A20") (pinfunction "PW1_A20") (pintype "passive"))
      (node (ref "S-H") (pin "B19") (pinfunction "PW2_B19") (pintype "passive"))
      (node (ref "S-H") (pin "B20") (pinfunction "PW1_B20") (pintype "passive"))
      (node (ref "S-H") (pin "C19") (pinfunction "PW2_C19") (pintype "passive"))
      (node (ref "S-H") (pin "C20") (pinfunction "PW1_C20") (pintype "passive"))
      (node (ref "S-I") (pin "A19") (pinfunction "PW2_A19") (pintype "passive"))
      (node (ref "S-I") (pin "A20") (pinfunction "PW1_A20") (pintype "passive"))
      (node (ref "S-I") (pin "B19") (pinfunction "PW2_B19") (pintype "passive"))
      (node (ref "S-I") (pin "B20") (pinfunction "PW1_B20") (pintype "passive"))
      (node (ref "S-I") (pin "C19") (pinfunction "PW2_C19") (pintype "passive"))
      (node (ref "S-I") (pin "C20") (pinfunction "PW1_C20") (pintype "passive"))
      (node (ref "S-J") (pin "A19") (pinfunction "PW2_A19") (pintype "passive"))
      (node (ref "S-J") (pin "A20") (pinfunction "PW1_A20") (pintype "passive"))
      (node (ref "S-J") (pin "B19") (pinfunction "PW2_B19") (pintype "passive"))
      (node (ref "S-J") (pin "B20") (pinfunction "PW1_B20") (pintype "passive"))
      (node (ref "S-J") (pin "C19") (pinfunction "PW2_C19") (pintype "passive"))
      (node (ref "S-J") (pin "C20") (pinfunction "PW1_C20") (pintype "passive"))
      (node (ref "TMP36-1") (pin "1") (pinfunction "+VS_1") (pintype "power_in"))
      (node (ref "TMP36-2") (pin "1") (pinfunction "+VS_1") (pintype "power_in"))
      (node (ref "TMP36-3") (pin "1") (pinfunction "+VS_1") (pintype "power_in"))
    )
    (net (code "35") (name "Net-(RPI-GPIO_02_(SDA1,I2C))") (class "Default")
      (node (ref "I2C1") (pin "5") (pinfunction "5_5") (pintype "passive"))
      (node (ref "I2C2") (pin "5") (pinfunction "5_5") (pintype "passive"))
      (node (ref "PUR-SCL2") (pin "2") (pinfunction "2_2") (pintype "passive"))
      (node (ref "RPI") (pin "3") (pinfunction "GPIO_02_(SDA1,I2C)_3") (pintype "passive"))
    )
    (net (code "36") (name "Net-(RPI-GPIO_03_(SCL1,I2C))") (class "Default")
      (node (ref "I2C1") (pin "6") (pinfunction "6_6") (pintype "passive"))
      (node (ref "I2C2") (pin "6") (pinfunction "6_6") (pintype "passive"))
      (node (ref "PUR-SDA2") (pin "2") (pinfunction "2_2") (pintype "passive"))
      (node (ref "RPI") (pin "5") (pinfunction "GPIO_03_(SCL1,I2C)_5") (pintype "passive"))
    )
    (net (code "37") (name "Net-(RPI-GPIO_05)") (class "Default")
      (node (ref "RPI") (pin "29") (pinfunction "GPIO_05_29") (pintype "passive"))
      (node (ref "S-H") (pin "B16") (pinfunction "RPI_B16") (pintype "passive"))
    )
    (net (code "38") (name "Net-(RPI-GPIO_06)") (class "Default")
      (node (ref "RPI") (pin "31") (pinfunction "GPIO_06_31") (pintype "passive"))
      (node (ref "S-I") (pin "B16") (pinfunction "RPI_B16") (pintype "passive"))
    )
    (net (code "39") (name "Net-(RPI-GPIO_12)") (class "Default")
      (node (ref "RPI") (pin "32") (pinfunction "GPIO_12_32") (pintype "passive"))
      (node (ref "S-J") (pin "B16") (pinfunction "RPI_B16") (pintype "passive"))
    )
    (net (code "40") (name "Net-(RPI-GPIO_13)") (class "Default")
      (node (ref "RPI") (pin "33") (pinfunction "GPIO_13_33") (pintype "passive"))
      (node (ref "S-F") (pin "B16") (pinfunction "RPI_B16") (pintype "passive"))
    )
    (net (code "41") (name "Net-(RPI-GPIO_14_(TXD0))") (class "Default")
      (node (ref "AUNO") (pin "D0") (pinfunction "D0_D0") (pintype "passive"))
      (node (ref "RPI") (pin "8") (pinfunction "GPIO_14_(TXD0)_8") (pintype "output"))
    )
    (net (code "42") (name "Net-(RPI-GPIO_15_(RXD0))") (class "Default")
      (node (ref "AUNO") (pin "D1") (pinfunction "D1_D1") (pintype "passive"))
      (node (ref "RPI") (pin "10") (pinfunction "GPIO_15_(RXD0)_10") (pintype "input"))
    )
    (net (code "43") (name "Net-(RPI-GPIO_16)") (class "Default")
      (node (ref "RPI") (pin "36") (pinfunction "GPIO_16_36") (pintype "passive"))
      (node (ref "S-D") (pin "B16") (pinfunction "RPI_B16") (pintype "passive"))
    )
    (net (code "44") (name "Net-(RPI-GPIO_19)") (class "Default")
      (node (ref "RPI") (pin "35") (pinfunction "GPIO_19_35") (pintype "passive"))
      (node (ref "S-E") (pin "B16") (pinfunction "RPI_B16") (pintype "passive"))
    )
    (net (code "45") (name "Net-(RPI-GPIO_20)") (class "Default")
      (node (ref "RPI") (pin "38") (pinfunction "GPIO_20_38") (pintype "passive"))
      (node (ref "S-B") (pin "B16") (pinfunction "RPI_B16") (pintype "passive"))
    )
    (net (code "46") (name "Net-(RPI-GPIO_21)") (class "Default")
      (node (ref "RPI") (pin "40") (pinfunction "GPIO_21_40") (pintype "passive"))
      (node (ref "S-A") (pin "B16") (pinfunction "RPI_B16") (pintype "passive"))
    )
    (net (code "47") (name "Net-(RPI-GPIO_22_(GPIO_GEN3))") (class "Default")
      (node (ref "RPI") (pin "15") (pinfunction "GPIO_22_(GPIO_GEN3)_15") (pintype "passive"))
      (node (ref "S-G") (pin "B16") (pinfunction "RPI_B16") (pintype "passive"))
    )
    (net (code "48") (name "Net-(RPI-GPIO_26)") (class "Default")
      (node (ref "RPI") (pin "37") (pinfunction "GPIO_26_37") (pintype "passive"))
      (node (ref "S-C") (pin "B16") (pinfunction "RPI_B16") (pintype "passive"))
    )
    (net (code "49") (name "Net-(S-A-1-1)") (class "Default")
      (node (ref "CH-A1") (pin "1") (pinfunction "1_1") (pintype "passive"))
      (node (ref "S-A") (pin "A12") (pinfunction "1-1_A12") (pintype "passive"))
    )
    (net (code "50") (name "Net-(S-A-1-2)") (class "Default")
      (node (ref "CH-A2") (pin "1") (pinfunction "1_1") (pintype "passive"))
      (node (ref "S-A") (pin "B12") (pinfunction "1-2_B12") (pintype "passive"))
    )
    (net (code "51") (name "Net-(S-A-1-3)") (class "Default")
      (node (ref "CH-A3") (pin "1") (pinfunction "1_1") (pintype "passive"))
      (node (ref "S-A") (pin "C12") (pinfunction "1-3_C12") (pintype "passive"))
    )
    (net (code "52") (name "Net-(S-A-1-4)") (class "Default")
      (node (ref "CH-A1") (pin "2") (pinfunction "2_2") (pintype "passive"))
      (node (ref "S-A") (pin "A11") (pinfunction "1-4_A11") (pintype "passive"))
    )
    (net (code "53") (name "Net-(S-A-2-1)") (class "Default")
      (node (ref "CH-A2") (pin "2") (pinfunction "2_2") (pintype "passive"))
      (node (ref "S-A") (pin "B11") (pinfunction "2-1_B11") (pintype "passive"))
    )
    (net (code "54") (name "Net-(S-A-2-2)") (class "Default")
      (node (ref "CH-A3") (pin "2") (pinfunction "2_2") (pintype "passive"))
      (node (ref "S-A") (pin "C11") (pinfunction "2-2_C11") (pintype "passive"))
    )
    (net (code "55") (name "Net-(S-A-2-3)") (class "Default")
      (node (ref "CH-A1") (pin "3") (pinfunction "3_3") (pintype "passive"))
      (node (ref "S-A") (pin "A10") (pinfunction "2-3_A10") (pintype "passive"))
    )
    (net (code "56") (name "Net-(S-A-2-4)") (class "Default")
      (node (ref "CH-A2") (pin "3") (pinfunction "3_3") (pintype "passive"))
      (node (ref "S-A") (pin "B10") (pinfunction "2-4_B10") (pintype "passive"))
    )
    (net (code "57") (name "Net-(S-A-3-1)") (class "Default")
      (node (ref "CH-A3") (pin "3") (pinfunction "3_3") (pintype "passive"))
      (node (ref "S-A") (pin "C10") (pinfunction "3-1_C10") (pintype "passive"))
    )
    (net (code "58") (name "Net-(S-A-3-2)") (class "Default")
      (node (ref "CH-A1") (pin "4") (pinfunction "4_4") (pintype "passive"))
      (node (ref "S-A") (pin "A9") (pinfunction "3-2_A9") (pintype "passive"))
    )
    (net (code "59") (name "Net-(S-A-3-3)") (class "Default")
      (node (ref "CH-A2") (pin "4") (pinfunction "4_4") (pintype "passive"))
      (node (ref "S-A") (pin "B9") (pinfunction "3-3_B9") (pintype "passive"))
    )
    (net (code "60") (name "Net-(S-A-3-4)") (class "Default")
      (node (ref "CH-A3") (pin "4") (pinfunction "4_4") (pintype "passive"))
      (node (ref "S-A") (pin "C9") (pinfunction "3-4_C9") (pintype "passive"))
    )
    (net (code "61") (name "Net-(S-A-4-1)") (class "Default")
      (node (ref "CH-A4") (pin "1") (pinfunction "1_1") (pintype "passive"))
      (node (ref "S-A") (pin "A8") (pinfunction "4-1_A8") (pintype "passive"))
    )
    (net (code "62") (name "Net-(S-A-4-2)") (class "Default")
      (node (ref "CH-A5") (pin "1") (pinfunction "1_1") (pintype "passive"))
      (node (ref "S-A") (pin "B8") (pinfunction "4-2_B8") (pintype "passive"))
    )
    (net (code "63") (name "Net-(S-A-4-3)") (class "Default")
      (node (ref "CH-A6") (pin "1") (pinfunction "1_1") (pintype "passive"))
      (node (ref "S-A") (pin "C8") (pinfunction "4-3_C8") (pintype "passive"))
    )
    (net (code "64") (name "Net-(S-A-4-4)") (class "Default")
      (node (ref "CH-A4") (pin "2") (pinfunction "2_2") (pintype "passive"))
      (node (ref "S-A") (pin "A7") (pinfunction "4-4_A7") (pintype "passive"))
    )
    (net (code "65") (name "Net-(S-A-5-1)") (class "Default")
      (node (ref "CH-A5") (pin "2") (pinfunction "2_2") (pintype "passive"))
      (node (ref "S-A") (pin "B7") (pinfunction "5-1_B7") (pintype "passive"))
    )
    (net (code "66") (name "Net-(S-A-5-2)") (class "Default")
      (node (ref "CH-A6") (pin "2") (pinfunction "2_2") (pintype "passive"))
      (node (ref "S-A") (pin "C7") (pinfunction "5-2_C7") (pintype "passive"))
    )
    (net (code "67") (name "Net-(S-A-5-3)") (class "Default")
      (node (ref "CH-A4") (pin "3") (pinfunction "3_3") (pintype "passive"))
      (node (ref "S-A") (pin "A6") (pinfunction "5-3_A6") (pintype "passive"))
    )
    (net (code "68") (name "Net-(S-A-5-4)") (class "Default")
      (node (ref "CH-A5") (pin "3") (pinfunction "3_3") (pintype "passive"))
      (node (ref "S-A") (pin "B6") (pinfunction "5-4_B6") (pintype "passive"))
    )
    (net (code "69") (name "Net-(S-A-6-1)") (class "Default")
      (node (ref "CH-A6") (pin "3") (pinfunction "3_3") (pintype "passive"))
      (node (ref "S-A") (pin "C6") (pinfunction "6-1_C6") (pintype "passive"))
    )
    (net (code "70") (name "Net-(S-A-6-2)") (class "Default")
      (node (ref "CH-A4") (pin "4") (pinfunction "4_4") (pintype "passive"))
      (node (ref "S-A") (pin "A5") (pinfunction "6-2_A5") (pintype "passive"))
    )
    (net (code "71") (name "Net-(S-A-6-3)") (class "Default")
      (node (ref "CH-A5") (pin "4") (pinfunction "4_4") (pintype "passive"))
      (node (ref "S-A") (pin "B5") (pinfunction "6-3_B5") (pintype "passive"))
    )
    (net (code "72") (name "Net-(S-A-6-4)") (class "Default")
      (node (ref "CH-A6") (pin "4") (pinfunction "4_4") (pintype "passive"))
      (node (ref "S-A") (pin "C5") (pinfunction "6-4_C5") (pintype "passive"))
    )
    (net (code "73") (name "Net-(S-A-7-1)") (class "Default")
      (node (ref "CH-A7") (pin "1") (pinfunction "1_1") (pintype "passive"))
      (node (ref "S-A") (pin "A4") (pinfunction "7-1_A4") (pintype "passive"))
    )
    (net (code "74") (name "Net-(S-A-7-2)") (class "Default")
      (node (ref "CH-A8") (pin "1") (pinfunction "1_1") (pintype "passive"))
      (node (ref "S-A") (pin "B4") (pinfunction "7-2_B4") (pintype "passive"))
    )
    (net (code "75") (name "Net-(S-A-7-3)") (class "Default")
      (node (ref "CH-A9") (pin "1") (pinfunction "1_1") (pintype "passive"))
      (node (ref "S-A") (pin "C4") (pinfunction "7-3_C4") (pintype "passive"))
    )
    (net (code "76") (name "Net-(S-A-7-4)") (class "Default")
      (node (ref "CH-A7") (pin "2") (pinfunction "2_2") (pintype "passive"))
      (node (ref "S-A") (pin "A3") (pinfunction "7-4_A3") (pintype "passive"))
    )
    (net (code "77") (name "Net-(S-A-8-1)") (class "Default")
      (node (ref "CH-A8") (pin "2") (pinfunction "2_2") (pintype "passive"))
      (node (ref "S-A") (pin "B3") (pinfunction "8-1_B3") (pintype "passive"))
    )
    (net (code "78") (name "Net-(S-A-8-2)") (class "Default")
      (node (ref "CH-A9") (pin "2") (pinfunction "2_2") (pintype "passive"))
      (node (ref "S-A") (pin "C3") (pinfunction "8-2_C3") (pintype "passive"))
    )
    (net (code "79") (name "Net-(S-A-8-3)") (class "Default")
      (node (ref "CH-A7") (pin "3") (pinfunction "3_3") (pintype "passive"))
      (node (ref "S-A") (pin "A2") (pinfunction "8-3_A2") (pintype "passive"))
    )
    (net (code "80") (name "Net-(S-A-8-4)") (class "Default")
      (node (ref "CH-A8") (pin "3") (pinfunction "3_3") (pintype "passive"))
      (node (ref "S-A") (pin "B2") (pinfunction "8-4_B2") (pintype "passive"))
    )
    (net (code "81") (name "Net-(S-A-9-1)") (class "Default")
      (node (ref "CH-A9") (pin "3") (pinfunction "3_3") (pintype "passive"))
      (node (ref "S-A") (pin "C2") (pinfunction "9-1_C2") (pintype "passive"))
    )
    (net (code "82") (name "Net-(S-A-9-2)") (class "Default")
      (node (ref "CH-A7") (pin "4") (pinfunction "4_4") (pintype "passive"))
      (node (ref "S-A") (pin "A1") (pinfunction "9-2_A1") (pintype "passive"))
    )
    (net (code "83") (name "Net-(S-A-9-3)") (class "Default")
      (node (ref "CH-A8") (pin "4") (pinfunction "4_4") (pintype "passive"))
      (node (ref "S-A") (pin "B1") (pinfunction "9-3_B1") (pintype "passive"))
    )
    (net (code "84") (name "Net-(S-A-9-4)") (class "Default")
      (node (ref "CH-A9") (pin "4") (pinfunction "4_4") (pintype "passive"))
      (node (ref "S-A") (pin "C1") (pinfunction "9-4_C1") (pintype "passive"))
    )
    (net (code "85") (name "Net-(S-A-ARD)") (class "Default")
      (node (ref "AUNO") (pin "D2") (pinfunction "D2_D2") (pintype "passive"))
      (node (ref "S-A") (pin "C16") (pinfunction "ARD_C16") (pintype "passive"))
    )
    (net (code "86") (name "Net-(S-A-MISO)") (class "Default")
      (node (ref "S-A") (pin "B17") (pinfunction "MISO_B17") (pintype "passive"))
      (node (ref "S-B") (pin "B17") (pinfunction "MISO_B17") (pintype "passive"))
    )
    (net (code "87") (name "Net-(S-A-MOSI)") (class "Default")
      (node (ref "S-A") (pin "C17") (pinfunction "MOSI_C17") (pintype "passive"))
      (node (ref "S-B") (pin "C17") (pinfunction "MOSI_C17") (pintype "passive"))
    )
    (net (code "88") (name "Net-(S-A-SCK)") (class "Default")
      (node (ref "S-A") (pin "A16") (pinfunction "SCK_A16") (pintype "passive"))
      (node (ref "S-B") (pin "A16") (pinfunction "SCK_A16") (pintype "passive"))
    )
    (net (code "89") (name "Net-(S-A-SDA1)") (class "Default")
      (node (ref "I2C1") (pin "3") (pinfunction "3_3") (pintype "passive"))
      (node (ref "S-A") (pin "B14") (pinfunction "SDA1_B14") (pintype "passive"))
      (node (ref "S-B") (pin "B14") (pinfunction "SDA1_B14") (pintype "passive"))
      (node (ref "S-C") (pin "B14") (pinfunction "SDA1_B14") (pintype "passive"))
      (node (ref "S-D") (pin "B14") (pinfunction "SDA1_B14") (pintype "passive"))
      (node (ref "S-E") (pin "B14") (pinfunction "SDA1_B14") (pintype "passive"))
      (node (ref "S-F") (pin "B14") (pinfunction "SDA1_B14") (pintype "passive"))
      (node (ref "S-G") (pin "B14") (pinfunction "SDA1_B14") (pintype "passive"))
      (node (ref "S-H") (pin "B14") (pinfunction "SDA1_B14") (pintype "passive"))
      (node (ref "S-I") (pin "B14") (pinfunction "SDA1_B14") (pintype "passive"))
      (node (ref "S-J") (pin "B14") (pinfunction "SDA1_B14") (pintype "passive"))
    )
    (net (code "90") (name "Net-(S-A-SDA2)") (class "Default")
      (node (ref "I2C2") (pin "3") (pinfunction "3_3") (pintype "passive"))
      (node (ref "S-A") (pin "C14") (pinfunction "SDA2_C14") (pintype "passive"))
      (node (ref "S-B") (pin "C14") (pinfunction "SDA2_C14") (pintype "passive"))
      (node (ref "S-C") (pin "C14") (pinfunction "SDA2_C14") (pintype "passive"))
      (node (ref "S-D") (pin "C14") (pinfunction "SDA2_C14") (pintype "passive"))
      (node (ref "S-E") (pin "C14") (pinfunction "SDA2_C14") (pintype "passive"))
      (node (ref "S-F") (pin "C14") (pinfunction "SDA2_C14") (pintype "passive"))
      (node (ref "S-G") (pin "C14") (pinfunction "SDA2_C14") (pintype "passive"))
      (node (ref "S-H") (pin "C14") (pinfunction "SDA2_C14") (pintype "passive"))
      (node (ref "S-I") (pin "C14") (pinfunction "SDA2_C14") (pintype "passive"))
      (node (ref "S-J") (pin "C14") (pinfunction "SDA2_C14") (pintype "passive"))
    )
    (net (code "91") (name "Net-(S-A-SLC1)") (class "Default")
      (node (ref "I2C1") (pin "4") (pinfunction "4_4") (pintype "passive"))
      (node (ref "S-A") (pin "B15") (pinfunction "SLC1_B15") (pintype "passive"))
      (node (ref "S-B") (pin "B15") (pinfunction "SLC1_B15") (pintype "passive"))
      (node (ref "S-C") (pin "B15") (pinfunction "SLC1_B15") (pintype "passive"))
      (node (ref "S-D") (pin "B15") (pinfunction "SLC1_B15") (pintype "passive"))
      (node (ref "S-E") (pin "B15") (pinfunction "SLC1_B15") (pintype "passive"))
      (node (ref "S-F") (pin "B15") (pinfunction "SLC1_B15") (pintype "passive"))
      (node (ref "S-G") (pin "B15") (pinfunction "SLC1_B15") (pintype "passive"))
      (node (ref "S-H") (pin "B15") (pinfunction "SLC1_B15") (pintype "passive"))
      (node (ref "S-I") (pin "B15") (pinfunction "SLC1_B15") (pintype "passive"))
      (node (ref "S-J") (pin "B15") (pinfunction "SLC1_B15") (pintype "passive"))
    )
    (net (code "92") (name "Net-(S-A-SLC2)") (class "Default")
      (node (ref "I2C2") (pin "4") (pinfunction "4_4") (pintype "passive"))
      (node (ref "S-A") (pin "C15") (pinfunction "SLC2_C15") (pintype "passive"))
      (node (ref "S-B") (pin "C15") (pinfunction "SLC2_C15") (pintype "passive"))
      (node (ref "S-C") (pin "C15") (pinfunction "SLC2_C15") (pintype "passive"))
      (node (ref "S-D") (pin "C15") (pinfunction "SLC2_C15") (pintype "passive"))
      (node (ref "S-E") (pin "C15") (pinfunction "SLC2_C15") (pintype "passive"))
      (node (ref "S-F") (pin "C15") (pinfunction "SLC2_C15") (pintype "passive"))
      (node (ref "S-G") (pin "C15") (pinfunction "SLC2_C15") (pintype "passive"))
      (node (ref "S-H") (pin "C15") (pinfunction "SLC2_C15") (pintype "passive"))
      (node (ref "S-I") (pin "C15") (pinfunction "SLC2_C15") (pintype "passive"))
      (node (ref "S-J") (pin "C15") (pinfunction "SLC2_C15") (pintype "passive"))
    )
    (net (code "93") (name "Net-(S-A-SS)") (class "Default")
      (node (ref "S-A") (pin "A17") (pinfunction "SS_A17") (pintype "passive"))
      (node (ref "S-B") (pin "A17") (pinfunction "SS_A17") (pintype "passive"))
    )
    (net (code "94") (name "Net-(S-B-1-1)") (class "Default")
      (node (ref "CH-B1") (pin "1") (pinfunction "1_1") (pintype "passive"))
      (node (ref "S-B") (pin "A12") (pinfunction "1-1_A12") (pintype "passive"))
    )
    (net (code "95") (name "Net-(S-B-1-2)") (class "Default")
      (node (ref "CH-B2") (pin "1") (pinfunction "1_1") (pintype "passive"))
      (node (ref "S-B") (pin "B12") (pinfunction "1-2_B12") (pintype "passive"))
    )
    (net (code "96") (name "Net-(S-B-1-3)") (class "Default")
      (node (ref "CH-B3") (pin "1") (pinfunction "1_1") (pintype "passive"))
      (node (ref "S-B") (pin "C12") (pinfunction "1-3_C12") (pintype "passive"))
    )
    (net (code "97") (name "Net-(S-B-1-4)") (class "Default")
      (node (ref "CH-B1") (pin "2") (pinfunction "2_2") (pintype "passive"))
      (node (ref "S-B") (pin "A11") (pinfunction "1-4_A11") (pintype "passive"))
    )
    (net (code "98") (name "Net-(S-B-2-1)") (class "Default")
      (node (ref "CH-B2") (pin "2") (pinfunction "2_2") (pintype "passive"))
      (node (ref "S-B") (pin "B11") (pinfunction "2-1_B11") (pintype "passive"))
    )
    (net (code "99") (name "Net-(S-B-2-2)") (class "Default")
      (node (ref "CH-B3") (pin "2") (pinfunction "2_2") (pintype "passive"))
      (node (ref "S-B") (pin "C11") (pinfunction "2-2_C11") (pintype "passive"))
    )
    (net (code "100") (name "Net-(S-B-2-3)") (class "Default")
      (node (ref "CH-B1") (pin "3") (pinfunction "3_3") (pintype "passive"))
      (node (ref "S-B") (pin "A10") (pinfunction "2-3_A10") (pintype "passive"))
    )
    (net (code "101") (name "Net-(S-B-2-4)") (class "Default")
      (node (ref "CH-B2") (pin "3") (pinfunction "3_3") (pintype "passive"))
      (node (ref "S-B") (pin "B10") (pinfunction "2-4_B10") (pintype "passive"))
    )
    (net (code "102") (name "Net-(S-B-3-1)") (class "Default")
      (node (ref "CH-B3") (pin "3") (pinfunction "3_3") (pintype "passive"))
      (node (ref "S-B") (pin "C10") (pinfunction "3-1_C10") (pintype "passive"))
    )
    (net (code "103") (name "Net-(S-B-3-2)") (class "Default")
      (node (ref "CH-B1") (pin "4") (pinfunction "4_4") (pintype "passive"))
      (node (ref "S-B") (pin "A9") (pinfunction "3-2_A9") (pintype "passive"))
    )
    (net (code "104") (name "Net-(S-B-3-3)") (class "Default")
      (node (ref "CH-B2") (pin "4") (pinfunction "4_4") (pintype "passive"))
      (node (ref "S-B") (pin "B9") (pinfunction "3-3_B9") (pintype "passive"))
    )
    (net (code "105") (name "Net-(S-B-3-4)") (class "Default")
      (node (ref "CH-B3") (pin "4") (pinfunction "4_4") (pintype "passive"))
      (node (ref "S-B") (pin "C9") (pinfunction "3-4_C9") (pintype "passive"))
    )
    (net (code "106") (name "Net-(S-B-4-1)") (class "Default")
      (node (ref "CH-B4") (pin "1") (pinfunction "1_1") (pintype "passive"))
      (node (ref "S-B") (pin "A8") (pinfunction "4-1_A8") (pintype "passive"))
    )
    (net (code "107") (name "Net-(S-B-4-2)") (class "Default")
      (node (ref "CH-B5") (pin "1") (pinfunction "1_1") (pintype "passive"))
      (node (ref "S-B") (pin "B8") (pinfunction "4-2_B8") (pintype "passive"))
    )
    (net (code "108") (name "Net-(S-B-4-3)") (class "Default")
      (node (ref "CH-B6") (pin "1") (pinfunction "1_1") (pintype "passive"))
      (node (ref "S-B") (pin "C8") (pinfunction "4-3_C8") (pintype "passive"))
    )
    (net (code "109") (name "Net-(S-B-4-4)") (class "Default")
      (node (ref "CH-B4") (pin "2") (pinfunction "2_2") (pintype "passive"))
      (node (ref "S-B") (pin "A7") (pinfunction "4-4_A7") (pintype "passive"))
    )
    (net (code "110") (name "Net-(S-B-5-1)") (class "Default")
      (node (ref "CH-B5") (pin "2") (pinfunction "2_2") (pintype "passive"))
      (node (ref "S-B") (pin "B7") (pinfunction "5-1_B7") (pintype "passive"))
    )
    (net (code "111") (name "Net-(S-B-5-2)") (class "Default")
      (node (ref "CH-B6") (pin "2") (pinfunction "2_2") (pintype "passive"))
      (node (ref "S-B") (pin "C7") (pinfunction "5-2_C7") (pintype "passive"))
    )
    (net (code "112") (name "Net-(S-B-5-3)") (class "Default")
      (node (ref "CH-B4") (pin "3") (pinfunction "3_3") (pintype "passive"))
      (node (ref "S-B") (pin "A6") (pinfunction "5-3_A6") (pintype "passive"))
    )
    (net (code "113") (name "Net-(S-B-5-4)") (class "Default")
      (node (ref "CH-B5") (pin "3") (pinfunction "3_3") (pintype "passive"))
      (node (ref "S-B") (pin "B6") (pinfunction "5-4_B6") (pintype "passive"))
    )
    (net (code "114") (name "Net-(S-B-6-1)") (class "Default")
      (node (ref "CH-B6") (pin "3") (pinfunction "3_3") (pintype "passive"))
      (node (ref "S-B") (pin "C6") (pinfunction "6-1_C6") (pintype "passive"))
    )
    (net (code "115") (name "Net-(S-B-6-2)") (class "Default")
      (node (ref "CH-B4") (pin "4") (pinfunction "4_4") (pintype "passive"))
      (node (ref "S-B") (pin "A5") (pinfunction "6-2_A5") (pintype "passive"))
    )
    (net (code "116") (name "Net-(S-B-6-3)") (class "Default")
      (node (ref "CH-B5") (pin "4") (pinfunction "4_4") (pintype "passive"))
      (node (ref "S-B") (pin "B5") (pinfunction "6-3_B5") (pintype "passive"))
    )
    (net (code "117") (name "Net-(S-B-6-4)") (class "Default")
      (node (ref "CH-B6") (pin "4") (pinfunction "4_4") (pintype "passive"))
      (node (ref "S-B") (pin "C5") (pinfunction "6-4_C5") (pintype "passive"))
    )
    (net (code "118") (name "Net-(S-B-7-1)") (class "Default")
      (node (ref "CH-B7") (pin "1") (pinfunction "1_1") (pintype "passive"))
      (node (ref "S-B") (pin "A4") (pinfunction "7-1_A4") (pintype "passive"))
    )
    (net (code "119") (name "Net-(S-B-7-2)") (class "Default")
      (node (ref "CH-B8") (pin "1") (pinfunction "1_1") (pintype "passive"))
      (node (ref "S-B") (pin "B4") (pinfunction "7-2_B4") (pintype "passive"))
    )
    (net (code "120") (name "Net-(S-B-7-3)") (class "Default")
      (node (ref "CH-B9") (pin "1") (pinfunction "1_1") (pintype "passive"))
      (node (ref "S-B") (pin "C4") (pinfunction "7-3_C4") (pintype "passive"))
    )
    (net (code "121") (name "Net-(S-B-7-4)") (class "Default")
      (node (ref "CH-B7") (pin "2") (pinfunction "2_2") (pintype "passive"))
      (node (ref "S-B") (pin "A3") (pinfunction "7-4_A3") (pintype "passive"))
    )
    (net (code "122") (name "Net-(S-B-8-1)") (class "Default")
      (node (ref "CH-B8") (pin "2") (pinfunction "2_2") (pintype "passive"))
      (node (ref "S-B") (pin "B3") (pinfunction "8-1_B3") (pintype "passive"))
    )
    (net (code "123") (name "Net-(S-B-8-2)") (class "Default")
      (node (ref "CH-B9") (pin "2") (pinfunction "2_2") (pintype "passive"))
      (node (ref "S-B") (pin "C3") (pinfunction "8-2_C3") (pintype "passive"))
    )
    (net (code "124") (name "Net-(S-B-8-3)") (class "Default")
      (node (ref "CH-B7") (pin "3") (pinfunction "3_3") (pintype "passive"))
      (node (ref "S-B") (pin "A2") (pinfunction "8-3_A2") (pintype "passive"))
    )
    (net (code "125") (name "Net-(S-B-8-4)") (class "Default")
      (node (ref "CH-B8") (pin "3") (pinfunction "3_3") (pintype "passive"))
      (node (ref "S-B") (pin "B2") (pinfunction "8-4_B2") (pintype "passive"))
    )
    (net (code "126") (name "Net-(S-B-9-1)") (class "Default")
      (node (ref "CH-B9") (pin "3") (pinfunction "3_3") (pintype "passive"))
      (node (ref "S-B") (pin "C2") (pinfunction "9-1_C2") (pintype "passive"))
    )
    (net (code "127") (name "Net-(S-B-9-2)") (class "Default")
      (node (ref "CH-B7") (pin "4") (pinfunction "4_4") (pintype "passive"))
      (node (ref "S-B") (pin "A1") (pinfunction "9-2_A1") (pintype "passive"))
    )
    (net (code "128") (name "Net-(S-B-9-3)") (class "Default")
      (node (ref "CH-B8") (pin "4") (pinfunction "4_4") (pintype "passive"))
      (node (ref "S-B") (pin "B1") (pinfunction "9-3_B1") (pintype "passive"))
    )
    (net (code "129") (name "Net-(S-B-9-4)") (class "Default")
      (node (ref "CH-B9") (pin "4") (pinfunction "4_4") (pintype "passive"))
      (node (ref "S-B") (pin "C1") (pinfunction "9-4_C1") (pintype "passive"))
    )
    (net (code "130") (name "Net-(S-C-1-1)") (class "Default")
      (node (ref "CH-C1") (pin "1") (pinfunction "1_1") (pintype "passive"))
      (node (ref "S-C") (pin "A12") (pinfunction "1-1_A12") (pintype "passive"))
    )
    (net (code "131") (name "Net-(S-C-1-2)") (class "Default")
      (node (ref "CH-C2") (pin "1") (pinfunction "1_1") (pintype "passive"))
      (node (ref "S-C") (pin "B12") (pinfunction "1-2_B12") (pintype "passive"))
    )
    (net (code "132") (name "Net-(S-C-1-3)") (class "Default")
      (node (ref "CH-C3") (pin "1") (pinfunction "1_1") (pintype "passive"))
      (node (ref "S-C") (pin "C12") (pinfunction "1-3_C12") (pintype "passive"))
    )
    (net (code "133") (name "Net-(S-C-1-4)") (class "Default")
      (node (ref "CH-C1") (pin "2") (pinfunction "2_2") (pintype "passive"))
      (node (ref "S-C") (pin "A11") (pinfunction "1-4_A11") (pintype "passive"))
    )
    (net (code "134") (name "Net-(S-C-2-1)") (class "Default")
      (node (ref "CH-C2") (pin "2") (pinfunction "2_2") (pintype "passive"))
      (node (ref "S-C") (pin "B11") (pinfunction "2-1_B11") (pintype "passive"))
    )
    (net (code "135") (name "Net-(S-C-2-2)") (class "Default")
      (node (ref "CH-C3") (pin "2") (pinfunction "2_2") (pintype "passive"))
      (node (ref "S-C") (pin "C11") (pinfunction "2-2_C11") (pintype "passive"))
    )
    (net (code "136") (name "Net-(S-C-2-3)") (class "Default")
      (node (ref "CH-C1") (pin "3") (pinfunction "3_3") (pintype "passive"))
      (node (ref "S-C") (pin "A10") (pinfunction "2-3_A10") (pintype "passive"))
    )
    (net (code "137") (name "Net-(S-C-2-4)") (class "Default")
      (node (ref "CH-C2") (pin "3") (pinfunction "3_3") (pintype "passive"))
      (node (ref "S-C") (pin "B10") (pinfunction "2-4_B10") (pintype "passive"))
    )
    (net (code "138") (name "Net-(S-C-3-1)") (class "Default")
      (node (ref "CH-C3") (pin "3") (pinfunction "3_3") (pintype "passive"))
      (node (ref "S-C") (pin "C10") (pinfunction "3-1_C10") (pintype "passive"))
    )
    (net (code "139") (name "Net-(S-C-3-2)") (class "Default")
      (node (ref "CH-C1") (pin "4") (pinfunction "4_4") (pintype "passive"))
      (node (ref "S-C") (pin "A9") (pinfunction "3-2_A9") (pintype "passive"))
    )
    (net (code "140") (name "Net-(S-C-3-3)") (class "Default")
      (node (ref "CH-C2") (pin "4") (pinfunction "4_4") (pintype "passive"))
      (node (ref "S-C") (pin "B9") (pinfunction "3-3_B9") (pintype "passive"))
    )
    (net (code "141") (name "Net-(S-C-3-4)") (class "Default")
      (node (ref "CH-C3") (pin "4") (pinfunction "4_4") (pintype "passive"))
      (node (ref "S-C") (pin "C9") (pinfunction "3-4_C9") (pintype "passive"))
    )
    (net (code "142") (name "Net-(S-C-4-1)") (class "Default")
      (node (ref "CH-C4") (pin "1") (pinfunction "1_1") (pintype "passive"))
      (node (ref "S-C") (pin "A8") (pinfunction "4-1_A8") (pintype "passive"))
    )
    (net (code "143") (name "Net-(S-C-4-2)") (class "Default")
      (node (ref "CH-C5") (pin "1") (pinfunction "1_1") (pintype "passive"))
      (node (ref "S-C") (pin "B8") (pinfunction "4-2_B8") (pintype "passive"))
    )
    (net (code "144") (name "Net-(S-C-4-3)") (class "Default")
      (node (ref "CH-C6") (pin "1") (pinfunction "1_1") (pintype "passive"))
      (node (ref "S-C") (pin "C8") (pinfunction "4-3_C8") (pintype "passive"))
    )
    (net (code "145") (name "Net-(S-C-4-4)") (class "Default")
      (node (ref "CH-C4") (pin "2") (pinfunction "2_2") (pintype "passive"))
      (node (ref "S-C") (pin "A7") (pinfunction "4-4_A7") (pintype "passive"))
    )
    (net (code "146") (name "Net-(S-C-5-1)") (class "Default")
      (node (ref "CH-C5") (pin "2") (pinfunction "2_2") (pintype "passive"))
      (node (ref "S-C") (pin "B7") (pinfunction "5-1_B7") (pintype "passive"))
    )
    (net (code "147") (name "Net-(S-C-5-2)") (class "Default")
      (node (ref "CH-C6") (pin "2") (pinfunction "2_2") (pintype "passive"))
      (node (ref "S-C") (pin "C7") (pinfunction "5-2_C7") (pintype "passive"))
    )
    (net (code "148") (name "Net-(S-C-5-3)") (class "Default")
      (node (ref "CH-C4") (pin "3") (pinfunction "3_3") (pintype "passive"))
      (node (ref "S-C") (pin "A6") (pinfunction "5-3_A6") (pintype "passive"))
    )
    (net (code "149") (name "Net-(S-C-5-4)") (class "Default")
      (node (ref "CH-C5") (pin "3") (pinfunction "3_3") (pintype "passive"))
      (node (ref "S-C") (pin "B6") (pinfunction "5-4_B6") (pintype "passive"))
    )
    (net (code "150") (name "Net-(S-C-6-1)") (class "Default")
      (node (ref "CH-C6") (pin "3") (pinfunction "3_3") (pintype "passive"))
      (node (ref "S-C") (pin "C6") (pinfunction "6-1_C6") (pintype "passive"))
    )
    (net (code "151") (name "Net-(S-C-6-2)") (class "Default")
      (node (ref "CH-C4") (pin "4") (pinfunction "4_4") (pintype "passive"))
      (node (ref "S-C") (pin "A5") (pinfunction "6-2_A5") (pintype "passive"))
    )
    (net (code "152") (name "Net-(S-C-6-3)") (class "Default")
      (node (ref "CH-C5") (pin "4") (pinfunction "4_4") (pintype "passive"))
      (node (ref "S-C") (pin "B5") (pinfunction "6-3_B5") (pintype "passive"))
    )
    (net (code "153") (name "Net-(S-C-6-4)") (class "Default")
      (node (ref "CH-C6") (pin "4") (pinfunction "4_4") (pintype "passive"))
      (node (ref "S-C") (pin "C5") (pinfunction "6-4_C5") (pintype "passive"))
    )
    (net (code "154") (name "Net-(S-C-7-1)") (class "Default")
      (node (ref "CH-C7") (pin "1") (pinfunction "1_1") (pintype "passive"))
      (node (ref "S-C") (pin "A4") (pinfunction "7-1_A4") (pintype "passive"))
    )
    (net (code "155") (name "Net-(S-C-7-2)") (class "Default")
      (node (ref "CH-C8") (pin "1") (pinfunction "1_1") (pintype "passive"))
      (node (ref "S-C") (pin "B4") (pinfunction "7-2_B4") (pintype "passive"))
    )
    (net (code "156") (name "Net-(S-C-7-3)") (class "Default")
      (node (ref "CH-C9") (pin "1") (pinfunction "1_1") (pintype "passive"))
      (node (ref "S-C") (pin "C4") (pinfunction "7-3_C4") (pintype "passive"))
    )
    (net (code "157") (name "Net-(S-C-7-4)") (class "Default")
      (node (ref "CH-C7") (pin "2") (pinfunction "2_2") (pintype "passive"))
      (node (ref "S-C") (pin "A3") (pinfunction "7-4_A3") (pintype "passive"))
    )
    (net (code "158") (name "Net-(S-C-8-1)") (class "Default")
      (node (ref "CH-C8") (pin "2") (pinfunction "2_2") (pintype "passive"))
      (node (ref "S-C") (pin "B3") (pinfunction "8-1_B3") (pintype "passive"))
    )
    (net (code "159") (name "Net-(S-C-8-2)") (class "Default")
      (node (ref "CH-C9") (pin "2") (pinfunction "2_2") (pintype "passive"))
      (node (ref "S-C") (pin "C3") (pinfunction "8-2_C3") (pintype "passive"))
    )
    (net (code "160") (name "Net-(S-C-8-3)") (class "Default")
      (node (ref "CH-C7") (pin "3") (pinfunction "3_3") (pintype "passive"))
      (node (ref "S-C") (pin "A2") (pinfunction "8-3_A2") (pintype "passive"))
    )
    (net (code "161") (name "Net-(S-C-8-4)") (class "Default")
      (node (ref "CH-C8") (pin "3") (pinfunction "3_3") (pintype "passive"))
      (node (ref "S-C") (pin "B2") (pinfunction "8-4_B2") (pintype "passive"))
    )
    (net (code "162") (name "Net-(S-C-9-1)") (class "Default")
      (node (ref "CH-C9") (pin "3") (pinfunction "3_3") (pintype "passive"))
      (node (ref "S-C") (pin "C2") (pinfunction "9-1_C2") (pintype "passive"))
    )
    (net (code "163") (name "Net-(S-C-9-2)") (class "Default")
      (node (ref "CH-C7") (pin "4") (pinfunction "4_4") (pintype "passive"))
      (node (ref "S-C") (pin "A1") (pinfunction "9-2_A1") (pintype "passive"))
    )
    (net (code "164") (name "Net-(S-C-9-3)") (class "Default")
      (node (ref "CH-C8") (pin "4") (pinfunction "4_4") (pintype "passive"))
      (node (ref "S-C") (pin "B1") (pinfunction "9-3_B1") (pintype "passive"))
    )
    (net (code "165") (name "Net-(S-C-9-4)") (class "Default")
      (node (ref "CH-C9") (pin "4") (pinfunction "4_4") (pintype "passive"))
      (node (ref "S-C") (pin "C1") (pinfunction "9-4_C1") (pintype "passive"))
    )
    (net (code "166") (name "Net-(S-C-ARD)") (class "Default")
      (node (ref "AUNO") (pin "D4") (pinfunction "D4_D4") (pintype "passive"))
      (node (ref "S-C") (pin "C16") (pinfunction "ARD_C16") (pintype "passive"))
    )
    (net (code "167") (name "Net-(S-C-MISO)") (class "Default")
      (node (ref "S-C") (pin "B17") (pinfunction "MISO_B17") (pintype "passive"))
      (node (ref "S-D") (pin "B17") (pinfunction "MISO_B17") (pintype "passive"))
    )
    (net (code "168") (name "Net-(S-C-MOSI)") (class "Default")
      (node (ref "S-C") (pin "C17") (pinfunction "MOSI_C17") (pintype "passive"))
      (node (ref "S-D") (pin "C17") (pinfunction "MOSI_C17") (pintype "passive"))
    )
    (net (code "169") (name "Net-(S-C-SCK)") (class "Default")
      (node (ref "S-C") (pin "A16") (pinfunction "SCK_A16") (pintype "passive"))
      (node (ref "S-D") (pin "A16") (pinfunction "SCK_A16") (pintype "passive"))
    )
    (net (code "170") (name "Net-(S-C-SS)") (class "Default")
      (node (ref "S-C") (pin "A17") (pinfunction "SS_A17") (pintype "passive"))
      (node (ref "S-D") (pin "A17") (pinfunction "SS_A17") (pintype "passive"))
    )
    (net (code "171") (name "Net-(S-D-1-1)") (class "Default")
      (node (ref "CH-D1") (pin "1") (pinfunction "1_1") (pintype "passive"))
      (node (ref "S-D") (pin "A12") (pinfunction "1-1_A12") (pintype "passive"))
    )
    (net (code "172") (name "Net-(S-D-1-2)") (class "Default")
      (node (ref "CH-D2") (pin "1") (pinfunction "1_1") (pintype "passive"))
      (node (ref "S-D") (pin "B12") (pinfunction "1-2_B12") (pintype "passive"))
    )
    (net (code "173") (name "Net-(S-D-1-3)") (class "Default")
      (node (ref "CH-D3") (pin "1") (pinfunction "1_1") (pintype "passive"))
      (node (ref "S-D") (pin "C12") (pinfunction "1-3_C12") (pintype "passive"))
    )
    (net (code "174") (name "Net-(S-D-1-4)") (class "Default")
      (node (ref "CH-D1") (pin "2") (pinfunction "2_2") (pintype "passive"))
      (node (ref "S-D") (pin "A11") (pinfunction "1-4_A11") (pintype "passive"))
    )
    (net (code "175") (name "Net-(S-D-2-1)") (class "Default")
      (node (ref "CH-D2") (pin "2") (pinfunction "2_2") (pintype "passive"))
      (node (ref "S-D") (pin "B11") (pinfunction "2-1_B11") (pintype "passive"))
    )
    (net (code "176") (name "Net-(S-D-2-2)") (class "Default")
      (node (ref "CH-D3") (pin "2") (pinfunction "2_2") (pintype "passive"))
      (node (ref "S-D") (pin "C11") (pinfunction "2-2_C11") (pintype "passive"))
    )
    (net (code "177") (name "Net-(S-D-2-3)") (class "Default")
      (node (ref "CH-D1") (pin "3") (pinfunction "3_3") (pintype "passive"))
      (node (ref "S-D") (pin "A10") (pinfunction "2-3_A10") (pintype "passive"))
    )
    (net (code "178") (name "Net-(S-D-2-4)") (class "Default")
      (node (ref "CH-D2") (pin "3") (pinfunction "3_3") (pintype "passive"))
      (node (ref "S-D") (pin "B10") (pinfunction "2-4_B10") (pintype "passive"))
    )
    (net (code "179") (name "Net-(S-D-3-1)") (class "Default")
      (node (ref "CH-D3") (pin "3") (pinfunction "3_3") (pintype "passive"))
      (node (ref "S-D") (pin "C10") (pinfunction "3-1_C10") (pintype "passive"))
    )
    (net (code "180") (name "Net-(S-D-3-2)") (class "Default")
      (node (ref "CH-D1") (pin "4") (pinfunction "4_4") (pintype "passive"))
      (node (ref "S-D") (pin "A9") (pinfunction "3-2_A9") (pintype "passive"))
    )
    (net (code "181") (name "Net-(S-D-3-3)") (class "Default")
      (node (ref "CH-D2") (pin "4") (pinfunction "4_4") (pintype "passive"))
      (node (ref "S-D") (pin "B9") (pinfunction "3-3_B9") (pintype "passive"))
    )
    (net (code "182") (name "Net-(S-D-3-4)") (class "Default")
      (node (ref "CH-D3") (pin "4") (pinfunction "4_4") (pintype "passive"))
      (node (ref "S-D") (pin "C9") (pinfunction "3-4_C9") (pintype "passive"))
    )
    (net (code "183") (name "Net-(S-D-4-1)") (class "Default")
      (node (ref "CH-D4") (pin "1") (pinfunction "1_1") (pintype "passive"))
      (node (ref "S-D") (pin "A8") (pinfunction "4-1_A8") (pintype "passive"))
    )
    (net (code "184") (name "Net-(S-D-4-2)") (class "Default")
      (node (ref "CH-D5") (pin "1") (pinfunction "1_1") (pintype "passive"))
      (node (ref "S-D") (pin "B8") (pinfunction "4-2_B8") (pintype "passive"))
    )
    (net (code "185") (name "Net-(S-D-4-3)") (class "Default")
      (node (ref "CH-D6") (pin "1") (pinfunction "1_1") (pintype "passive"))
      (node (ref "S-D") (pin "C8") (pinfunction "4-3_C8") (pintype "passive"))
    )
    (net (code "186") (name "Net-(S-D-4-4)") (class "Default")
      (node (ref "CH-D4") (pin "2") (pinfunction "2_2") (pintype "passive"))
      (node (ref "S-D") (pin "A7") (pinfunction "4-4_A7") (pintype "passive"))
    )
    (net (code "187") (name "Net-(S-D-5-1)") (class "Default")
      (node (ref "CH-D5") (pin "2") (pinfunction "2_2") (pintype "passive"))
      (node (ref "S-D") (pin "B7") (pinfunction "5-1_B7") (pintype "passive"))
    )
    (net (code "188") (name "Net-(S-D-5-2)") (class "Default")
      (node (ref "CH-D6") (pin "2") (pinfunction "2_2") (pintype "passive"))
      (node (ref "S-D") (pin "C7") (pinfunction "5-2_C7") (pintype "passive"))
    )
    (net (code "189") (name "Net-(S-D-5-3)") (class "Default")
      (node (ref "CH-D4") (pin "3") (pinfunction "3_3") (pintype "passive"))
      (node (ref "S-D") (pin "A6") (pinfunction "5-3_A6") (pintype "passive"))
    )
    (net (code "190") (name "Net-(S-D-5-4)") (class "Default")
      (node (ref "CH-D5") (pin "3") (pinfunction "3_3") (pintype "passive"))
      (node (ref "S-D") (pin "B6") (pinfunction "5-4_B6") (pintype "passive"))
    )
    (net (code "191") (name "Net-(S-D-6-1)") (class "Default")
      (node (ref "CH-D6") (pin "3") (pinfunction "3_3") (pintype "passive"))
      (node (ref "S-D") (pin "C6") (pinfunction "6-1_C6") (pintype "passive"))
    )
    (net (code "192") (name "Net-(S-D-6-2)") (class "Default")
      (node (ref "CH-D4") (pin "4") (pinfunction "4_4") (pintype "passive"))
      (node (ref "S-D") (pin "A5") (pinfunction "6-2_A5") (pintype "passive"))
    )
    (net (code "193") (name "Net-(S-D-6-3)") (class "Default")
      (node (ref "CH-D5") (pin "4") (pinfunction "4_4") (pintype "passive"))
      (node (ref "S-D") (pin "B5") (pinfunction "6-3_B5") (pintype "passive"))
    )
    (net (code "194") (name "Net-(S-D-6-4)") (class "Default")
      (node (ref "CH-D6") (pin "4") (pinfunction "4_4") (pintype "passive"))
      (node (ref "S-D") (pin "C5") (pinfunction "6-4_C5") (pintype "passive"))
    )
    (net (code "195") (name "Net-(S-D-7-1)") (class "Default")
      (node (ref "CH-D7") (pin "1") (pinfunction "1_1") (pintype "passive"))
      (node (ref "S-D") (pin "A4") (pinfunction "7-1_A4") (pintype "passive"))
    )
    (net (code "196") (name "Net-(S-D-7-2)") (class "Default")
      (node (ref "CH-D8") (pin "1") (pinfunction "1_1") (pintype "passive"))
      (node (ref "S-D") (pin "B4") (pinfunction "7-2_B4") (pintype "passive"))
    )
    (net (code "197") (name "Net-(S-D-7-3)") (class "Default")
      (node (ref "CH-D9") (pin "1") (pinfunction "1_1") (pintype "passive"))
      (node (ref "S-D") (pin "C4") (pinfunction "7-3_C4") (pintype "passive"))
    )
    (net (code "198") (name "Net-(S-D-7-4)") (class "Default")
      (node (ref "CH-D7") (pin "2") (pinfunction "2_2") (pintype "passive"))
      (node (ref "S-D") (pin "A3") (pinfunction "7-4_A3") (pintype "passive"))
    )
    (net (code "199") (name "Net-(S-D-8-1)") (class "Default")
      (node (ref "CH-D8") (pin "2") (pinfunction "2_2") (pintype "passive"))
      (node (ref "S-D") (pin "B3") (pinfunction "8-1_B3") (pintype "passive"))
    )
    (net (code "200") (name "Net-(S-D-8-2)") (class "Default")
      (node (ref "CH-D9") (pin "2") (pinfunction "2_2") (pintype "passive"))
      (node (ref "S-D") (pin "C3") (pinfunction "8-2_C3") (pintype "passive"))
    )
    (net (code "201") (name "Net-(S-D-8-3)") (class "Default")
      (node (ref "CH-D7") (pin "3") (pinfunction "3_3") (pintype "passive"))
      (node (ref "S-D") (pin "A2") (pinfunction "8-3_A2") (pintype "passive"))
    )
    (net (code "202") (name "Net-(S-D-8-4)") (class "Default")
      (node (ref "CH-D8") (pin "3") (pinfunction "3_3") (pintype "passive"))
      (node (ref "S-D") (pin "B2") (pinfunction "8-4_B2") (pintype "passive"))
    )
    (net (code "203") (name "Net-(S-D-9-1)") (class "Default")
      (node (ref "CH-D9") (pin "3") (pinfunction "3_3") (pintype "passive"))
      (node (ref "S-D") (pin "C2") (pinfunction "9-1_C2") (pintype "passive"))
    )
    (net (code "204") (name "Net-(S-D-9-2)") (class "Default")
      (node (ref "CH-D7") (pin "4") (pinfunction "4_4") (pintype "passive"))
      (node (ref "S-D") (pin "A1") (pinfunction "9-2_A1") (pintype "passive"))
    )
    (net (code "205") (name "Net-(S-D-9-3)") (class "Default")
      (node (ref "CH-D8") (pin "4") (pinfunction "4_4") (pintype "passive"))
      (node (ref "S-D") (pin "B1") (pinfunction "9-3_B1") (pintype "passive"))
    )
    (net (code "206") (name "Net-(S-D-9-4)") (class "Default")
      (node (ref "CH-D9") (pin "4") (pinfunction "4_4") (pintype "passive"))
      (node (ref "S-D") (pin "C1") (pinfunction "9-4_C1") (pintype "passive"))
    )
    (net (code "207") (name "Net-(S-E-1-1)") (class "Default")
      (node (ref "CH-E1") (pin "1") (pinfunction "1_1") (pintype "passive"))
      (node (ref "S-E") (pin "A12") (pinfunction "1-1_A12") (pintype "passive"))
    )
    (net (code "208") (name "Net-(S-E-1-2)") (class "Default")
      (node (ref "CH-E2") (pin "1") (pinfunction "1_1") (pintype "passive"))
      (node (ref "S-E") (pin "B12") (pinfunction "1-2_B12") (pintype "passive"))
    )
    (net (code "209") (name "Net-(S-E-1-3)") (class "Default")
      (node (ref "CH-E3") (pin "1") (pinfunction "1_1") (pintype "passive"))
      (node (ref "S-E") (pin "C12") (pinfunction "1-3_C12") (pintype "passive"))
    )
    (net (code "210") (name "Net-(S-E-1-4)") (class "Default")
      (node (ref "CH-E1") (pin "2") (pinfunction "2_2") (pintype "passive"))
      (node (ref "S-E") (pin "A11") (pinfunction "1-4_A11") (pintype "passive"))
    )
    (net (code "211") (name "Net-(S-E-2-1)") (class "Default")
      (node (ref "CH-E2") (pin "2") (pinfunction "2_2") (pintype "passive"))
      (node (ref "S-E") (pin "B11") (pinfunction "2-1_B11") (pintype "passive"))
    )
    (net (code "212") (name "Net-(S-E-2-2)") (class "Default")
      (node (ref "CH-E3") (pin "2") (pinfunction "2_2") (pintype "passive"))
      (node (ref "S-E") (pin "C11") (pinfunction "2-2_C11") (pintype "passive"))
    )
    (net (code "213") (name "Net-(S-E-2-3)") (class "Default")
      (node (ref "CH-E1") (pin "3") (pinfunction "3_3") (pintype "passive"))
      (node (ref "S-E") (pin "A10") (pinfunction "2-3_A10") (pintype "passive"))
    )
    (net (code "214") (name "Net-(S-E-2-4)") (class "Default")
      (node (ref "CH-E2") (pin "3") (pinfunction "3_3") (pintype "passive"))
      (node (ref "S-E") (pin "B10") (pinfunction "2-4_B10") (pintype "passive"))
    )
    (net (code "215") (name "Net-(S-E-3-1)") (class "Default")
      (node (ref "CH-E3") (pin "3") (pinfunction "3_3") (pintype "passive"))
      (node (ref "S-E") (pin "C10") (pinfunction "3-1_C10") (pintype "passive"))
    )
    (net (code "216") (name "Net-(S-E-3-2)") (class "Default")
      (node (ref "CH-E1") (pin "4") (pinfunction "4_4") (pintype "passive"))
      (node (ref "S-E") (pin "A9") (pinfunction "3-2_A9") (pintype "passive"))
    )
    (net (code "217") (name "Net-(S-E-3-3)") (class "Default")
      (node (ref "CH-E2") (pin "4") (pinfunction "4_4") (pintype "passive"))
      (node (ref "S-E") (pin "B9") (pinfunction "3-3_B9") (pintype "passive"))
    )
    (net (code "218") (name "Net-(S-E-3-4)") (class "Default")
      (node (ref "CH-E3") (pin "4") (pinfunction "4_4") (pintype "passive"))
      (node (ref "S-E") (pin "C9") (pinfunction "3-4_C9") (pintype "passive"))
    )
    (net (code "219") (name "Net-(S-E-4-1)") (class "Default")
      (node (ref "CH-E4") (pin "1") (pinfunction "1_1") (pintype "passive"))
      (node (ref "S-E") (pin "A8") (pinfunction "4-1_A8") (pintype "passive"))
    )
    (net (code "220") (name "Net-(S-E-4-2)") (class "Default")
      (node (ref "CH-E5") (pin "1") (pinfunction "1_1") (pintype "passive"))
      (node (ref "S-E") (pin "B8") (pinfunction "4-2_B8") (pintype "passive"))
    )
    (net (code "221") (name "Net-(S-E-4-3)") (class "Default")
      (node (ref "CH-E6") (pin "1") (pinfunction "1_1") (pintype "passive"))
      (node (ref "S-E") (pin "C8") (pinfunction "4-3_C8") (pintype "passive"))
    )
    (net (code "222") (name "Net-(S-E-4-4)") (class "Default")
      (node (ref "CH-E4") (pin "2") (pinfunction "2_2") (pintype "passive"))
      (node (ref "S-E") (pin "A7") (pinfunction "4-4_A7") (pintype "passive"))
    )
    (net (code "223") (name "Net-(S-E-5-1)") (class "Default")
      (node (ref "CH-E5") (pin "2") (pinfunction "2_2") (pintype "passive"))
      (node (ref "S-E") (pin "B7") (pinfunction "5-1_B7") (pintype "passive"))
    )
    (net (code "224") (name "Net-(S-E-5-2)") (class "Default")
      (node (ref "CH-E6") (pin "2") (pinfunction "2_2") (pintype "passive"))
      (node (ref "S-E") (pin "C7") (pinfunction "5-2_C7") (pintype "passive"))
    )
    (net (code "225") (name "Net-(S-E-5-3)") (class "Default")
      (node (ref "CH-E4") (pin "3") (pinfunction "3_3") (pintype "passive"))
      (node (ref "S-E") (pin "A6") (pinfunction "5-3_A6") (pintype "passive"))
    )
    (net (code "226") (name "Net-(S-E-5-4)") (class "Default")
      (node (ref "CH-E5") (pin "3") (pinfunction "3_3") (pintype "passive"))
      (node (ref "S-E") (pin "B6") (pinfunction "5-4_B6") (pintype "passive"))
    )
    (net (code "227") (name "Net-(S-E-6-1)") (class "Default")
      (node (ref "CH-E6") (pin "3") (pinfunction "3_3") (pintype "passive"))
      (node (ref "S-E") (pin "C6") (pinfunction "6-1_C6") (pintype "passive"))
    )
    (net (code "228") (name "Net-(S-E-6-2)") (class "Default")
      (node (ref "CH-E4") (pin "4") (pinfunction "4_4") (pintype "passive"))
      (node (ref "S-E") (pin "A5") (pinfunction "6-2_A5") (pintype "passive"))
    )
    (net (code "229") (name "Net-(S-E-6-3)") (class "Default")
      (node (ref "CH-E5") (pin "4") (pinfunction "4_4") (pintype "passive"))
      (node (ref "S-E") (pin "B5") (pinfunction "6-3_B5") (pintype "passive"))
    )
    (net (code "230") (name "Net-(S-E-6-4)") (class "Default")
      (node (ref "CH-E6") (pin "4") (pinfunction "4_4") (pintype "passive"))
      (node (ref "S-E") (pin "C5") (pinfunction "6-4_C5") (pintype "passive"))
    )
    (net (code "231") (name "Net-(S-E-7-1)") (class "Default")
      (node (ref "CH-E7") (pin "1") (pinfunction "1_1") (pintype "passive"))
      (node (ref "S-E") (pin "A4") (pinfunction "7-1_A4") (pintype "passive"))
    )
    (net (code "232") (name "Net-(S-E-7-2)") (class "Default")
      (node (ref "CH-E8") (pin "1") (pinfunction "1_1") (pintype "passive"))
      (node (ref "S-E") (pin "B4") (pinfunction "7-2_B4") (pintype "passive"))
    )
    (net (code "233") (name "Net-(S-E-7-3)") (class "Default")
      (node (ref "CH-E9") (pin "1") (pinfunction "1_1") (pintype "passive"))
      (node (ref "S-E") (pin "C4") (pinfunction "7-3_C4") (pintype "passive"))
    )
    (net (code "234") (name "Net-(S-E-7-4)") (class "Default")
      (node (ref "CH-E7") (pin "2") (pinfunction "2_2") (pintype "passive"))
      (node (ref "S-E") (pin "A3") (pinfunction "7-4_A3") (pintype "passive"))
    )
    (net (code "235") (name "Net-(S-E-8-1)") (class "Default")
      (node (ref "CH-E8") (pin "2") (pinfunction "2_2") (pintype "passive"))
      (node (ref "S-E") (pin "B3") (pinfunction "8-1_B3") (pintype "passive"))
    )
    (net (code "236") (name "Net-(S-E-8-2)") (class "Default")
      (node (ref "CH-E9") (pin "2") (pinfunction "2_2") (pintype "passive"))
      (node (ref "S-E") (pin "C3") (pinfunction "8-2_C3") (pintype "passive"))
    )
    (net (code "237") (name "Net-(S-E-8-3)") (class "Default")
      (node (ref "CH-E7") (pin "3") (pinfunction "3_3") (pintype "passive"))
      (node (ref "S-E") (pin "A2") (pinfunction "8-3_A2") (pintype "passive"))
    )
    (net (code "238") (name "Net-(S-E-8-4)") (class "Default")
      (node (ref "CH-E8") (pin "3") (pinfunction "3_3") (pintype "passive"))
      (node (ref "S-E") (pin "B2") (pinfunction "8-4_B2") (pintype "passive"))
    )
    (net (code "239") (name "Net-(S-E-9-1)") (class "Default")
      (node (ref "CH-E9") (pin "3") (pinfunction "3_3") (pintype "passive"))
      (node (ref "S-E") (pin "C2") (pinfunction "9-1_C2") (pintype "passive"))
    )
    (net (code "240") (name "Net-(S-E-9-2)") (class "Default")
      (node (ref "CH-E7") (pin "4") (pinfunction "4_4") (pintype "passive"))
      (node (ref "S-E") (pin "A1") (pinfunction "9-2_A1") (pintype "passive"))
    )
    (net (code "241") (name "Net-(S-E-9-3)") (class "Default")
      (node (ref "CH-E8") (pin "4") (pinfunction "4_4") (pintype "passive"))
      (node (ref "S-E") (pin "B1") (pinfunction "9-3_B1") (pintype "passive"))
    )
    (net (code "242") (name "Net-(S-E-9-4)") (class "Default")
      (node (ref "CH-E9") (pin "4") (pinfunction "4_4") (pintype "passive"))
      (node (ref "S-E") (pin "C1") (pinfunction "9-4_C1") (pintype "passive"))
    )
    (net (code "243") (name "Net-(S-E-MISO)") (class "Default")
      (node (ref "S-E") (pin "B17") (pinfunction "MISO_B17") (pintype "passive"))
      (node (ref "S-F") (pin "B17") (pinfunction "MISO_B17") (pintype "passive"))
    )
    (net (code "244") (name "Net-(S-E-MOSI)") (class "Default")
      (node (ref "S-E") (pin "C17") (pinfunction "MOSI_C17") (pintype "passive"))
      (node (ref "S-F") (pin "C17") (pinfunction "MOSI_C17") (pintype "passive"))
    )
    (net (code "245") (name "Net-(S-E-SCK)") (class "Default")
      (node (ref "S-E") (pin "A16") (pinfunction "SCK_A16") (pintype "passive"))
      (node (ref "S-F") (pin "A16") (pinfunction "SCK_A16") (pintype "passive"))
    )
    (net (code "246") (name "Net-(S-E-SS)") (class "Default")
      (node (ref "S-E") (pin "A17") (pinfunction "SS_A17") (pintype "passive"))
      (node (ref "S-F") (pin "A17") (pinfunction "SS_A17") (pintype "passive"))
    )
    (net (code "247") (name "Net-(S-F-1-1)") (class "Default")
      (node (ref "CH-F1") (pin "1") (pinfunction "1_1") (pintype "passive"))
      (node (ref "S-F") (pin "A12") (pinfunction "1-1_A12") (pintype "passive"))
    )
    (net (code "248") (name "Net-(S-F-1-2)") (class "Default")
      (node (ref "CH-F2") (pin "1") (pinfunction "1_1") (pintype "passive"))
      (node (ref "S-F") (pin "B12") (pinfunction "1-2_B12") (pintype "passive"))
    )
    (net (code "249") (name "Net-(S-F-1-3)") (class "Default")
      (node (ref "CH-F3") (pin "1") (pinfunction "1_1") (pintype "passive"))
      (node (ref "S-F") (pin "C12") (pinfunction "1-3_C12") (pintype "passive"))
    )
    (net (code "250") (name "Net-(S-F-1-4)") (class "Default")
      (node (ref "CH-F1") (pin "2") (pinfunction "2_2") (pintype "passive"))
      (node (ref "S-F") (pin "A11") (pinfunction "1-4_A11") (pintype "passive"))
    )
    (net (code "251") (name "Net-(S-F-2-1)") (class "Default")
      (node (ref "CH-F2") (pin "2") (pinfunction "2_2") (pintype "passive"))
      (node (ref "S-F") (pin "B11") (pinfunction "2-1_B11") (pintype "passive"))
    )
    (net (code "252") (name "Net-(S-F-2-2)") (class "Default")
      (node (ref "CH-F3") (pin "2") (pinfunction "2_2") (pintype "passive"))
      (node (ref "S-F") (pin "C11") (pinfunction "2-2_C11") (pintype "passive"))
    )
    (net (code "253") (name "Net-(S-F-2-3)") (class "Default")
      (node (ref "CH-F1") (pin "3") (pinfunction "3_3") (pintype "passive"))
      (node (ref "S-F") (pin "A10") (pinfunction "2-3_A10") (pintype "passive"))
    )
    (net (code "254") (name "Net-(S-F-2-4)") (class "Default")
      (node (ref "CH-F2") (pin "3") (pinfunction "3_3") (pintype "passive"))
      (node (ref "S-F") (pin "B10") (pinfunction "2-4_B10") (pintype "passive"))
    )
    (net (code "255") (name "Net-(S-F-3-1)") (class "Default")
      (node (ref "CH-F3") (pin "3") (pinfunction "3_3") (pintype "passive"))
      (node (ref "S-F") (pin "C10") (pinfunction "3-1_C10") (pintype "passive"))
    )
    (net (code "256") (name "Net-(S-F-3-2)") (class "Default")
      (node (ref "CH-F1") (pin "4") (pinfunction "4_4") (pintype "passive"))
      (node (ref "S-F") (pin "A9") (pinfunction "3-2_A9") (pintype "passive"))
    )
    (net (code "257") (name "Net-(S-F-3-3)") (class "Default")
      (node (ref "CH-F2") (pin "4") (pinfunction "4_4") (pintype "passive"))
      (node (ref "S-F") (pin "B9") (pinfunction "3-3_B9") (pintype "passive"))
    )
    (net (code "258") (name "Net-(S-F-3-4)") (class "Default")
      (node (ref "CH-F3") (pin "4") (pinfunction "4_4") (pintype "passive"))
      (node (ref "S-F") (pin "C9") (pinfunction "3-4_C9") (pintype "passive"))
    )
    (net (code "259") (name "Net-(S-F-4-1)") (class "Default")
      (node (ref "CH-F4") (pin "1") (pinfunction "1_1") (pintype "passive"))
      (node (ref "S-F") (pin "A8") (pinfunction "4-1_A8") (pintype "passive"))
    )
    (net (code "260") (name "Net-(S-F-4-2)") (class "Default")
      (node (ref "CH-F5") (pin "1") (pinfunction "1_1") (pintype "passive"))
      (node (ref "S-F") (pin "B8") (pinfunction "4-2_B8") (pintype "passive"))
    )
    (net (code "261") (name "Net-(S-F-4-3)") (class "Default")
      (node (ref "CH-F6") (pin "1") (pinfunction "1_1") (pintype "passive"))
      (node (ref "S-F") (pin "C8") (pinfunction "4-3_C8") (pintype "passive"))
    )
    (net (code "262") (name "Net-(S-F-4-4)") (class "Default")
      (node (ref "CH-F4") (pin "2") (pinfunction "2_2") (pintype "passive"))
      (node (ref "S-F") (pin "A7") (pinfunction "4-4_A7") (pintype "passive"))
    )
    (net (code "263") (name "Net-(S-F-5-1)") (class "Default")
      (node (ref "CH-F5") (pin "2") (pinfunction "2_2") (pintype "passive"))
      (node (ref "S-F") (pin "B7") (pinfunction "5-1_B7") (pintype "passive"))
    )
    (net (code "264") (name "Net-(S-F-5-2)") (class "Default")
      (node (ref "CH-F6") (pin "2") (pinfunction "2_2") (pintype "passive"))
      (node (ref "S-F") (pin "C7") (pinfunction "5-2_C7") (pintype "passive"))
    )
    (net (code "265") (name "Net-(S-F-5-3)") (class "Default")
      (node (ref "CH-F4") (pin "3") (pinfunction "3_3") (pintype "passive"))
      (node (ref "S-F") (pin "A6") (pinfunction "5-3_A6") (pintype "passive"))
    )
    (net (code "266") (name "Net-(S-F-5-4)") (class "Default")
      (node (ref "CH-F5") (pin "3") (pinfunction "3_3") (pintype "passive"))
      (node (ref "S-F") (pin "B6") (pinfunction "5-4_B6") (pintype "passive"))
    )
    (net (code "267") (name "Net-(S-F-6-1)") (class "Default")
      (node (ref "CH-F6") (pin "3") (pinfunction "3_3") (pintype "passive"))
      (node (ref "S-F") (pin "C6") (pinfunction "6-1_C6") (pintype "passive"))
    )
    (net (code "268") (name "Net-(S-F-6-2)") (class "Default")
      (node (ref "CH-F4") (pin "4") (pinfunction "4_4") (pintype "passive"))
      (node (ref "S-F") (pin "A5") (pinfunction "6-2_A5") (pintype "passive"))
    )
    (net (code "269") (name "Net-(S-F-6-3)") (class "Default")
      (node (ref "CH-F5") (pin "4") (pinfunction "4_4") (pintype "passive"))
      (node (ref "S-F") (pin "B5") (pinfunction "6-3_B5") (pintype "passive"))
    )
    (net (code "270") (name "Net-(S-F-6-4)") (class "Default")
      (node (ref "CH-F6") (pin "4") (pinfunction "4_4") (pintype "passive"))
      (node (ref "S-F") (pin "C5") (pinfunction "6-4_C5") (pintype "passive"))
    )
    (net (code "271") (name "Net-(S-F-7-1)") (class "Default")
      (node (ref "CH-F7") (pin "1") (pinfunction "1_1") (pintype "passive"))
      (node (ref "S-F") (pin "A4") (pinfunction "7-1_A4") (pintype "passive"))
    )
    (net (code "272") (name "Net-(S-F-7-2)") (class "Default")
      (node (ref "CH-F8") (pin "1") (pinfunction "1_1") (pintype "passive"))
      (node (ref "S-F") (pin "B4") (pinfunction "7-2_B4") (pintype "passive"))
    )
    (net (code "273") (name "Net-(S-F-7-3)") (class "Default")
      (node (ref "CH-F9") (pin "1") (pinfunction "1_1") (pintype "passive"))
      (node (ref "S-F") (pin "C4") (pinfunction "7-3_C4") (pintype "passive"))
    )
    (net (code "274") (name "Net-(S-F-7-4)") (class "Default")
      (node (ref "CH-F7") (pin "2") (pinfunction "2_2") (pintype "passive"))
      (node (ref "S-F") (pin "A3") (pinfunction "7-4_A3") (pintype "passive"))
    )
    (net (code "275") (name "Net-(S-F-8-1)") (class "Default")
      (node (ref "CH-F8") (pin "2") (pinfunction "2_2") (pintype "passive"))
      (node (ref "S-F") (pin "B3") (pinfunction "8-1_B3") (pintype "passive"))
    )
    (net (code "276") (name "Net-(S-F-8-2)") (class "Default")
      (node (ref "CH-F9") (pin "2") (pinfunction "2_2") (pintype "passive"))
      (node (ref "S-F") (pin "C3") (pinfunction "8-2_C3") (pintype "passive"))
    )
    (net (code "277") (name "Net-(S-F-8-3)") (class "Default")
      (node (ref "CH-F7") (pin "3") (pinfunction "3_3") (pintype "passive"))
      (node (ref "S-F") (pin "A2") (pinfunction "8-3_A2") (pintype "passive"))
    )
    (net (code "278") (name "Net-(S-F-8-4)") (class "Default")
      (node (ref "CH-F8") (pin "3") (pinfunction "3_3") (pintype "passive"))
      (node (ref "S-F") (pin "B2") (pinfunction "8-4_B2") (pintype "passive"))
    )
    (net (code "279") (name "Net-(S-F-9-1)") (class "Default")
      (node (ref "CH-F9") (pin "3") (pinfunction "3_3") (pintype "passive"))
      (node (ref "S-F") (pin "C2") (pinfunction "9-1_C2") (pintype "passive"))
    )
    (net (code "280") (name "Net-(S-F-9-2)") (class "Default")
      (node (ref "CH-F7") (pin "4") (pinfunction "4_4") (pintype "passive"))
      (node (ref "S-F") (pin "A1") (pinfunction "9-2_A1") (pintype "passive"))
    )
    (net (code "281") (name "Net-(S-F-9-3)") (class "Default")
      (node (ref "CH-F8") (pin "4") (pinfunction "4_4") (pintype "passive"))
      (node (ref "S-F") (pin "B1") (pinfunction "9-3_B1") (pintype "passive"))
    )
    (net (code "282") (name "Net-(S-F-9-4)") (class "Default")
      (node (ref "CH-F9") (pin "4") (pinfunction "4_4") (pintype "passive"))
      (node (ref "S-F") (pin "C1") (pinfunction "9-4_C1") (pintype "passive"))
    )
    (net (code "283") (name "Net-(S-F-ARD)") (class "Default")
      (node (ref "AUNO") (pin "D7") (pinfunction "D7_D7") (pintype "passive"))
      (node (ref "S-F") (pin "C16") (pinfunction "ARD_C16") (pintype "passive"))
    )
    (net (code "284") (name "Net-(S-G-1-1)") (class "Default")
      (node (ref "CH-G1") (pin "1") (pinfunction "1_1") (pintype "passive"))
      (node (ref "S-G") (pin "A12") (pinfunction "1-1_A12") (pintype "passive"))
    )
    (net (code "285") (name "Net-(S-G-1-2)") (class "Default")
      (node (ref "CH-G2") (pin "1") (pinfunction "1_1") (pintype "passive"))
      (node (ref "S-G") (pin "B12") (pinfunction "1-2_B12") (pintype "passive"))
    )
    (net (code "286") (name "Net-(S-G-1-3)") (class "Default")
      (node (ref "CH-G3") (pin "1") (pinfunction "1_1") (pintype "passive"))
      (node (ref "S-G") (pin "C12") (pinfunction "1-3_C12") (pintype "passive"))
    )
    (net (code "287") (name "Net-(S-G-1-4)") (class "Default")
      (node (ref "CH-G1") (pin "2") (pinfunction "2_2") (pintype "passive"))
      (node (ref "S-G") (pin "A11") (pinfunction "1-4_A11") (pintype "passive"))
    )
    (net (code "288") (name "Net-(S-G-2-1)") (class "Default")
      (node (ref "CH-G2") (pin "2") (pinfunction "2_2") (pintype "passive"))
      (node (ref "S-G") (pin "B11") (pinfunction "2-1_B11") (pintype "passive"))
    )
    (net (code "289") (name "Net-(S-G-2-2)") (class "Default")
      (node (ref "CH-G3") (pin "2") (pinfunction "2_2") (pintype "passive"))
      (node (ref "S-G") (pin "C11") (pinfunction "2-2_C11") (pintype "passive"))
    )
    (net (code "290") (name "Net-(S-G-2-3)") (class "Default")
      (node (ref "CH-G1") (pin "3") (pinfunction "3_3") (pintype "passive"))
      (node (ref "S-G") (pin "A10") (pinfunction "2-3_A10") (pintype "passive"))
    )
    (net (code "291") (name "Net-(S-G-2-4)") (class "Default")
      (node (ref "CH-G2") (pin "3") (pinfunction "3_3") (pintype "passive"))
      (node (ref "S-G") (pin "B10") (pinfunction "2-4_B10") (pintype "passive"))
    )
    (net (code "292") (name "Net-(S-G-3-1)") (class "Default")
      (node (ref "CH-G3") (pin "3") (pinfunction "3_3") (pintype "passive"))
      (node (ref "S-G") (pin "C10") (pinfunction "3-1_C10") (pintype "passive"))
    )
    (net (code "293") (name "Net-(S-G-3-2)") (class "Default")
      (node (ref "CH-G1") (pin "4") (pinfunction "4_4") (pintype "passive"))
      (node (ref "S-G") (pin "A9") (pinfunction "3-2_A9") (pintype "passive"))
    )
    (net (code "294") (name "Net-(S-G-3-3)") (class "Default")
      (node (ref "CH-G2") (pin "4") (pinfunction "4_4") (pintype "passive"))
      (node (ref "S-G") (pin "B9") (pinfunction "3-3_B9") (pintype "passive"))
    )
    (net (code "295") (name "Net-(S-G-3-4)") (class "Default")
      (node (ref "CH-G3") (pin "4") (pinfunction "4_4") (pintype "passive"))
      (node (ref "S-G") (pin "C9") (pinfunction "3-4_C9") (pintype "passive"))
    )
    (net (code "296") (name "Net-(S-G-4-1)") (class "Default")
      (node (ref "CH-G4") (pin "1") (pinfunction "1_1") (pintype "passive"))
      (node (ref "S-G") (pin "A8") (pinfunction "4-1_A8") (pintype "passive"))
    )
    (net (code "297") (name "Net-(S-G-4-2)") (class "Default")
      (node (ref "CH-G5") (pin "1") (pinfunction "1_1") (pintype "passive"))
      (node (ref "S-G") (pin "B8") (pinfunction "4-2_B8") (pintype "passive"))
    )
    (net (code "298") (name "Net-(S-G-4-3)") (class "Default")
      (node (ref "CH-G6") (pin "1") (pinfunction "1_1") (pintype "passive"))
      (node (ref "S-G") (pin "C8") (pinfunction "4-3_C8") (pintype "passive"))
    )
    (net (code "299") (name "Net-(S-G-4-4)") (class "Default")
      (node (ref "CH-G4") (pin "2") (pinfunction "2_2") (pintype "passive"))
      (node (ref "S-G") (pin "A7") (pinfunction "4-4_A7") (pintype "passive"))
    )
    (net (code "300") (name "Net-(S-G-5-1)") (class "Default")
      (node (ref "CH-G5") (pin "2") (pinfunction "2_2") (pintype "passive"))
      (node (ref "S-G") (pin "B7") (pinfunction "5-1_B7") (pintype "passive"))
    )
    (net (code "301") (name "Net-(S-G-5-2)") (class "Default")
      (node (ref "CH-G6") (pin "2") (pinfunction "2_2") (pintype "passive"))
      (node (ref "S-G") (pin "C7") (pinfunction "5-2_C7") (pintype "passive"))
    )
    (net (code "302") (name "Net-(S-G-5-3)") (class "Default")
      (node (ref "CH-G4") (pin "3") (pinfunction "3_3") (pintype "passive"))
      (node (ref "S-G") (pin "A6") (pinfunction "5-3_A6") (pintype "passive"))
    )
    (net (code "303") (name "Net-(S-G-5-4)") (class "Default")
      (node (ref "CH-G5") (pin "3") (pinfunction "3_3") (pintype "passive"))
      (node (ref "S-G") (pin "B6") (pinfunction "5-4_B6") (pintype "passive"))
    )
    (net (code "304") (name "Net-(S-G-6-1)") (class "Default")
      (node (ref "CH-G6") (pin "3") (pinfunction "3_3") (pintype "passive"))
      (node (ref "S-G") (pin "C6") (pinfunction "6-1_C6") (pintype "passive"))
    )
    (net (code "305") (name "Net-(S-G-6-2)") (class "Default")
      (node (ref "CH-G4") (pin "4") (pinfunction "4_4") (pintype "passive"))
      (node (ref "S-G") (pin "A5") (pinfunction "6-2_A5") (pintype "passive"))
    )
    (net (code "306") (name "Net-(S-G-6-3)") (class "Default")
      (node (ref "CH-G5") (pin "4") (pinfunction "4_4") (pintype "passive"))
      (node (ref "S-G") (pin "B5") (pinfunction "6-3_B5") (pintype "passive"))
    )
    (net (code "307") (name "Net-(S-G-6-4)") (class "Default")
      (node (ref "CH-G6") (pin "4") (pinfunction "4_4") (pintype "passive"))
      (node (ref "S-G") (pin "C5") (pinfunction "6-4_C5") (pintype "passive"))
    )
    (net (code "308") (name "Net-(S-G-7-1)") (class "Default")
      (node (ref "CH-G7") (pin "1") (pinfunction "1_1") (pintype "passive"))
      (node (ref "S-G") (pin "A4") (pinfunction "7-1_A4") (pintype "passive"))
    )
    (net (code "309") (name "Net-(S-G-7-2)") (class "Default")
      (node (ref "CH-G8") (pin "1") (pinfunction "1_1") (pintype "passive"))
      (node (ref "S-G") (pin "B4") (pinfunction "7-2_B4") (pintype "passive"))
    )
    (net (code "310") (name "Net-(S-G-7-3)") (class "Default")
      (node (ref "CH-G9") (pin "1") (pinfunction "1_1") (pintype "passive"))
      (node (ref "S-G") (pin "C4") (pinfunction "7-3_C4") (pintype "passive"))
    )
    (net (code "311") (name "Net-(S-G-7-4)") (class "Default")
      (node (ref "CH-G7") (pin "2") (pinfunction "2_2") (pintype "passive"))
      (node (ref "S-G") (pin "A3") (pinfunction "7-4_A3") (pintype "passive"))
    )
    (net (code "312") (name "Net-(S-G-8-1)") (class "Default")
      (node (ref "CH-G8") (pin "2") (pinfunction "2_2") (pintype "passive"))
      (node (ref "S-G") (pin "B3") (pinfunction "8-1_B3") (pintype "passive"))
    )
    (net (code "313") (name "Net-(S-G-8-2)") (class "Default")
      (node (ref "CH-G9") (pin "2") (pinfunction "2_2") (pintype "passive"))
      (node (ref "S-G") (pin "C3") (pinfunction "8-2_C3") (pintype "passive"))
    )
    (net (code "314") (name "Net-(S-G-8-3)") (class "Default")
      (node (ref "CH-G7") (pin "3") (pinfunction "3_3") (pintype "passive"))
      (node (ref "S-G") (pin "A2") (pinfunction "8-3_A2") (pintype "passive"))
    )
    (net (code "315") (name "Net-(S-G-8-4)") (class "Default")
      (node (ref "CH-G8") (pin "3") (pinfunction "3_3") (pintype "passive"))
      (node (ref "S-G") (pin "B2") (pinfunction "8-4_B2") (pintype "passive"))
    )
    (net (code "316") (name "Net-(S-G-9-1)") (class "Default")
      (node (ref "CH-G9") (pin "3") (pinfunction "3_3") (pintype "passive"))
      (node (ref "S-G") (pin "C2") (pinfunction "9-1_C2") (pintype "passive"))
    )
    (net (code "317") (name "Net-(S-G-9-2)") (class "Default")
      (node (ref "CH-G7") (pin "4") (pinfunction "4_4") (pintype "passive"))
      (node (ref "S-G") (pin "A1") (pinfunction "9-2_A1") (pintype "passive"))
    )
    (net (code "318") (name "Net-(S-G-9-3)") (class "Default")
      (node (ref "CH-G8") (pin "4") (pinfunction "4_4") (pintype "passive"))
      (node (ref "S-G") (pin "B1") (pinfunction "9-3_B1") (pintype "passive"))
    )
    (net (code "319") (name "Net-(S-G-9-4)") (class "Default")
      (node (ref "CH-G9") (pin "4") (pinfunction "4_4") (pintype "passive"))
      (node (ref "S-G") (pin "C1") (pinfunction "9-4_C1") (pintype "passive"))
    )
    (net (code "320") (name "Net-(S-G-ARD)") (class "Default")
      (node (ref "AUNO") (pin "D8") (pinfunction "D8_D8") (pintype "passive"))
      (node (ref "S-G") (pin "C16") (pinfunction "ARD_C16") (pintype "passive"))
    )
    (net (code "321") (name "Net-(S-G-MISO)") (class "Default")
      (node (ref "S-G") (pin "B17") (pinfunction "MISO_B17") (pintype "passive"))
      (node (ref "S-H") (pin "B17") (pinfunction "MISO_B17") (pintype "passive"))
    )
    (net (code "322") (name "Net-(S-G-MOSI)") (class "Default")
      (node (ref "S-G") (pin "C17") (pinfunction "MOSI_C17") (pintype "passive"))
      (node (ref "S-H") (pin "C17") (pinfunction "MOSI_C17") (pintype "passive"))
    )
    (net (code "323") (name "Net-(S-G-SCK)") (class "Default")
      (node (ref "S-G") (pin "A16") (pinfunction "SCK_A16") (pintype "passive"))
      (node (ref "S-H") (pin "A16") (pinfunction "SCK_A16") (pintype "passive"))
    )
    (net (code "324") (name "Net-(S-G-SS)") (class "Default")
      (node (ref "S-G") (pin "A17") (pinfunction "SS_A17") (pintype "passive"))
      (node (ref "S-H") (pin "A17") (pinfunction "SS_A17") (pintype "passive"))
    )
    (net (code "325") (name "Net-(S-H-1-1)") (class "Default")
      (node (ref "CH-H1") (pin "1") (pinfunction "1_1") (pintype "passive"))
      (node (ref "S-H") (pin "A12") (pinfunction "1-1_A12") (pintype "passive"))
    )
    (net (code "326") (name "Net-(S-H-1-2)") (class "Default")
      (node (ref "CH-H2") (pin "1") (pinfunction "1_1") (pintype "passive"))
      (node (ref "S-H") (pin "B12") (pinfunction "1-2_B12") (pintype "passive"))
    )
    (net (code "327") (name "Net-(S-H-1-3)") (class "Default")
      (node (ref "CH-H3") (pin "1") (pinfunction "1_1") (pintype "passive"))
      (node (ref "S-H") (pin "C12") (pinfunction "1-3_C12") (pintype "passive"))
    )
    (net (code "328") (name "Net-(S-H-1-4)") (class "Default")
      (node (ref "CH-H1") (pin "2") (pinfunction "2_2") (pintype "passive"))
      (node (ref "S-H") (pin "A11") (pinfunction "1-4_A11") (pintype "passive"))
    )
    (net (code "329") (name "Net-(S-H-2-1)") (class "Default")
      (node (ref "CH-H2") (pin "2") (pinfunction "2_2") (pintype "passive"))
      (node (ref "S-H") (pin "B11") (pinfunction "2-1_B11") (pintype "passive"))
    )
    (net (code "330") (name "Net-(S-H-2-2)") (class "Default")
      (node (ref "CH-H3") (pin "2") (pinfunction "2_2") (pintype "passive"))
      (node (ref "S-H") (pin "C11") (pinfunction "2-2_C11") (pintype "passive"))
    )
    (net (code "331") (name "Net-(S-H-2-3)") (class "Default")
      (node (ref "CH-H1") (pin "3") (pinfunction "3_3") (pintype "passive"))
      (node (ref "S-H") (pin "A10") (pinfunction "2-3_A10") (pintype "passive"))
    )
    (net (code "332") (name "Net-(S-H-2-4)") (class "Default")
      (node (ref "CH-H2") (pin "3") (pinfunction "3_3") (pintype "passive"))
      (node (ref "S-H") (pin "B10") (pinfunction "2-4_B10") (pintype "passive"))
    )
    (net (code "333") (name "Net-(S-H-3-1)") (class "Default")
      (node (ref "CH-H3") (pin "3") (pinfunction "3_3") (pintype "passive"))
      (node (ref "S-H") (pin "C10") (pinfunction "3-1_C10") (pintype "passive"))
    )
    (net (code "334") (name "Net-(S-H-3-2)") (class "Default")
      (node (ref "CH-H1") (pin "4") (pinfunction "4_4") (pintype "passive"))
      (node (ref "S-H") (pin "A9") (pinfunction "3-2_A9") (pintype "passive"))
    )
    (net (code "335") (name "Net-(S-H-3-3)") (class "Default")
      (node (ref "CH-H2") (pin "4") (pinfunction "4_4") (pintype "passive"))
      (node (ref "S-H") (pin "B9") (pinfunction "3-3_B9") (pintype "passive"))
    )
    (net (code "336") (name "Net-(S-H-3-4)") (class "Default")
      (node (ref "CH-H3") (pin "4") (pinfunction "4_4") (pintype "passive"))
      (node (ref "S-H") (pin "C9") (pinfunction "3-4_C9") (pintype "passive"))
    )
    (net (code "337") (name "Net-(S-H-4-1)") (class "Default")
      (node (ref "CH-H4") (pin "1") (pinfunction "1_1") (pintype "passive"))
      (node (ref "S-H") (pin "A8") (pinfunction "4-1_A8") (pintype "passive"))
    )
    (net (code "338") (name "Net-(S-H-4-2)") (class "Default")
      (node (ref "CH-H5") (pin "1") (pinfunction "1_1") (pintype "passive"))
      (node (ref "S-H") (pin "B8") (pinfunction "4-2_B8") (pintype "passive"))
    )
    (net (code "339") (name "Net-(S-H-4-3)") (class "Default")
      (node (ref "CH-H6") (pin "1") (pinfunction "1_1") (pintype "passive"))
      (node (ref "S-H") (pin "C8") (pinfunction "4-3_C8") (pintype "passive"))
    )
    (net (code "340") (name "Net-(S-H-4-4)") (class "Default")
      (node (ref "CH-H4") (pin "2") (pinfunction "2_2") (pintype "passive"))
      (node (ref "S-H") (pin "A7") (pinfunction "4-4_A7") (pintype "passive"))
    )
    (net (code "341") (name "Net-(S-H-5-1)") (class "Default")
      (node (ref "CH-H5") (pin "2") (pinfunction "2_2") (pintype "passive"))
      (node (ref "S-H") (pin "B7") (pinfunction "5-1_B7") (pintype "passive"))
    )
    (net (code "342") (name "Net-(S-H-5-2)") (class "Default")
      (node (ref "CH-H6") (pin "2") (pinfunction "2_2") (pintype "passive"))
      (node (ref "S-H") (pin "C7") (pinfunction "5-2_C7") (pintype "passive"))
    )
    (net (code "343") (name "Net-(S-H-5-3)") (class "Default")
      (node (ref "CH-H4") (pin "3") (pinfunction "3_3") (pintype "passive"))
      (node (ref "S-H") (pin "A6") (pinfunction "5-3_A6") (pintype "passive"))
    )
    (net (code "344") (name "Net-(S-H-5-4)") (class "Default")
      (node (ref "CH-H5") (pin "3") (pinfunction "3_3") (pintype "passive"))
      (node (ref "S-H") (pin "B6") (pinfunction "5-4_B6") (pintype "passive"))
    )
    (net (code "345") (name "Net-(S-H-6-1)") (class "Default")
      (node (ref "CH-H6") (pin "3") (pinfunction "3_3") (pintype "passive"))
      (node (ref "S-H") (pin "C6") (pinfunction "6-1_C6") (pintype "passive"))
    )
    (net (code "346") (name "Net-(S-H-6-2)") (class "Default")
      (node (ref "CH-H4") (pin "4") (pinfunction "4_4") (pintype "passive"))
      (node (ref "S-H") (pin "A5") (pinfunction "6-2_A5") (pintype "passive"))
    )
    (net (code "347") (name "Net-(S-H-6-3)") (class "Default")
      (node (ref "CH-H5") (pin "4") (pinfunction "4_4") (pintype "passive"))
      (node (ref "S-H") (pin "B5") (pinfunction "6-3_B5") (pintype "passive"))
    )
    (net (code "348") (name "Net-(S-H-6-4)") (class "Default")
      (node (ref "CH-H6") (pin "4") (pinfunction "4_4") (pintype "passive"))
      (node (ref "S-H") (pin "C5") (pinfunction "6-4_C5") (pintype "passive"))
    )
    (net (code "349") (name "Net-(S-H-7-1)") (class "Default")
      (node (ref "CH-H7") (pin "1") (pinfunction "1_1") (pintype "passive"))
      (node (ref "S-H") (pin "A4") (pinfunction "7-1_A4") (pintype "passive"))
    )
    (net (code "350") (name "Net-(S-H-7-2)") (class "Default")
      (node (ref "CH-H8") (pin "1") (pinfunction "1_1") (pintype "passive"))
      (node (ref "S-H") (pin "B4") (pinfunction "7-2_B4") (pintype "passive"))
    )
    (net (code "351") (name "Net-(S-H-7-3)") (class "Default")
      (node (ref "CH-H9") (pin "1") (pinfunction "1_1") (pintype "passive"))
      (node (ref "S-H") (pin "C4") (pinfunction "7-3_C4") (pintype "passive"))
    )
    (net (code "352") (name "Net-(S-H-7-4)") (class "Default")
      (node (ref "CH-H7") (pin "2") (pinfunction "2_2") (pintype "passive"))
      (node (ref "S-H") (pin "A3") (pinfunction "7-4_A3") (pintype "passive"))
    )
    (net (code "353") (name "Net-(S-H-8-1)") (class "Default")
      (node (ref "CH-H8") (pin "2") (pinfunction "2_2") (pintype "passive"))
      (node (ref "S-H") (pin "B3") (pinfunction "8-1_B3") (pintype "passive"))
    )
    (net (code "354") (name "Net-(S-H-8-2)") (class "Default")
      (node (ref "CH-H9") (pin "2") (pinfunction "2_2") (pintype "passive"))
      (node (ref "S-H") (pin "C3") (pinfunction "8-2_C3") (pintype "passive"))
    )
    (net (code "355") (name "Net-(S-H-8-3)") (class "Default")
      (node (ref "CH-H7") (pin "3") (pinfunction "3_3") (pintype "passive"))
      (node (ref "S-H") (pin "A2") (pinfunction "8-3_A2") (pintype "passive"))
    )
    (net (code "356") (name "Net-(S-H-8-4)") (class "Default")
      (node (ref "CH-H8") (pin "3") (pinfunction "3_3") (pintype "passive"))
      (node (ref "S-H") (pin "B2") (pinfunction "8-4_B2") (pintype "passive"))
    )
    (net (code "357") (name "Net-(S-H-9-1)") (class "Default")
      (node (ref "CH-H9") (pin "3") (pinfunction "3_3") (pintype "passive"))
      (node (ref "S-H") (pin "C2") (pinfunction "9-1_C2") (pintype "passive"))
    )
    (net (code "358") (name "Net-(S-H-9-2)") (class "Default")
      (node (ref "CH-H7") (pin "4") (pinfunction "4_4") (pintype "passive"))
      (node (ref "S-H") (pin "A1") (pinfunction "9-2_A1") (pintype "passive"))
    )
    (net (code "359") (name "Net-(S-H-9-3)") (class "Default")
      (node (ref "CH-H8") (pin "4") (pinfunction "4_4") (pintype "passive"))
      (node (ref "S-H") (pin "B1") (pinfunction "9-3_B1") (pintype "passive"))
    )
    (net (code "360") (name "Net-(S-H-9-4)") (class "Default")
      (node (ref "CH-H9") (pin "4") (pinfunction "4_4") (pintype "passive"))
      (node (ref "S-H") (pin "C1") (pinfunction "9-4_C1") (pintype "passive"))
    )
    (net (code "361") (name "Net-(S-I-1-1)") (class "Default")
      (node (ref "CH-I1") (pin "1") (pinfunction "1_1") (pintype "passive"))
      (node (ref "S-I") (pin "A12") (pinfunction "1-1_A12") (pintype "passive"))
    )
    (net (code "362") (name "Net-(S-I-1-2)") (class "Default")
      (node (ref "CH-I2") (pin "1") (pinfunction "1_1") (pintype "passive"))
      (node (ref "S-I") (pin "B12") (pinfunction "1-2_B12") (pintype "passive"))
    )
    (net (code "363") (name "Net-(S-I-1-3)") (class "Default")
      (node (ref "CH-I3") (pin "1") (pinfunction "1_1") (pintype "passive"))
      (node (ref "S-I") (pin "C12") (pinfunction "1-3_C12") (pintype "passive"))
    )
    (net (code "364") (name "Net-(S-I-1-4)") (class "Default")
      (node (ref "CH-I1") (pin "2") (pinfunction "2_2") (pintype "passive"))
      (node (ref "S-I") (pin "A11") (pinfunction "1-4_A11") (pintype "passive"))
    )
    (net (code "365") (name "Net-(S-I-2-1)") (class "Default")
      (node (ref "CH-I2") (pin "2") (pinfunction "2_2") (pintype "passive"))
      (node (ref "S-I") (pin "B11") (pinfunction "2-1_B11") (pintype "passive"))
    )
    (net (code "366") (name "Net-(S-I-2-2)") (class "Default")
      (node (ref "CH-I3") (pin "2") (pinfunction "2_2") (pintype "passive"))
      (node (ref "S-I") (pin "C11") (pinfunction "2-2_C11") (pintype "passive"))
    )
    (net (code "367") (name "Net-(S-I-2-3)") (class "Default")
      (node (ref "CH-I1") (pin "3") (pinfunction "3_3") (pintype "passive"))
      (node (ref "S-I") (pin "A10") (pinfunction "2-3_A10") (pintype "passive"))
    )
    (net (code "368") (name "Net-(S-I-2-4)") (class "Default")
      (node (ref "CH-I2") (pin "3") (pinfunction "3_3") (pintype "passive"))
      (node (ref "S-I") (pin "B10") (pinfunction "2-4_B10") (pintype "passive"))
    )
    (net (code "369") (name "Net-(S-I-3-1)") (class "Default")
      (node (ref "CH-I3") (pin "3") (pinfunction "3_3") (pintype "passive"))
      (node (ref "S-I") (pin "C10") (pinfunction "3-1_C10") (pintype "passive"))
    )
    (net (code "370") (name "Net-(S-I-3-2)") (class "Default")
      (node (ref "CH-I1") (pin "4") (pinfunction "4_4") (pintype "passive"))
      (node (ref "S-I") (pin "A9") (pinfunction "3-2_A9") (pintype "passive"))
    )
    (net (code "371") (name "Net-(S-I-3-3)") (class "Default")
      (node (ref "CH-I2") (pin "4") (pinfunction "4_4") (pintype "passive"))
      (node (ref "S-I") (pin "B9") (pinfunction "3-3_B9") (pintype "passive"))
    )
    (net (code "372") (name "Net-(S-I-3-4)") (class "Default")
      (node (ref "CH-I3") (pin "4") (pinfunction "4_4") (pintype "passive"))
      (node (ref "S-I") (pin "C9") (pinfunction "3-4_C9") (pintype "passive"))
    )
    (net (code "373") (name "Net-(S-I-4-1)") (class "Default")
      (node (ref "CH-I4") (pin "1") (pinfunction "1_1") (pintype "passive"))
      (node (ref "S-I") (pin "A8") (pinfunction "4-1_A8") (pintype "passive"))
    )
    (net (code "374") (name "Net-(S-I-4-2)") (class "Default")
      (node (ref "CH-I5") (pin "1") (pinfunction "1_1") (pintype "passive"))
      (node (ref "S-I") (pin "B8") (pinfunction "4-2_B8") (pintype "passive"))
    )
    (net (code "375") (name "Net-(S-I-4-3)") (class "Default")
      (node (ref "CH-I6") (pin "1") (pinfunction "1_1") (pintype "passive"))
      (node (ref "S-I") (pin "C8") (pinfunction "4-3_C8") (pintype "passive"))
    )
    (net (code "376") (name "Net-(S-I-4-4)") (class "Default")
      (node (ref "CH-I4") (pin "2") (pinfunction "2_2") (pintype "passive"))
      (node (ref "S-I") (pin "A7") (pinfunction "4-4_A7") (pintype "passive"))
    )
    (net (code "377") (name "Net-(S-I-5-1)") (class "Default")
      (node (ref "CH-I5") (pin "2") (pinfunction "2_2") (pintype "passive"))
      (node (ref "S-I") (pin "B7") (pinfunction "5-1_B7") (pintype "passive"))
    )
    (net (code "378") (name "Net-(S-I-5-2)") (class "Default")
      (node (ref "CH-I6") (pin "2") (pinfunction "2_2") (pintype "passive"))
      (node (ref "S-I") (pin "C7") (pinfunction "5-2_C7") (pintype "passive"))
    )
    (net (code "379") (name "Net-(S-I-5-3)") (class "Default")
      (node (ref "CH-I4") (pin "3") (pinfunction "3_3") (pintype "passive"))
      (node (ref "S-I") (pin "A6") (pinfunction "5-3_A6") (pintype "passive"))
    )
    (net (code "380") (name "Net-(S-I-5-4)") (class "Default")
      (node (ref "CH-I5") (pin "3") (pinfunction "3_3") (pintype "passive"))
      (node (ref "S-I") (pin "B6") (pinfunction "5-4_B6") (pintype "passive"))
    )
    (net (code "381") (name "Net-(S-I-6-1)") (class "Default")
      (node (ref "CH-I6") (pin "3") (pinfunction "3_3") (pintype "passive"))
      (node (ref "S-I") (pin "C6") (pinfunction "6-1_C6") (pintype "passive"))
    )
    (net (code "382") (name "Net-(S-I-6-2)") (class "Default")
      (node (ref "CH-I4") (pin "4") (pinfunction "4_4") (pintype "passive"))
      (node (ref "S-I") (pin "A5") (pinfunction "6-2_A5") (pintype "passive"))
    )
    (net (code "383") (name "Net-(S-I-6-3)") (class "Default")
      (node (ref "CH-I5") (pin "4") (pinfunction "4_4") (pintype "passive"))
      (node (ref "S-I") (pin "B5") (pinfunction "6-3_B5") (pintype "passive"))
    )
    (net (code "384") (name "Net-(S-I-6-4)") (class "Default")
      (node (ref "CH-I6") (pin "4") (pinfunction "4_4") (pintype "passive"))
      (node (ref "S-I") (pin "C5") (pinfunction "6-4_C5") (pintype "passive"))
    )
    (net (code "385") (name "Net-(S-I-7-1)") (class "Default")
      (node (ref "CH-I7") (pin "1") (pinfunction "1_1") (pintype "passive"))
      (node (ref "S-I") (pin "A4") (pinfunction "7-1_A4") (pintype "passive"))
    )
    (net (code "386") (name "Net-(S-I-7-2)") (class "Default")
      (node (ref "CH-I8") (pin "1") (pinfunction "1_1") (pintype "passive"))
      (node (ref "S-I") (pin "B4") (pinfunction "7-2_B4") (pintype "passive"))
    )
    (net (code "387") (name "Net-(S-I-7-3)") (class "Default")
      (node (ref "CH-I9") (pin "1") (pinfunction "1_1") (pintype "passive"))
      (node (ref "S-I") (pin "C4") (pinfunction "7-3_C4") (pintype "passive"))
    )
    (net (code "388") (name "Net-(S-I-7-4)") (class "Default")
      (node (ref "CH-I7") (pin "2") (pinfunction "2_2") (pintype "passive"))
      (node (ref "S-I") (pin "A3") (pinfunction "7-4_A3") (pintype "passive"))
    )
    (net (code "389") (name "Net-(S-I-8-1)") (class "Default")
      (node (ref "CH-I8") (pin "2") (pinfunction "2_2") (pintype "passive"))
      (node (ref "S-I") (pin "B3") (pinfunction "8-1_B3") (pintype "passive"))
    )
    (net (code "390") (name "Net-(S-I-8-2)") (class "Default")
      (node (ref "CH-I9") (pin "2") (pinfunction "2_2") (pintype "passive"))
      (node (ref "S-I") (pin "C3") (pinfunction "8-2_C3") (pintype "passive"))
    )
    (net (code "391") (name "Net-(S-I-8-3)") (class "Default")
      (node (ref "CH-I7") (pin "3") (pinfunction "3_3") (pintype "passive"))
      (node (ref "S-I") (pin "A2") (pinfunction "8-3_A2") (pintype "passive"))
    )
    (net (code "392") (name "Net-(S-I-8-4)") (class "Default")
      (node (ref "CH-I8") (pin "3") (pinfunction "3_3") (pintype "passive"))
      (node (ref "S-I") (pin "B2") (pinfunction "8-4_B2") (pintype "passive"))
    )
    (net (code "393") (name "Net-(S-I-9-1)") (class "Default")
      (node (ref "CH-I9") (pin "3") (pinfunction "3_3") (pintype "passive"))
      (node (ref "S-I") (pin "C2") (pinfunction "9-1_C2") (pintype "passive"))
    )
    (net (code "394") (name "Net-(S-I-9-2)") (class "Default")
      (node (ref "CH-I7") (pin "4") (pinfunction "4_4") (pintype "passive"))
      (node (ref "S-I") (pin "A1") (pinfunction "9-2_A1") (pintype "passive"))
    )
    (net (code "395") (name "Net-(S-I-9-3)") (class "Default")
      (node (ref "CH-I8") (pin "4") (pinfunction "4_4") (pintype "passive"))
      (node (ref "S-I") (pin "B1") (pinfunction "9-3_B1") (pintype "passive"))
    )
    (net (code "396") (name "Net-(S-I-9-4)") (class "Default")
      (node (ref "CH-I9") (pin "4") (pinfunction "4_4") (pintype "passive"))
      (node (ref "S-I") (pin "C1") (pinfunction "9-4_C1") (pintype "passive"))
    )
    (net (code "397") (name "Net-(S-I-MISO)") (class "Default")
      (node (ref "S-I") (pin "B17") (pinfunction "MISO_B17") (pintype "passive"))
      (node (ref "S-J") (pin "B17") (pinfunction "MISO_B17") (pintype "passive"))
    )
    (net (code "398") (name "Net-(S-I-MOSI)") (class "Default")
      (node (ref "S-I") (pin "C17") (pinfunction "MOSI_C17") (pintype "passive"))
      (node (ref "S-J") (pin "C17") (pinfunction "MOSI_C17") (pintype "passive"))
    )
    (net (code "399") (name "Net-(S-I-SCK)") (class "Default")
      (node (ref "S-I") (pin "A16") (pinfunction "SCK_A16") (pintype "passive"))
      (node (ref "S-J") (pin "A16") (pinfunction "SCK_A16") (pintype "passive"))
    )
    (net (code "400") (name "Net-(S-I-SS)") (class "Default")
      (node (ref "S-I") (pin "A17") (pinfunction "SS_A17") (pintype "passive"))
      (node (ref "S-J") (pin "A17") (pinfunction "SS_A17") (pintype "passive"))
    )
    (net (code "401") (name "Net-(S-J-1-1)") (class "Default")
      (node (ref "CH-J1") (pin "1") (pinfunction "1_1") (pintype "passive"))
      (node (ref "S-J") (pin "A12") (pinfunction "1-1_A12") (pintype "passive"))
    )
    (net (code "402") (name "Net-(S-J-1-2)") (class "Default")
      (node (ref "CH-J2") (pin "1") (pinfunction "1_1") (pintype "passive"))
      (node (ref "S-J") (pin "B12") (pinfunction "1-2_B12") (pintype "passive"))
    )
    (net (code "403") (name "Net-(S-J-1-3)") (class "Default")
      (node (ref "CH-J3") (pin "1") (pinfunction "1_1") (pintype "passive"))
      (node (ref "S-J") (pin "C12") (pinfunction "1-3_C12") (pintype "passive"))
    )
    (net (code "404") (name "Net-(S-J-1-4)") (class "Default")
      (node (ref "CH-J1") (pin "2") (pinfunction "2_2") (pintype "passive"))
      (node (ref "S-J") (pin "A11") (pinfunction "1-4_A11") (pintype "passive"))
    )
    (net (code "405") (name "Net-(S-J-2-1)") (class "Default")
      (node (ref "CH-J2") (pin "2") (pinfunction "2_2") (pintype "passive"))
      (node (ref "S-J") (pin "B11") (pinfunction "2-1_B11") (pintype "passive"))
    )
    (net (code "406") (name "Net-(S-J-2-2)") (class "Default")
      (node (ref "CH-J3") (pin "2") (pinfunction "2_2") (pintype "passive"))
      (node (ref "S-J") (pin "C11") (pinfunction "2-2_C11") (pintype "passive"))
    )
    (net (code "407") (name "Net-(S-J-2-3)") (class "Default")
      (node (ref "CH-J1") (pin "3") (pinfunction "3_3") (pintype "passive"))
      (node (ref "S-J") (pin "A10") (pinfunction "2-3_A10") (pintype "passive"))
    )
    (net (code "408") (name "Net-(S-J-2-4)") (class "Default")
      (node (ref "CH-J2") (pin "3") (pinfunction "3_3") (pintype "passive"))
      (node (ref "S-J") (pin "B10") (pinfunction "2-4_B10") (pintype "passive"))
    )
    (net (code "409") (name "Net-(S-J-3-1)") (class "Default")
      (node (ref "CH-J3") (pin "3") (pinfunction "3_3") (pintype "passive"))
      (node (ref "S-J") (pin "C10") (pinfunction "3-1_C10") (pintype "passive"))
    )
    (net (code "410") (name "Net-(S-J-3-2)") (class "Default")
      (node (ref "CH-J1") (pin "4") (pinfunction "4_4") (pintype "passive"))
      (node (ref "S-J") (pin "A9") (pinfunction "3-2_A9") (pintype "passive"))
    )
    (net (code "411") (name "Net-(S-J-3-3)") (class "Default")
      (node (ref "CH-J2") (pin "4") (pinfunction "4_4") (pintype "passive"))
      (node (ref "S-J") (pin "B9") (pinfunction "3-3_B9") (pintype "passive"))
    )
    (net (code "412") (name "Net-(S-J-3-4)") (class "Default")
      (node (ref "CH-J3") (pin "4") (pinfunction "4_4") (pintype "passive"))
      (node (ref "S-J") (pin "C9") (pinfunction "3-4_C9") (pintype "passive"))
    )
    (net (code "413") (name "Net-(S-J-4-1)") (class "Default")
      (node (ref "CH-J4") (pin "1") (pinfunction "1_1") (pintype "passive"))
      (node (ref "S-J") (pin "A8") (pinfunction "4-1_A8") (pintype "passive"))
    )
    (net (code "414") (name "Net-(S-J-4-2)") (class "Default")
      (node (ref "CH-J5") (pin "1") (pinfunction "1_1") (pintype "passive"))
      (node (ref "S-J") (pin "B8") (pinfunction "4-2_B8") (pintype "passive"))
    )
    (net (code "415") (name "Net-(S-J-4-3)") (class "Default")
      (node (ref "CH-J6") (pin "1") (pinfunction "1_1") (pintype "passive"))
      (node (ref "S-J") (pin "C8") (pinfunction "4-3_C8") (pintype "passive"))
    )
    (net (code "416") (name "Net-(S-J-4-4)") (class "Default")
      (node (ref "CH-J4") (pin "2") (pinfunction "2_2") (pintype "passive"))
      (node (ref "S-J") (pin "A7") (pinfunction "4-4_A7") (pintype "passive"))
    )
    (net (code "417") (name "Net-(S-J-5-1)") (class "Default")
      (node (ref "CH-J5") (pin "2") (pinfunction "2_2") (pintype "passive"))
      (node (ref "S-J") (pin "B7") (pinfunction "5-1_B7") (pintype "passive"))
    )
    (net (code "418") (name "Net-(S-J-5-2)") (class "Default")
      (node (ref "CH-J6") (pin "2") (pinfunction "2_2") (pintype "passive"))
      (node (ref "S-J") (pin "C7") (pinfunction "5-2_C7") (pintype "passive"))
    )
    (net (code "419") (name "Net-(S-J-5-3)") (class "Default")
      (node (ref "CH-J4") (pin "3") (pinfunction "3_3") (pintype "passive"))
      (node (ref "S-J") (pin "A6") (pinfunction "5-3_A6") (pintype "passive"))
    )
    (net (code "420") (name "Net-(S-J-5-4)") (class "Default")
      (node (ref "CH-J5") (pin "3") (pinfunction "3_3") (pintype "passive"))
      (node (ref "S-J") (pin "B6") (pinfunction "5-4_B6") (pintype "passive"))
    )
    (net (code "421") (name "Net-(S-J-6-1)") (class "Default")
      (node (ref "CH-J6") (pin "3") (pinfunction "3_3") (pintype "passive"))
      (node (ref "S-J") (pin "C6") (pinfunction "6-1_C6") (pintype "passive"))
    )
    (net (code "422") (name "Net-(S-J-6-2)") (class "Default")
      (node (ref "CH-J4") (pin "4") (pinfunction "4_4") (pintype "passive"))
      (node (ref "S-J") (pin "A5") (pinfunction "6-2_A5") (pintype "passive"))
    )
    (net (code "423") (name "Net-(S-J-6-3)") (class "Default")
      (node (ref "CH-J5") (pin "4") (pinfunction "4_4") (pintype "passive"))
      (node (ref "S-J") (pin "B5") (pinfunction "6-3_B5") (pintype "passive"))
    )
    (net (code "424") (name "Net-(S-J-6-4)") (class "Default")
      (node (ref "CH-J6") (pin "4") (pinfunction "4_4") (pintype "passive"))
      (node (ref "S-J") (pin "C5") (pinfunction "6-4_C5") (pintype "passive"))
    )
    (net (code "425") (name "Net-(S-J-7-1)") (class "Default")
      (node (ref "CH-J7") (pin "1") (pinfunction "1_1") (pintype "passive"))
      (node (ref "S-J") (pin "A4") (pinfunction "7-1_A4") (pintype "passive"))
    )
    (net (code "426") (name "Net-(S-J-7-2)") (class "Default")
      (node (ref "CH-J8") (pin "1") (pinfunction "1_1") (pintype "passive"))
      (node (ref "S-J") (pin "B4") (pinfunction "7-2_B4") (pintype "passive"))
    )
    (net (code "427") (name "Net-(S-J-7-3)") (class "Default")
      (node (ref "CH-J9") (pin "1") (pinfunction "1_1") (pintype "passive"))
      (node (ref "S-J") (pin "C4") (pinfunction "7-3_C4") (pintype "passive"))
    )
    (net (code "428") (name "Net-(S-J-7-4)") (class "Default")
      (node (ref "CH-J7") (pin "2") (pinfunction "2_2") (pintype "passive"))
      (node (ref "S-J") (pin "A3") (pinfunction "7-4_A3") (pintype "passive"))
    )
    (net (code "429") (name "Net-(S-J-8-1)") (class "Default")
      (node (ref "CH-J8") (pin "2") (pinfunction "2_2") (pintype "passive"))
      (node (ref "S-J") (pin "B3") (pinfunction "8-1_B3") (pintype "passive"))
    )
    (net (code "430") (name "Net-(S-J-8-2)") (class "Default")
      (node (ref "CH-J9") (pin "2") (pinfunction "2_2") (pintype "passive"))
      (node (ref "S-J") (pin "C3") (pinfunction "8-2_C3") (pintype "passive"))
    )
    (net (code "431") (name "Net-(S-J-8-3)") (class "Default")
      (node (ref "CH-J7") (pin "3") (pinfunction "3_3") (pintype "passive"))
      (node (ref "S-J") (pin "A2") (pinfunction "8-3_A2") (pintype "passive"))
    )
    (net (code "432") (name "Net-(S-J-8-4)") (class "Default")
      (node (ref "CH-J8") (pin "3") (pinfunction "3_3") (pintype "passive"))
      (node (ref "S-J") (pin "B2") (pinfunction "8-4_B2") (pintype "passive"))
    )
    (net (code "433") (name "Net-(S-J-9-1)") (class "Default")
      (node (ref "CH-J9") (pin "3") (pinfunction "3_3") (pintype "passive"))
      (node (ref "S-J") (pin "C2") (pinfunction "9-1_C2") (pintype "passive"))
    )
    (net (code "434") (name "Net-(S-J-9-2)") (class "Default")
      (node (ref "CH-J7") (pin "4") (pinfunction "4_4") (pintype "passive"))
      (node (ref "S-J") (pin "A1") (pinfunction "9-2_A1") (pintype "passive"))
    )
    (net (code "435") (name "Net-(S-J-9-3)") (class "Default")
      (node (ref "CH-J8") (pin "4") (pinfunction "4_4") (pintype "passive"))
      (node (ref "S-J") (pin "B1") (pinfunction "9-3_B1") (pintype "passive"))
    )
    (net (code "436") (name "Net-(S-J-9-4)") (class "Default")
      (node (ref "CH-J9") (pin "4") (pinfunction "4_4") (pintype "passive"))
      (node (ref "S-J") (pin "C1") (pinfunction "9-4_C1") (pintype "passive"))
    )
    (net (code "437") (name "Net-(TMP36-1-VOUT)") (class "Default")
      (node (ref "AUNO") (pin "A1") (pinfunction "A1_A1") (pintype "passive"))
      (node (ref "TMP36-1") (pin "2") (pinfunction "VOUT_2") (pintype "output"))
    )
    (net (code "438") (name "Net-(TMP36-2-VOUT)") (class "Default")
      (node (ref "AUNO") (pin "A2") (pinfunction "A2_A2") (pintype "passive"))
      (node (ref "TMP36-2") (pin "2") (pinfunction "VOUT_2") (pintype "output"))
    )
    (net (code "439") (name "Net-(TMP36-3-VOUT)") (class "Default")
      (node (ref "AUNO") (pin "A3") (pinfunction "A3_A3") (pintype "passive"))
      (node (ref "TMP36-3") (pin "2") (pinfunction "VOUT_2") (pintype "output"))
    )
    (net (code "440") (name "unconnected-(AUNO-GND-PadGND1)") (class "Default")
      (node (ref "AUNO") (pin "GND1") (pinfunction "GND_GND1") (pintype "passive"))
    )
    (net (code "441") (name "unconnected-(AUNO-GND-PadGND3)") (class "Default")
      (node (ref "AUNO") (pin "GND3") (pinfunction "GND_GND3") (pintype "passive"))
    )
    (net (code "442") (name "unconnected-(AUNO-PadA0)") (class "Default")
      (node (ref "AUNO") (pin "A0") (pinfunction "A0_A0") (pintype "passive"))
    )
    (net (code "443") (name "unconnected-(AUNO-PadA4)") (class "Default")
      (node (ref "AUNO") (pin "A4") (pinfunction "A4_A4") (pintype "passive"))
    )
    (net (code "444") (name "unconnected-(AUNO-PadA5)") (class "Default")
      (node (ref "AUNO") (pin "A5") (pinfunction "A5_A5") (pintype "passive"))
    )
    (net (code "445") (name "unconnected-(AUNO-PadAREF)") (class "Default")
      (node (ref "AUNO") (pin "AREF") (pinfunction "AREF_AREF") (pintype "passive"))
    )
    (net (code "446") (name "unconnected-(AUNO-PadD12)") (class "Default")
      (node (ref "AUNO") (pin "D12") (pinfunction "D12_D12") (pintype "passive"))
    )
    (net (code "447") (name "unconnected-(AUNO-PadD13)") (class "Default")
      (node (ref "AUNO") (pin "D13") (pinfunction "D13_D13") (pintype "passive"))
    )
    (net (code "448") (name "unconnected-(AUNO-PadIOREF)") (class "Default")
      (node (ref "AUNO") (pin "IOREF") (pinfunction "IOREF_IOREF") (pintype "passive"))
    )
    (net (code "449") (name "unconnected-(AUNO-PadNC)") (class "Default")
      (node (ref "AUNO") (pin "NC") (pinfunction "NC_NC") (pintype "passive"))
    )
    (net (code "450") (name "unconnected-(AUNO-PadRESET)") (class "Default")
      (node (ref "AUNO") (pin "RESET") (pinfunction "RESET_RESET") (pintype "passive"))
    )
    (net (code "451") (name "unconnected-(AUNO-PadVIN)") (class "Default")
      (node (ref "AUNO") (pin "VIN") (pinfunction "VIN_VIN") (pintype "passive"))
    )
    (net (code "452") (name "unconnected-(RPI-3.3V-Pad17)") (class "Default")
      (node (ref "RPI") (pin "17") (pinfunction "3.3V_17") (pintype "passive"))
    )
    (net (code "453") (name "unconnected-(RPI-5V-Pad2)") (class "Default")
      (node (ref "RPI") (pin "2") (pinfunction "5V_2") (pintype "passive"))
    )
    (net (code "454") (name "unconnected-(RPI-GND-Pad6)") (class "Default")
      (node (ref "RPI") (pin "6") (pinfunction "GND_6") (pintype "passive"))
    )
    (net (code "455") (name "unconnected-(RPI-GND-Pad9)") (class "Default")
      (node (ref "RPI") (pin "9") (pinfunction "GND_9") (pintype "passive"))
    )
    (net (code "456") (name "unconnected-(RPI-GND-Pad14)") (class "Default")
      (node (ref "RPI") (pin "14") (pinfunction "GND_14") (pintype "passive"))
    )
    (net (code "457") (name "unconnected-(RPI-GND-Pad20)") (class "Default")
      (node (ref "RPI") (pin "20") (pinfunction "GND_20") (pintype "passive"))
    )
    (net (code "458") (name "unconnected-(RPI-GND-Pad25)") (class "Default")
      (node (ref "RPI") (pin "25") (pinfunction "GND_25") (pintype "passive"))
    )
    (net (code "459") (name "unconnected-(RPI-GND-Pad30)") (class "Default")
      (node (ref "RPI") (pin "30") (pinfunction "GND_30") (pintype "passive"))
    )
    (net (code "460") (name "unconnected-(RPI-GND-Pad39)") (class "Default")
      (node (ref "RPI") (pin "39") (pinfunction "GND_39") (pintype "passive"))
    )
    (net (code "461") (name "unconnected-(RPI-GPIO_07_(SPI_CE1_N)-Pad26)") (class "Default")
      (node (ref "RPI") (pin "26") (pinfunction "GPIO_07_(SPI_CE1_N)_26") (pintype "passive"))
    )
    (net (code "462") (name "unconnected-(RPI-GPIO_08_(SPI_CE0_N)-Pad24)") (class "Default")
      (node (ref "RPI") (pin "24") (pinfunction "GPIO_08_(SPI_CE0_N)_24") (pintype "passive"))
    )
    (net (code "463") (name "unconnected-(RPI-GPIO_09_(SPI_MISO)-Pad21)") (class "Default")
      (node (ref "RPI") (pin "21") (pinfunction "GPIO_09_(SPI_MISO)_21") (pintype "passive"))
    )
    (net (code "464") (name "unconnected-(RPI-GPIO_10_(SPI_MOSI)-Pad19)") (class "Default")
      (node (ref "RPI") (pin "19") (pinfunction "GPIO_10_(SPI_MOSI)_19") (pintype "passive"))
    )
    (net (code "465") (name "unconnected-(RPI-GPIO_11_(SPI_CLK)-Pad23)") (class "Default")
      (node (ref "RPI") (pin "23") (pinfunction "GPIO_11_(SPI_CLK)_23") (pintype "passive"))
    )
    (net (code "466") (name "unconnected-(RPI-GPIO_17_(GPIO_GEN0)-Pad11)") (class "Default")
      (node (ref "RPI") (pin "11") (pinfunction "GPIO_17_(GPIO_GEN0)_11") (pintype "passive"))
    )
    (net (code "467") (name "unconnected-(RPI-GPIO_18_(GPIO_GEN1)-Pad12)") (class "Default")
      (node (ref "RPI") (pin "12") (pinfunction "GPIO_18_(GPIO_GEN1)_12") (pintype "passive"))
    )
    (net (code "468") (name "unconnected-(RPI-GPIO_23_(GPIO_GEN4)-Pad16)") (class "Default")
      (node (ref "RPI") (pin "16") (pinfunction "GPIO_23_(GPIO_GEN4)_16") (pintype "passive"))
    )
    (net (code "469") (name "unconnected-(RPI-GPIO_24_(GPIO_GEN5)-Pad18)") (class "Default")
      (node (ref "RPI") (pin "18") (pinfunction "GPIO_24_(GPIO_GEN5)_18") (pintype "passive"))
    )
    (net (code "470") (name "unconnected-(RPI-GPIO_25_(GPIO_GEN6)-Pad22)") (class "Default")
      (node (ref "RPI") (pin "22") (pinfunction "GPIO_25_(GPIO_GEN6)_22") (pintype "passive"))
    )
    (net (code "471") (name "unconnected-(RPI-GPIO_27_(GPIO_GEN2)-Pad13)") (class "Default")
      (node (ref "RPI") (pin "13") (pinfunction "GPIO_27_(GPIO_GEN2)_13") (pintype "passive"))
    )
    (net (code "472") (name "unconnected-(RPI-ID_SC_(I2C_ID_EEPROM)-Pad28)") (class "Default")
      (node (ref "RPI") (pin "28") (pinfunction "ID_SC_(I2C_ID_EEPROM)_28") (pintype "bidirectional"))
    )
    (net (code "473") (name "unconnected-(RPI-ID_SD_(I2C_ID_EEPROM)-Pad27)") (class "Default")
      (node (ref "RPI") (pin "27") (pinfunction "ID_SD_(I2C_ID_EEPROM)_27") (pintype "bidirectional"))
    )
    (net (code "474") (name "unconnected-(S-A-NC-PadA14)") (class "Default")
      (node (ref "S-A") (pin "A14") (pinfunction "NC_A14") (pintype "passive"))
    )
    (net (code "475") (name "unconnected-(S-A-NC-PadA15)") (class "Default")
      (node (ref "S-A") (pin "A15") (pinfunction "NC_A15") (pintype "passive"))
    )
    (net (code "476") (name "unconnected-(S-B-NC-PadA14)") (class "Default")
      (node (ref "S-B") (pin "A14") (pinfunction "NC_A14") (pintype "passive"))
    )
    (net (code "477") (name "unconnected-(S-B-NC-PadA15)") (class "Default")
      (node (ref "S-B") (pin "A15") (pinfunction "NC_A15") (pintype "passive"))
    )
    (net (code "478") (name "unconnected-(S-C-NC-PadA14)") (class "Default")
      (node (ref "S-C") (pin "A14") (pinfunction "NC_A14") (pintype "passive"))
    )
    (net (code "479") (name "unconnected-(S-C-NC-PadA15)") (class "Default")
      (node (ref "S-C") (pin "A15") (pinfunction "NC_A15") (pintype "passive"))
    )
    (net (code "480") (name "unconnected-(S-D-NC-PadA14)") (class "Default")
      (node (ref "S-D") (pin "A14") (pinfunction "NC_A14") (pintype "passive"))
    )
    (net (code "481") (name "unconnected-(S-D-NC-PadA15)") (class "Default")
      (node (ref "S-D") (pin "A15") (pinfunction "NC_A15") (pintype "passive"))
    )
    (net (code "482") (name "unconnected-(S-E-NC-PadA14)") (class "Default")
      (node (ref "S-E") (pin "A14") (pinfunction "NC_A14") (pintype "passive"))
    )
    (net (code "483") (name "unconnected-(S-E-NC-PadA15)") (class "Default")
      (node (ref "S-E") (pin "A15") (pinfunction "NC_A15") (pintype "passive"))
    )
    (net (code "484") (name "unconnected-(S-F-NC-PadA14)") (class "Default")
      (node (ref "S-F") (pin "A14") (pinfunction "NC_A14") (pintype "passive"))
    )
    (net (code "485") (name "unconnected-(S-F-NC-PadA15)") (class "Default")
      (node (ref "S-F") (pin "A15") (pinfunction "NC_A15") (pintype "passive"))
    )
    (net (code "486") (name "unconnected-(S-G-NC-PadA14)") (class "Default")
      (node (ref "S-G") (pin "A14") (pinfunction "NC_A14") (pintype "passive"))
    )
    (net (code "487") (name "unconnected-(S-G-NC-PadA15)") (class "Default")
      (node (ref "S-G") (pin "A15") (pinfunction "NC_A15") (pintype "passive"))
    )
    (net (code "488") (name "unconnected-(S-H-NC-PadA14)") (class "Default")
      (node (ref "S-H") (pin "A14") (pinfunction "NC_A14") (pintype "passive"))
    )
    (net (code "489") (name "unconnected-(S-H-NC-PadA15)") (class "Default")
      (node (ref "S-H") (pin "A15") (pinfunction "NC_A15") (pintype "passive"))
    )
    (net (code "490") (name "unconnected-(S-I-NC-PadA14)") (class "Default")
      (node (ref "S-I") (pin "A14") (pinfunction "NC_A14") (pintype "passive"))
    )
    (net (code "491") (name "unconnected-(S-I-NC-PadA15)") (class "Default")
      (node (ref "S-I") (pin "A15") (pinfunction "NC_A15") (pintype "passive"))
    )
    (net (code "492") (name "unconnected-(S-J-NC-PadA14)") (class "Default")
      (node (ref "S-J") (pin "A14") (pinfunction "NC_A14") (pintype "passive"))
    )
    (net (code "493") (name "unconnected-(S-J-NC-PadA15)") (class "Default")
      (node (ref "S-J") (pin "A15") (pinfunction "NC_A15") (pintype "passive"))
    )
  )
)
